# LyteLab_16x16_Base_Rev1.net
KiCad netlist of a schematic drawn in EAGLE
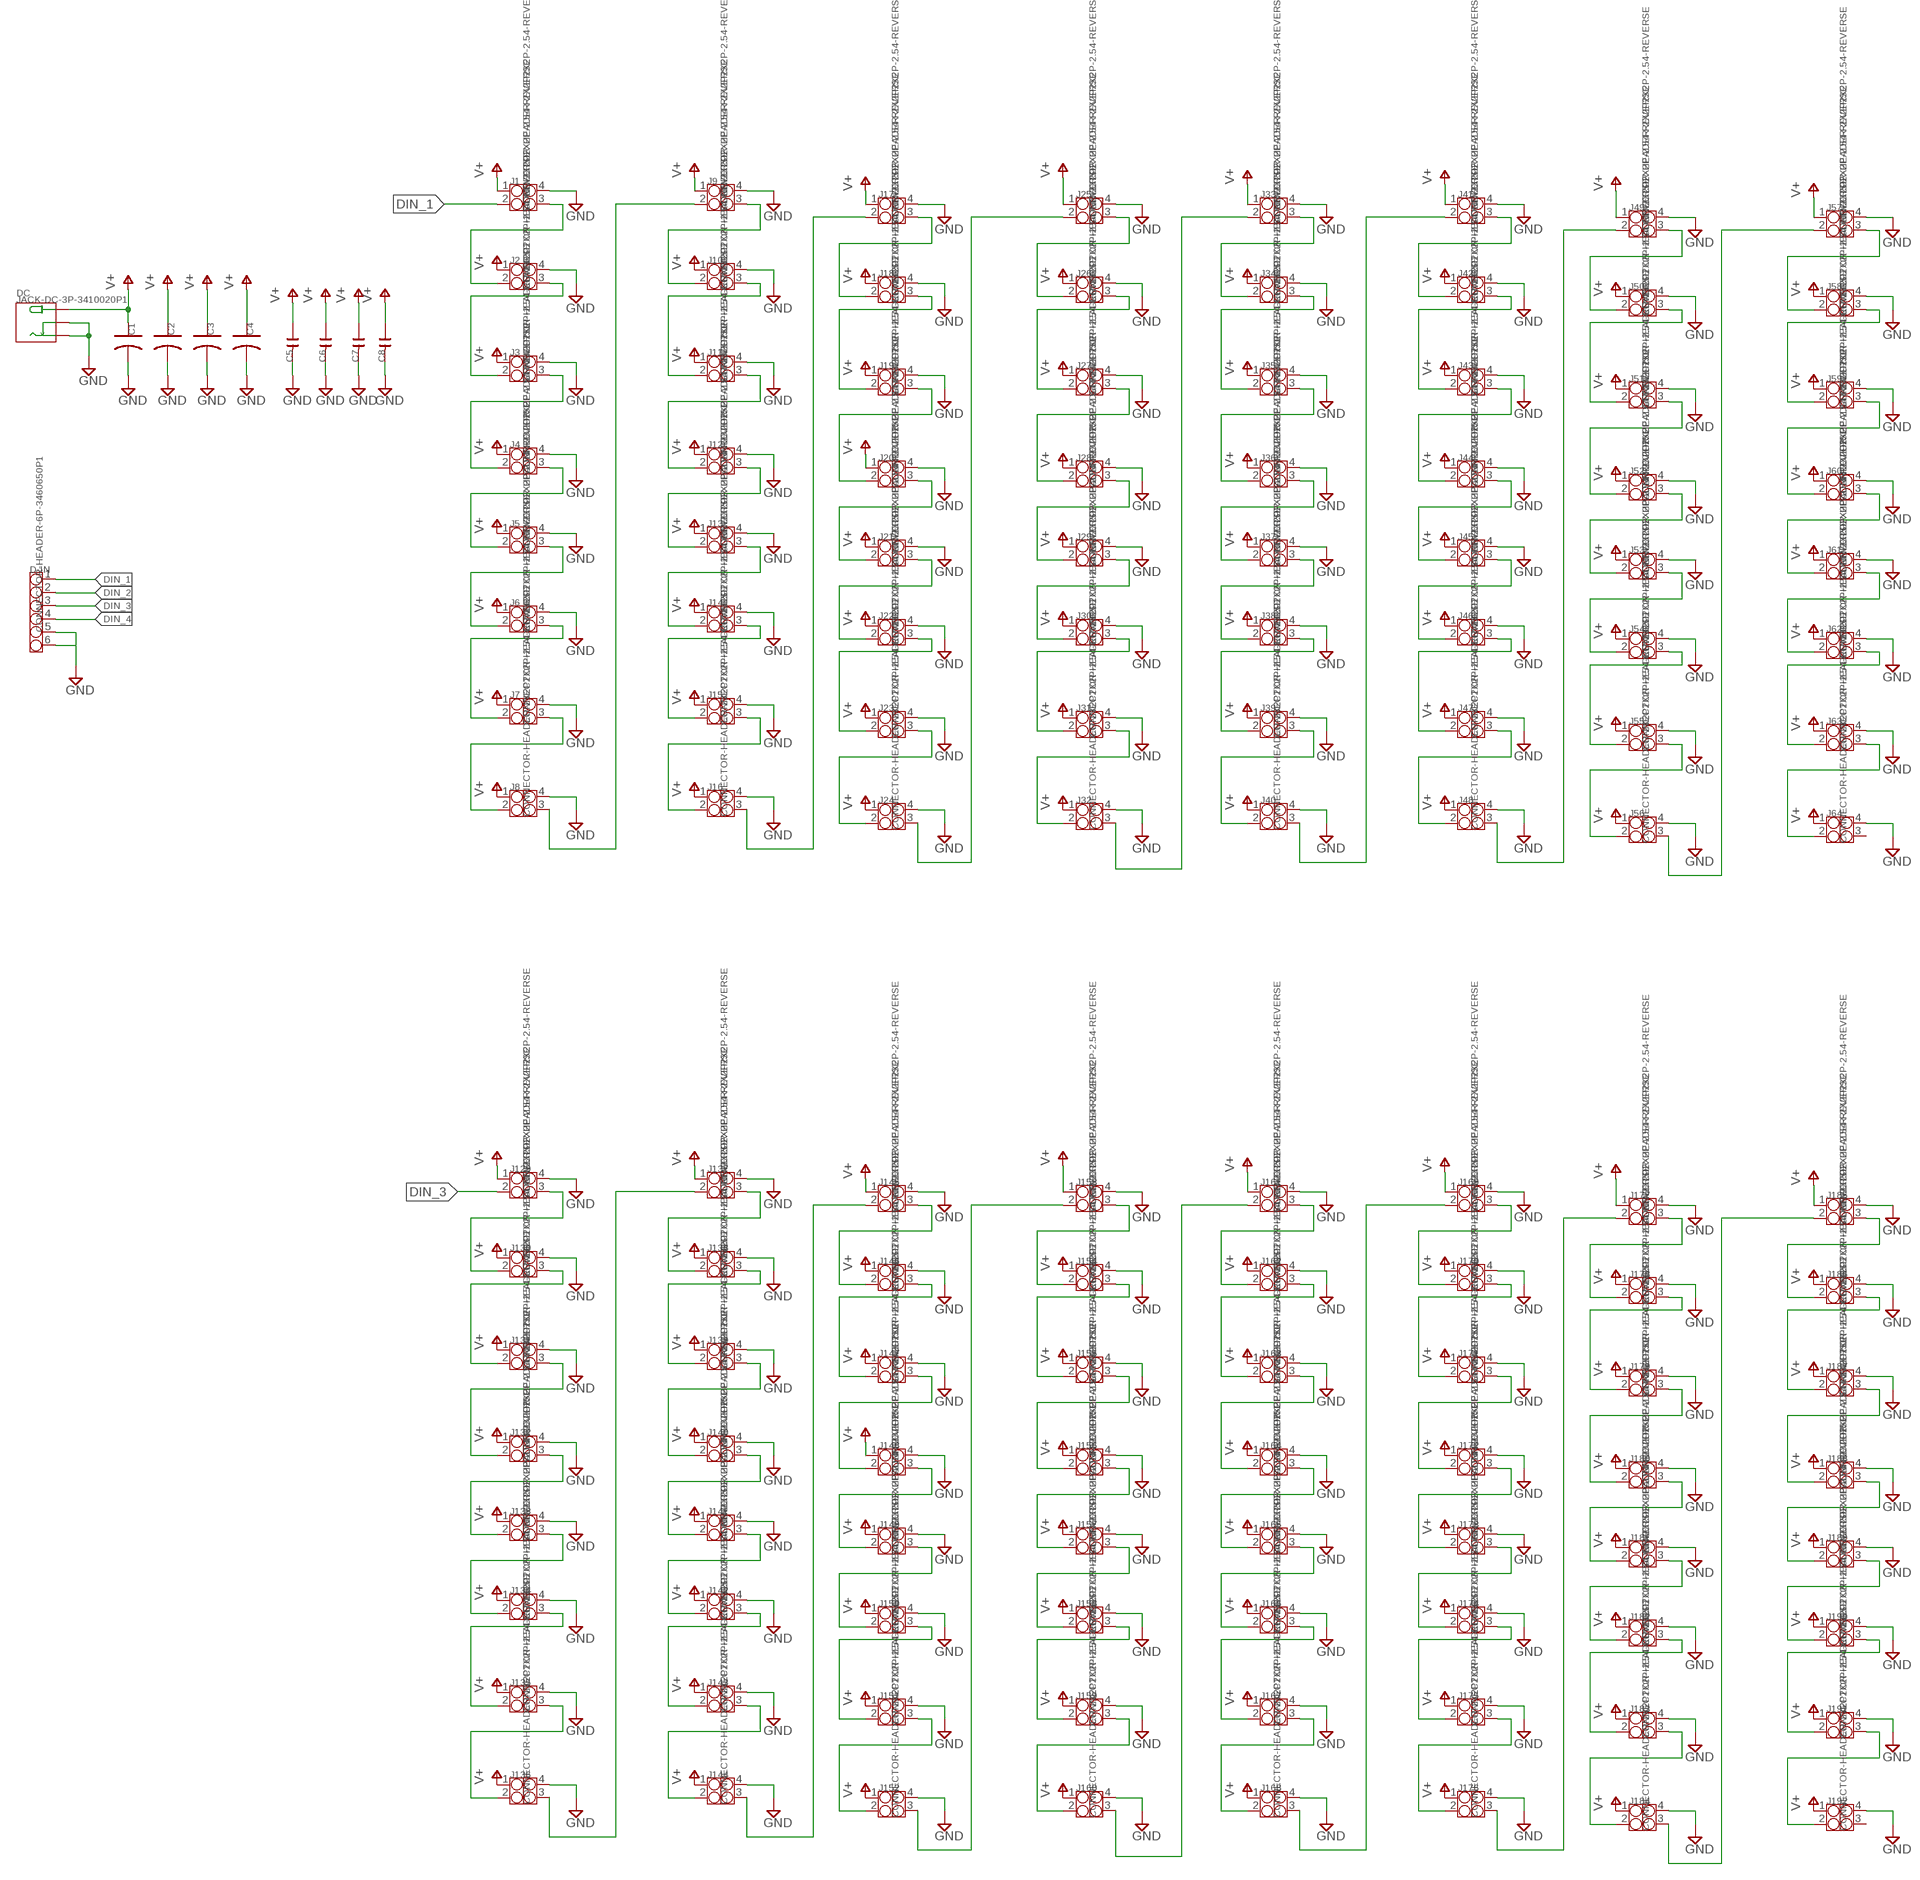
[diagram p0: schematic, sheet 1, part 1 of 2]
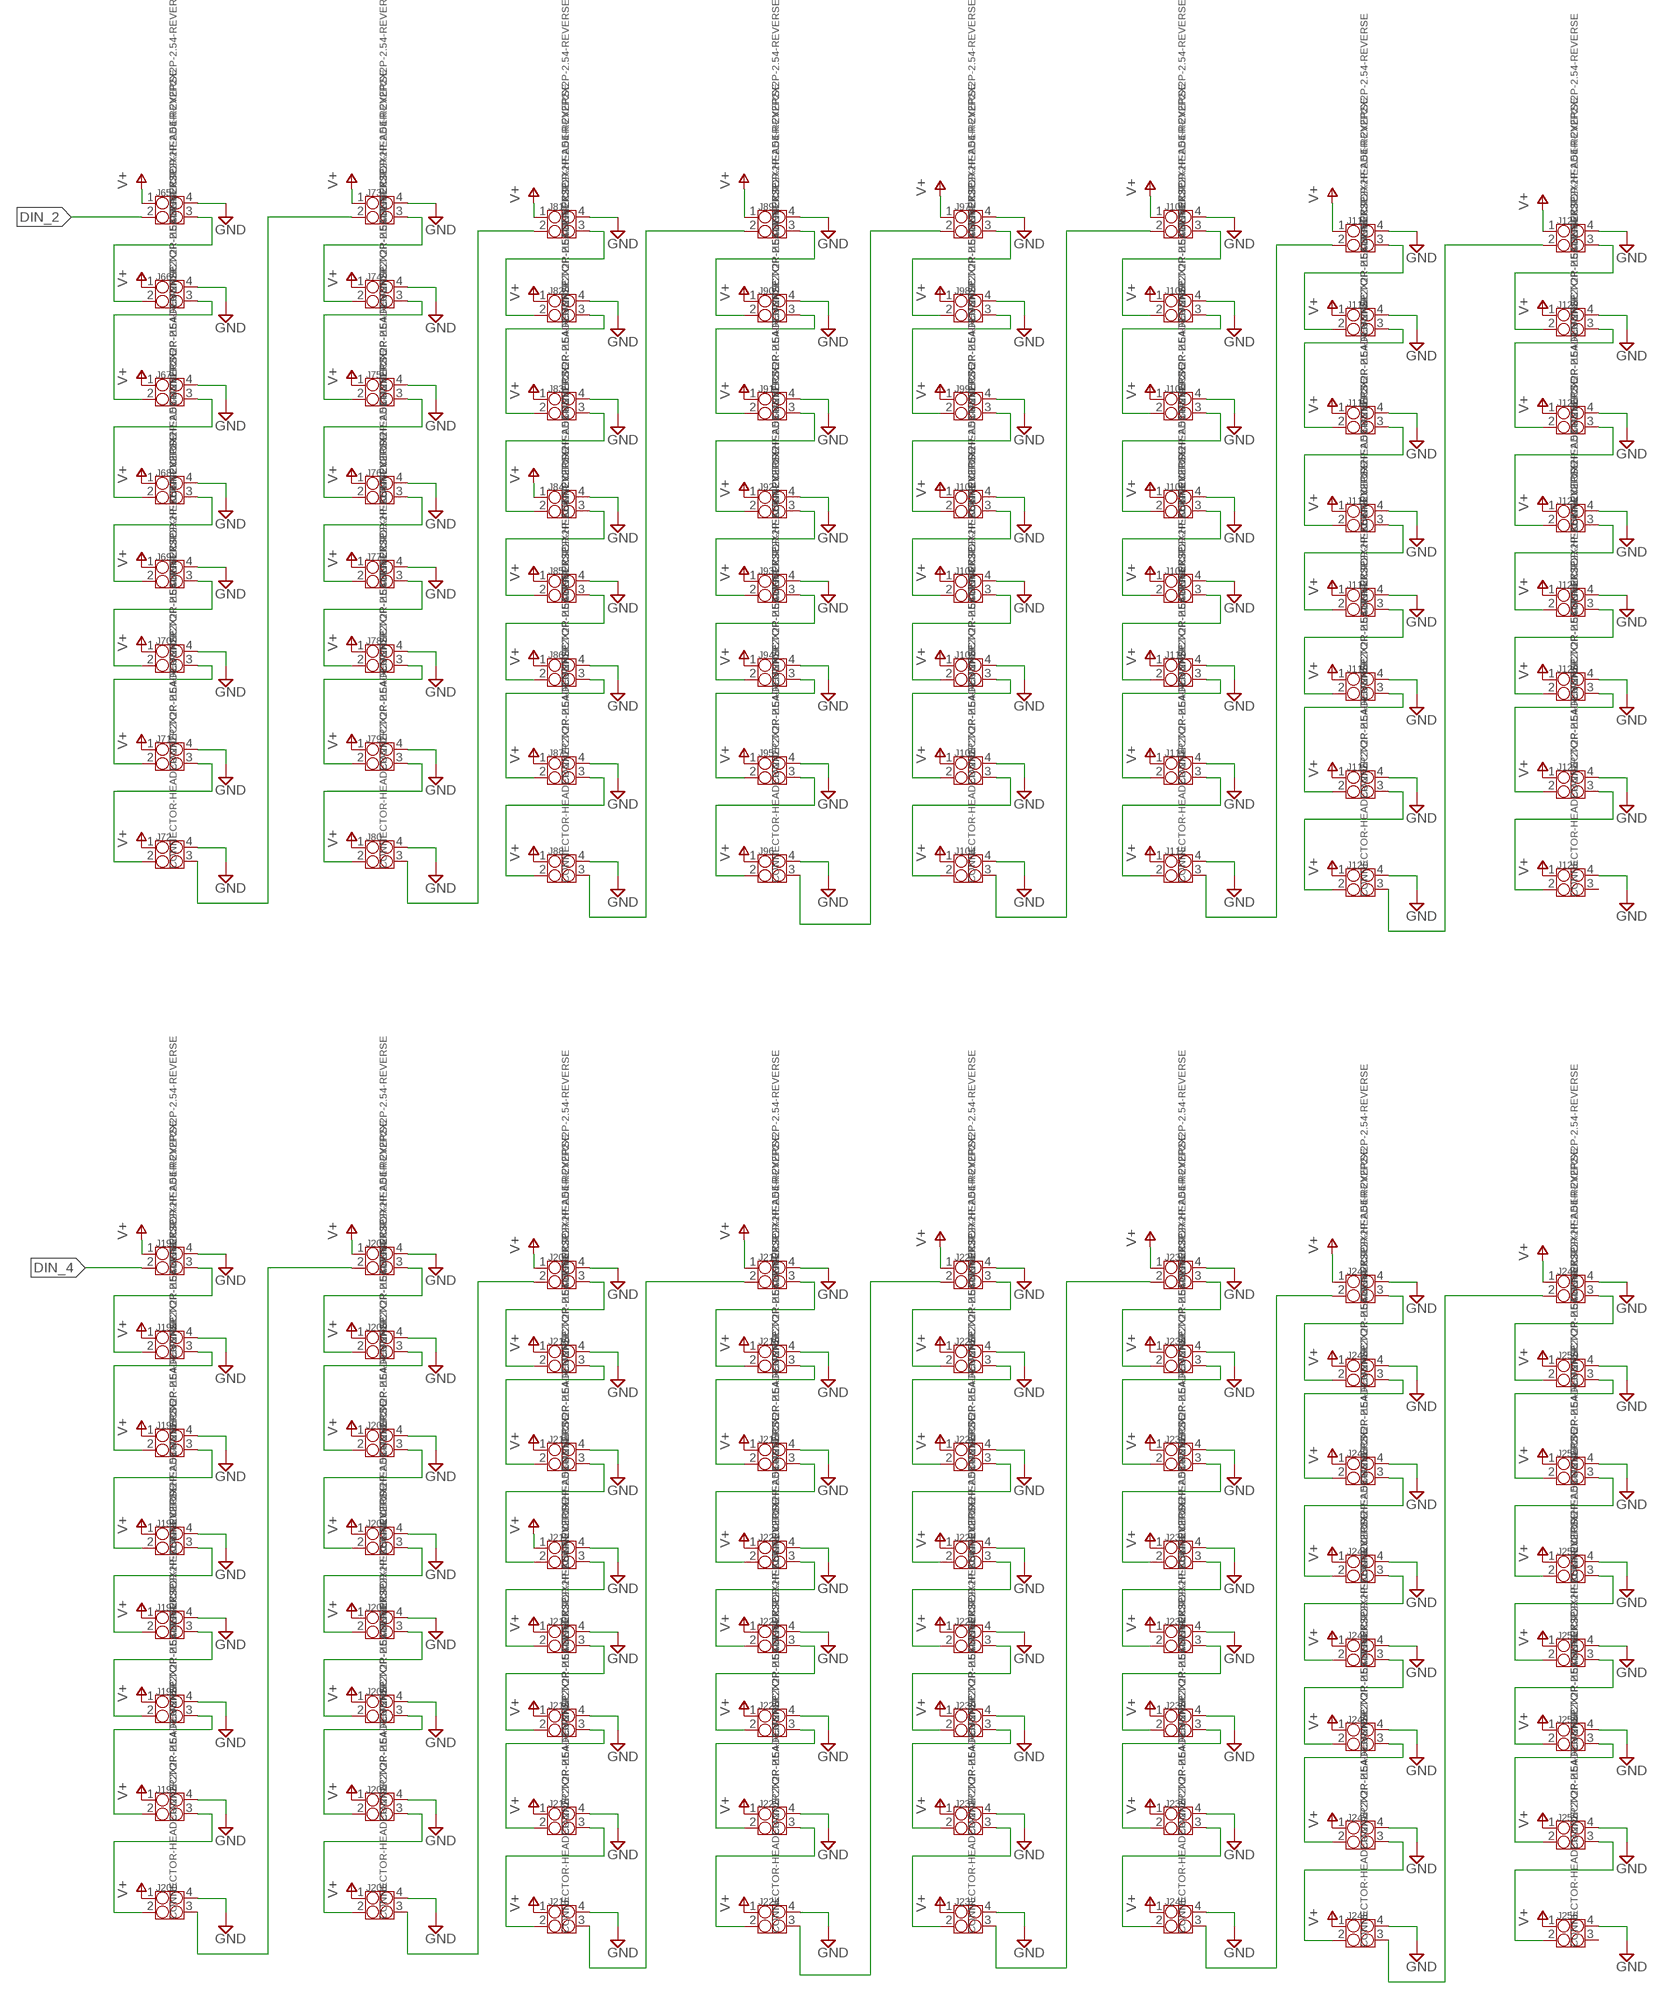
[diagram p1: schematic, sheet 1, part 2 of 2]

(export (version "E")
  (design (tool "Eeschema 10.0.6"))
  (components
    (comp (ref "C1")
      (value "C-POLAR")
      (footprint "eagle-import:CAPACITOR-E3-8")
      (libsource (lib "eagle-import") (part "C-POLAR"))
    )
    (comp (ref "C2")
      (value "C-POLAR")
      (footprint "eagle-import:CAPACITOR-E3-8")
      (libsource (lib "eagle-import") (part "C-POLAR"))
    )
    (comp (ref "C3")
      (value "C-POLAR")
      (footprint "eagle-import:CAPACITOR-E3-8")
      (libsource (lib "eagle-import") (part "C-POLAR"))
    )
    (comp (ref "C4")
      (value "C-POLAR")
      (footprint "eagle-import:CAPACITOR-E3-8")
      (libsource (lib "eagle-import") (part "C-POLAR"))
    )
    (comp (ref "C5")
      (value "C-0603")
      (footprint "eagle-import:C0603")
      (libsource (lib "eagle-import") (part "C-0603"))
    )
    (comp (ref "C6")
      (value "C-0603")
      (footprint "eagle-import:C0603")
      (libsource (lib "eagle-import") (part "C-0603"))
    )
    (comp (ref "C7")
      (value "C-0603")
      (footprint "eagle-import:C0603")
      (libsource (lib "eagle-import") (part "C-0603"))
    )
    (comp (ref "C8")
      (value "C-0603")
      (footprint "eagle-import:C0603")
      (libsource (lib "eagle-import") (part "C-0603"))
    )
    (comp (ref "D-IN")
      (value "CONNECTOR-HEADER-6P-3460650P1")
      (footprint "eagle-import:1X6P-2.54-2.54-11.6-3.0-BLACK-MALE")
      (libsource (lib "eagle-import") (part "CONNECTOR-HEADER-6P-3460650P1"))
    )
    (comp (ref "DC")
      (value "JACK-DC-3P-3410020P1")
      (footprint "eagle-import:PW-3P-2.1")
      (libsource (lib "eagle-import") (part "JACK-DC-3P-3410020P1"))
    )
    (comp (ref "J1")
      (value "CONNECTOR-HEADER-2X2P2X2P-2.54-REVERSE")
      (footprint "eagle-import:2X2P-2.54-REVERSE")
      (libsource (lib "eagle-import") (part "CONNECTOR-HEADER-2X2P2X2P-2.54-REVERSE"))
    )
    (comp (ref "J2")
      (value "CONNECTOR-HEADER-2X2P2X2P-2.54-REVERSE")
      (footprint "eagle-import:2X2P-2.54-REVERSE")
      (libsource (lib "eagle-import") (part "CONNECTOR-HEADER-2X2P2X2P-2.54-REVERSE"))
    )
    (comp (ref "J3")
      (value "CONNECTOR-HEADER-2X2P2X2P-2.54-REVERSE")
      (footprint "eagle-import:2X2P-2.54-REVERSE")
      (libsource (lib "eagle-import") (part "CONNECTOR-HEADER-2X2P2X2P-2.54-REVERSE"))
    )
    (comp (ref "J4")
      (value "CONNECTOR-HEADER-2X2P2X2P-2.54-REVERSE")
      (footprint "eagle-import:2X2P-2.54-REVERSE")
      (libsource (lib "eagle-import") (part "CONNECTOR-HEADER-2X2P2X2P-2.54-REVERSE"))
    )
    (comp (ref "J5")
      (value "CONNECTOR-HEADER-2X2P2X2P-2.54-REVERSE")
      (footprint "eagle-import:2X2P-2.54-REVERSE")
      (libsource (lib "eagle-import") (part "CONNECTOR-HEADER-2X2P2X2P-2.54-REVERSE"))
    )
    (comp (ref "J6")
      (value "CONNECTOR-HEADER-2X2P2X2P-2.54-REVERSE")
      (footprint "eagle-import:2X2P-2.54-REVERSE")
      (libsource (lib "eagle-import") (part "CONNECTOR-HEADER-2X2P2X2P-2.54-REVERSE"))
    )
    (comp (ref "J7")
      (value "CONNECTOR-HEADER-2X2P2X2P-2.54-REVERSE")
      (footprint "eagle-import:2X2P-2.54-REVERSE")
      (libsource (lib "eagle-import") (part "CONNECTOR-HEADER-2X2P2X2P-2.54-REVERSE"))
    )
    (comp (ref "J8")
      (value "CONNECTOR-HEADER-2X2P2X2P-2.54-REVERSE")
      (footprint "eagle-import:2X2P-2.54-REVERSE")
      (libsource (lib "eagle-import") (part "CONNECTOR-HEADER-2X2P2X2P-2.54-REVERSE"))
    )
    (comp (ref "J9")
      (value "CONNECTOR-HEADER-2X2P2X2P-2.54-REVERSE")
      (footprint "eagle-import:2X2P-2.54-REVERSE")
      (libsource (lib "eagle-import") (part "CONNECTOR-HEADER-2X2P2X2P-2.54-REVERSE"))
    )
    (comp (ref "J10")
      (value "CONNECTOR-HEADER-2X2P2X2P-2.54-REVERSE")
      (footprint "eagle-import:2X2P-2.54-REVERSE")
      (libsource (lib "eagle-import") (part "CONNECTOR-HEADER-2X2P2X2P-2.54-REVERSE"))
    )
    (comp (ref "J11")
      (value "CONNECTOR-HEADER-2X2P2X2P-2.54-REVERSE")
      (footprint "eagle-import:2X2P-2.54-REVERSE")
      (libsource (lib "eagle-import") (part "CONNECTOR-HEADER-2X2P2X2P-2.54-REVERSE"))
    )
    (comp (ref "J12")
      (value "CONNECTOR-HEADER-2X2P2X2P-2.54-REVERSE")
      (footprint "eagle-import:2X2P-2.54-REVERSE")
      (libsource (lib "eagle-import") (part "CONNECTOR-HEADER-2X2P2X2P-2.54-REVERSE"))
    )
    (comp (ref "J13")
      (value "CONNECTOR-HEADER-2X2P2X2P-2.54-REVERSE")
      (footprint "eagle-import:2X2P-2.54-REVERSE")
      (libsource (lib "eagle-import") (part "CONNECTOR-HEADER-2X2P2X2P-2.54-REVERSE"))
    )
    (comp (ref "J14")
      (value "CONNECTOR-HEADER-2X2P2X2P-2.54-REVERSE")
      (footprint "eagle-import:2X2P-2.54-REVERSE")
      (libsource (lib "eagle-import") (part "CONNECTOR-HEADER-2X2P2X2P-2.54-REVERSE"))
    )
    (comp (ref "J15")
      (value "CONNECTOR-HEADER-2X2P2X2P-2.54-REVERSE")
      (footprint "eagle-import:2X2P-2.54-REVERSE")
      (libsource (lib "eagle-import") (part "CONNECTOR-HEADER-2X2P2X2P-2.54-REVERSE"))
    )
    (comp (ref "J16")
      (value "CONNECTOR-HEADER-2X2P2X2P-2.54-REVERSE")
      (footprint "eagle-import:2X2P-2.54-REVERSE")
      (libsource (lib "eagle-import") (part "CONNECTOR-HEADER-2X2P2X2P-2.54-REVERSE"))
    )
    (comp (ref "J17")
      (value "CONNECTOR-HEADER-2X2P2X2P-2.54-REVERSE")
      (footprint "eagle-import:2X2P-2.54-REVERSE")
      (libsource (lib "eagle-import") (part "CONNECTOR-HEADER-2X2P2X2P-2.54-REVERSE"))
    )
    (comp (ref "J18")
      (value "CONNECTOR-HEADER-2X2P2X2P-2.54-REVERSE")
      (footprint "eagle-import:2X2P-2.54-REVERSE")
      (libsource (lib "eagle-import") (part "CONNECTOR-HEADER-2X2P2X2P-2.54-REVERSE"))
    )
    (comp (ref "J19")
      (value "CONNECTOR-HEADER-2X2P2X2P-2.54-REVERSE")
      (footprint "eagle-import:2X2P-2.54-REVERSE")
      (libsource (lib "eagle-import") (part "CONNECTOR-HEADER-2X2P2X2P-2.54-REVERSE"))
    )
    (comp (ref "J20")
      (value "CONNECTOR-HEADER-2X2P2X2P-2.54-REVERSE")
      (footprint "eagle-import:2X2P-2.54-REVERSE")
      (libsource (lib "eagle-import") (part "CONNECTOR-HEADER-2X2P2X2P-2.54-REVERSE"))
    )
    (comp (ref "J21")
      (value "CONNECTOR-HEADER-2X2P2X2P-2.54-REVERSE")
      (footprint "eagle-import:2X2P-2.54-REVERSE")
      (libsource (lib "eagle-import") (part "CONNECTOR-HEADER-2X2P2X2P-2.54-REVERSE"))
    )
    (comp (ref "J22")
      (value "CONNECTOR-HEADER-2X2P2X2P-2.54-REVERSE")
      (footprint "eagle-import:2X2P-2.54-REVERSE")
      (libsource (lib "eagle-import") (part "CONNECTOR-HEADER-2X2P2X2P-2.54-REVERSE"))
    )
    (comp (ref "J23")
      (value "CONNECTOR-HEADER-2X2P2X2P-2.54-REVERSE")
      (footprint "eagle-import:2X2P-2.54-REVERSE")
      (libsource (lib "eagle-import") (part "CONNECTOR-HEADER-2X2P2X2P-2.54-REVERSE"))
    )
    (comp (ref "J24")
      (value "CONNECTOR-HEADER-2X2P2X2P-2.54-REVERSE")
      (footprint "eagle-import:2X2P-2.54-REVERSE")
      (libsource (lib "eagle-import") (part "CONNECTOR-HEADER-2X2P2X2P-2.54-REVERSE"))
    )
    (comp (ref "J25")
      (value "CONNECTOR-HEADER-2X2P2X2P-2.54-REVERSE")
      (footprint "eagle-import:2X2P-2.54-REVERSE")
      (libsource (lib "eagle-import") (part "CONNECTOR-HEADER-2X2P2X2P-2.54-REVERSE"))
    )
    (comp (ref "J26")
      (value "CONNECTOR-HEADER-2X2P2X2P-2.54-REVERSE")
      (footprint "eagle-import:2X2P-2.54-REVERSE")
      (libsource (lib "eagle-import") (part "CONNECTOR-HEADER-2X2P2X2P-2.54-REVERSE"))
    )
    (comp (ref "J27")
      (value "CONNECTOR-HEADER-2X2P2X2P-2.54-REVERSE")
      (footprint "eagle-import:2X2P-2.54-REVERSE")
      (libsource (lib "eagle-import") (part "CONNECTOR-HEADER-2X2P2X2P-2.54-REVERSE"))
    )
    (comp (ref "J28")
      (value "CONNECTOR-HEADER-2X2P2X2P-2.54-REVERSE")
      (footprint "eagle-import:2X2P-2.54-REVERSE")
      (libsource (lib "eagle-import") (part "CONNECTOR-HEADER-2X2P2X2P-2.54-REVERSE"))
    )
    (comp (ref "J29")
      (value "CONNECTOR-HEADER-2X2P2X2P-2.54-REVERSE")
      (footprint "eagle-import:2X2P-2.54-REVERSE")
      (libsource (lib "eagle-import") (part "CONNECTOR-HEADER-2X2P2X2P-2.54-REVERSE"))
    )
    (comp (ref "J30")
      (value "CONNECTOR-HEADER-2X2P2X2P-2.54-REVERSE")
      (footprint "eagle-import:2X2P-2.54-REVERSE")
      (libsource (lib "eagle-import") (part "CONNECTOR-HEADER-2X2P2X2P-2.54-REVERSE"))
    )
    (comp (ref "J31")
      (value "CONNECTOR-HEADER-2X2P2X2P-2.54-REVERSE")
      (footprint "eagle-import:2X2P-2.54-REVERSE")
      (libsource (lib "eagle-import") (part "CONNECTOR-HEADER-2X2P2X2P-2.54-REVERSE"))
    )
    (comp (ref "J32")
      (value "CONNECTOR-HEADER-2X2P2X2P-2.54-REVERSE")
      (footprint "eagle-import:2X2P-2.54-REVERSE")
      (libsource (lib "eagle-import") (part "CONNECTOR-HEADER-2X2P2X2P-2.54-REVERSE"))
    )
    (comp (ref "J33")
      (value "CONNECTOR-HEADER-2X2P2X2P-2.54-REVERSE")
      (footprint "eagle-import:2X2P-2.54-REVERSE")
      (libsource (lib "eagle-import") (part "CONNECTOR-HEADER-2X2P2X2P-2.54-REVERSE"))
    )
    (comp (ref "J34")
      (value "CONNECTOR-HEADER-2X2P2X2P-2.54-REVERSE")
      (footprint "eagle-import:2X2P-2.54-REVERSE")
      (libsource (lib "eagle-import") (part "CONNECTOR-HEADER-2X2P2X2P-2.54-REVERSE"))
    )
    (comp (ref "J35")
      (value "CONNECTOR-HEADER-2X2P2X2P-2.54-REVERSE")
      (footprint "eagle-import:2X2P-2.54-REVERSE")
      (libsource (lib "eagle-import") (part "CONNECTOR-HEADER-2X2P2X2P-2.54-REVERSE"))
    )
    (comp (ref "J36")
      (value "CONNECTOR-HEADER-2X2P2X2P-2.54-REVERSE")
      (footprint "eagle-import:2X2P-2.54-REVERSE")
      (libsource (lib "eagle-import") (part "CONNECTOR-HEADER-2X2P2X2P-2.54-REVERSE"))
    )
    (comp (ref "J37")
      (value "CONNECTOR-HEADER-2X2P2X2P-2.54-REVERSE")
      (footprint "eagle-import:2X2P-2.54-REVERSE")
      (libsource (lib "eagle-import") (part "CONNECTOR-HEADER-2X2P2X2P-2.54-REVERSE"))
    )
    (comp (ref "J38")
      (value "CONNECTOR-HEADER-2X2P2X2P-2.54-REVERSE")
      (footprint "eagle-import:2X2P-2.54-REVERSE")
      (libsource (lib "eagle-import") (part "CONNECTOR-HEADER-2X2P2X2P-2.54-REVERSE"))
    )
    (comp (ref "J39")
      (value "CONNECTOR-HEADER-2X2P2X2P-2.54-REVERSE")
      (footprint "eagle-import:2X2P-2.54-REVERSE")
      (libsource (lib "eagle-import") (part "CONNECTOR-HEADER-2X2P2X2P-2.54-REVERSE"))
    )
    (comp (ref "J40")
      (value "CONNECTOR-HEADER-2X2P2X2P-2.54-REVERSE")
      (footprint "eagle-import:2X2P-2.54-REVERSE")
      (libsource (lib "eagle-import") (part "CONNECTOR-HEADER-2X2P2X2P-2.54-REVERSE"))
    )
    (comp (ref "J41")
      (value "CONNECTOR-HEADER-2X2P2X2P-2.54-REVERSE")
      (footprint "eagle-import:2X2P-2.54-REVERSE")
      (libsource (lib "eagle-import") (part "CONNECTOR-HEADER-2X2P2X2P-2.54-REVERSE"))
    )
    (comp (ref "J42")
      (value "CONNECTOR-HEADER-2X2P2X2P-2.54-REVERSE")
      (footprint "eagle-import:2X2P-2.54-REVERSE")
      (libsource (lib "eagle-import") (part "CONNECTOR-HEADER-2X2P2X2P-2.54-REVERSE"))
    )
    (comp (ref "J43")
      (value "CONNECTOR-HEADER-2X2P2X2P-2.54-REVERSE")
      (footprint "eagle-import:2X2P-2.54-REVERSE")
      (libsource (lib "eagle-import") (part "CONNECTOR-HEADER-2X2P2X2P-2.54-REVERSE"))
    )
    (comp (ref "J44")
      (value "CONNECTOR-HEADER-2X2P2X2P-2.54-REVERSE")
      (footprint "eagle-import:2X2P-2.54-REVERSE")
      (libsource (lib "eagle-import") (part "CONNECTOR-HEADER-2X2P2X2P-2.54-REVERSE"))
    )
    (comp (ref "J45")
      (value "CONNECTOR-HEADER-2X2P2X2P-2.54-REVERSE")
      (footprint "eagle-import:2X2P-2.54-REVERSE")
      (libsource (lib "eagle-import") (part "CONNECTOR-HEADER-2X2P2X2P-2.54-REVERSE"))
    )
    (comp (ref "J46")
      (value "CONNECTOR-HEADER-2X2P2X2P-2.54-REVERSE")
      (footprint "eagle-import:2X2P-2.54-REVERSE")
      (libsource (lib "eagle-import") (part "CONNECTOR-HEADER-2X2P2X2P-2.54-REVERSE"))
    )
    (comp (ref "J47")
      (value "CONNECTOR-HEADER-2X2P2X2P-2.54-REVERSE")
      (footprint "eagle-import:2X2P-2.54-REVERSE")
      (libsource (lib "eagle-import") (part "CONNECTOR-HEADER-2X2P2X2P-2.54-REVERSE"))
    )
    (comp (ref "J48")
      (value "CONNECTOR-HEADER-2X2P2X2P-2.54-REVERSE")
      (footprint "eagle-import:2X2P-2.54-REVERSE")
      (libsource (lib "eagle-import") (part "CONNECTOR-HEADER-2X2P2X2P-2.54-REVERSE"))
    )
    (comp (ref "J49")
      (value "CONNECTOR-HEADER-2X2P2X2P-2.54-REVERSE")
      (footprint "eagle-import:2X2P-2.54-REVERSE")
      (libsource (lib "eagle-import") (part "CONNECTOR-HEADER-2X2P2X2P-2.54-REVERSE"))
    )
    (comp (ref "J50")
      (value "CONNECTOR-HEADER-2X2P2X2P-2.54-REVERSE")
      (footprint "eagle-import:2X2P-2.54-REVERSE")
      (libsource (lib "eagle-import") (part "CONNECTOR-HEADER-2X2P2X2P-2.54-REVERSE"))
    )
    (comp (ref "J51")
      (value "CONNECTOR-HEADER-2X2P2X2P-2.54-REVERSE")
      (footprint "eagle-import:2X2P-2.54-REVERSE")
      (libsource (lib "eagle-import") (part "CONNECTOR-HEADER-2X2P2X2P-2.54-REVERSE"))
    )
    (comp (ref "J52")
      (value "CONNECTOR-HEADER-2X2P2X2P-2.54-REVERSE")
      (footprint "eagle-import:2X2P-2.54-REVERSE")
      (libsource (lib "eagle-import") (part "CONNECTOR-HEADER-2X2P2X2P-2.54-REVERSE"))
    )
    (comp (ref "J53")
      (value "CONNECTOR-HEADER-2X2P2X2P-2.54-REVERSE")
      (footprint "eagle-import:2X2P-2.54-REVERSE")
      (libsource (lib "eagle-import") (part "CONNECTOR-HEADER-2X2P2X2P-2.54-REVERSE"))
    )
    (comp (ref "J54")
      (value "CONNECTOR-HEADER-2X2P2X2P-2.54-REVERSE")
      (footprint "eagle-import:2X2P-2.54-REVERSE")
      (libsource (lib "eagle-import") (part "CONNECTOR-HEADER-2X2P2X2P-2.54-REVERSE"))
    )
    (comp (ref "J55")
      (value "CONNECTOR-HEADER-2X2P2X2P-2.54-REVERSE")
      (footprint "eagle-import:2X2P-2.54-REVERSE")
      (libsource (lib "eagle-import") (part "CONNECTOR-HEADER-2X2P2X2P-2.54-REVERSE"))
    )
    (comp (ref "J56")
      (value "CONNECTOR-HEADER-2X2P2X2P-2.54-REVERSE")
      (footprint "eagle-import:2X2P-2.54-REVERSE")
      (libsource (lib "eagle-import") (part "CONNECTOR-HEADER-2X2P2X2P-2.54-REVERSE"))
    )
    (comp (ref "J57")
      (value "CONNECTOR-HEADER-2X2P2X2P-2.54-REVERSE")
      (footprint "eagle-import:2X2P-2.54-REVERSE")
      (libsource (lib "eagle-import") (part "CONNECTOR-HEADER-2X2P2X2P-2.54-REVERSE"))
    )
    (comp (ref "J58")
      (value "CONNECTOR-HEADER-2X2P2X2P-2.54-REVERSE")
      (footprint "eagle-import:2X2P-2.54-REVERSE")
      (libsource (lib "eagle-import") (part "CONNECTOR-HEADER-2X2P2X2P-2.54-REVERSE"))
    )
    (comp (ref "J59")
      (value "CONNECTOR-HEADER-2X2P2X2P-2.54-REVERSE")
      (footprint "eagle-import:2X2P-2.54-REVERSE")
      (libsource (lib "eagle-import") (part "CONNECTOR-HEADER-2X2P2X2P-2.54-REVERSE"))
    )
    (comp (ref "J60")
      (value "CONNECTOR-HEADER-2X2P2X2P-2.54-REVERSE")
      (footprint "eagle-import:2X2P-2.54-REVERSE")
      (libsource (lib "eagle-import") (part "CONNECTOR-HEADER-2X2P2X2P-2.54-REVERSE"))
    )
    (comp (ref "J61")
      (value "CONNECTOR-HEADER-2X2P2X2P-2.54-REVERSE")
      (footprint "eagle-import:2X2P-2.54-REVERSE")
      (libsource (lib "eagle-import") (part "CONNECTOR-HEADER-2X2P2X2P-2.54-REVERSE"))
    )
    (comp (ref "J62")
      (value "CONNECTOR-HEADER-2X2P2X2P-2.54-REVERSE")
      (footprint "eagle-import:2X2P-2.54-REVERSE")
      (libsource (lib "eagle-import") (part "CONNECTOR-HEADER-2X2P2X2P-2.54-REVERSE"))
    )
    (comp (ref "J63")
      (value "CONNECTOR-HEADER-2X2P2X2P-2.54-REVERSE")
      (footprint "eagle-import:2X2P-2.54-REVERSE")
      (libsource (lib "eagle-import") (part "CONNECTOR-HEADER-2X2P2X2P-2.54-REVERSE"))
    )
    (comp (ref "J64")
      (value "CONNECTOR-HEADER-2X2P2X2P-2.54-REVERSE")
      (footprint "eagle-import:2X2P-2.54-REVERSE")
      (libsource (lib "eagle-import") (part "CONNECTOR-HEADER-2X2P2X2P-2.54-REVERSE"))
    )
    (comp (ref "J65")
      (value "CONNECTOR-HEADER-2X2P2X2P-2.54-REVERSE")
      (footprint "eagle-import:2X2P-2.54-REVERSE")
      (libsource (lib "eagle-import") (part "CONNECTOR-HEADER-2X2P2X2P-2.54-REVERSE"))
    )
    (comp (ref "J66")
      (value "CONNECTOR-HEADER-2X2P2X2P-2.54-REVERSE")
      (footprint "eagle-import:2X2P-2.54-REVERSE")
      (libsource (lib "eagle-import") (part "CONNECTOR-HEADER-2X2P2X2P-2.54-REVERSE"))
    )
    (comp (ref "J67")
      (value "CONNECTOR-HEADER-2X2P2X2P-2.54-REVERSE")
      (footprint "eagle-import:2X2P-2.54-REVERSE")
      (libsource (lib "eagle-import") (part "CONNECTOR-HEADER-2X2P2X2P-2.54-REVERSE"))
    )
    (comp (ref "J68")
      (value "CONNECTOR-HEADER-2X2P2X2P-2.54-REVERSE")
      (footprint "eagle-import:2X2P-2.54-REVERSE")
      (libsource (lib "eagle-import") (part "CONNECTOR-HEADER-2X2P2X2P-2.54-REVERSE"))
    )
    (comp (ref "J69")
      (value "CONNECTOR-HEADER-2X2P2X2P-2.54-REVERSE")
      (footprint "eagle-import:2X2P-2.54-REVERSE")
      (libsource (lib "eagle-import") (part "CONNECTOR-HEADER-2X2P2X2P-2.54-REVERSE"))
    )
    (comp (ref "J70")
      (value "CONNECTOR-HEADER-2X2P2X2P-2.54-REVERSE")
      (footprint "eagle-import:2X2P-2.54-REVERSE")
      (libsource (lib "eagle-import") (part "CONNECTOR-HEADER-2X2P2X2P-2.54-REVERSE"))
    )
    (comp (ref "J71")
      (value "CONNECTOR-HEADER-2X2P2X2P-2.54-REVERSE")
      (footprint "eagle-import:2X2P-2.54-REVERSE")
      (libsource (lib "eagle-import") (part "CONNECTOR-HEADER-2X2P2X2P-2.54-REVERSE"))
    )
    (comp (ref "J72")
      (value "CONNECTOR-HEADER-2X2P2X2P-2.54-REVERSE")
      (footprint "eagle-import:2X2P-2.54-REVERSE")
      (libsource (lib "eagle-import") (part "CONNECTOR-HEADER-2X2P2X2P-2.54-REVERSE"))
    )
    (comp (ref "J73")
      (value "CONNECTOR-HEADER-2X2P2X2P-2.54-REVERSE")
      (footprint "eagle-import:2X2P-2.54-REVERSE")
      (libsource (lib "eagle-import") (part "CONNECTOR-HEADER-2X2P2X2P-2.54-REVERSE"))
    )
    (comp (ref "J74")
      (value "CONNECTOR-HEADER-2X2P2X2P-2.54-REVERSE")
      (footprint "eagle-import:2X2P-2.54-REVERSE")
      (libsource (lib "eagle-import") (part "CONNECTOR-HEADER-2X2P2X2P-2.54-REVERSE"))
    )
    (comp (ref "J75")
      (value "CONNECTOR-HEADER-2X2P2X2P-2.54-REVERSE")
      (footprint "eagle-import:2X2P-2.54-REVERSE")
      (libsource (lib "eagle-import") (part "CONNECTOR-HEADER-2X2P2X2P-2.54-REVERSE"))
    )
    (comp (ref "J76")
      (value "CONNECTOR-HEADER-2X2P2X2P-2.54-REVERSE")
      (footprint "eagle-import:2X2P-2.54-REVERSE")
      (libsource (lib "eagle-import") (part "CONNECTOR-HEADER-2X2P2X2P-2.54-REVERSE"))
    )
    (comp (ref "J77")
      (value "CONNECTOR-HEADER-2X2P2X2P-2.54-REVERSE")
      (footprint "eagle-import:2X2P-2.54-REVERSE")
      (libsource (lib "eagle-import") (part "CONNECTOR-HEADER-2X2P2X2P-2.54-REVERSE"))
    )
    (comp (ref "J78")
      (value "CONNECTOR-HEADER-2X2P2X2P-2.54-REVERSE")
      (footprint "eagle-import:2X2P-2.54-REVERSE")
      (libsource (lib "eagle-import") (part "CONNECTOR-HEADER-2X2P2X2P-2.54-REVERSE"))
    )
    (comp (ref "J79")
      (value "CONNECTOR-HEADER-2X2P2X2P-2.54-REVERSE")
      (footprint "eagle-import:2X2P-2.54-REVERSE")
      (libsource (lib "eagle-import") (part "CONNECTOR-HEADER-2X2P2X2P-2.54-REVERSE"))
    )
    (comp (ref "J80")
      (value "CONNECTOR-HEADER-2X2P2X2P-2.54-REVERSE")
      (footprint "eagle-import:2X2P-2.54-REVERSE")
      (libsource (lib "eagle-import") (part "CONNECTOR-HEADER-2X2P2X2P-2.54-REVERSE"))
    )
    (comp (ref "J81")
      (value "CONNECTOR-HEADER-2X2P2X2P-2.54-REVERSE")
      (footprint "eagle-import:2X2P-2.54-REVERSE")
      (libsource (lib "eagle-import") (part "CONNECTOR-HEADER-2X2P2X2P-2.54-REVERSE"))
    )
    (comp (ref "J82")
      (value "CONNECTOR-HEADER-2X2P2X2P-2.54-REVERSE")
      (footprint "eagle-import:2X2P-2.54-REVERSE")
      (libsource (lib "eagle-import") (part "CONNECTOR-HEADER-2X2P2X2P-2.54-REVERSE"))
    )
    (comp (ref "J83")
      (value "CONNECTOR-HEADER-2X2P2X2P-2.54-REVERSE")
      (footprint "eagle-import:2X2P-2.54-REVERSE")
      (libsource (lib "eagle-import") (part "CONNECTOR-HEADER-2X2P2X2P-2.54-REVERSE"))
    )
    (comp (ref "J84")
      (value "CONNECTOR-HEADER-2X2P2X2P-2.54-REVERSE")
      (footprint "eagle-import:2X2P-2.54-REVERSE")
      (libsource (lib "eagle-import") (part "CONNECTOR-HEADER-2X2P2X2P-2.54-REVERSE"))
    )
    (comp (ref "J85")
      (value "CONNECTOR-HEADER-2X2P2X2P-2.54-REVERSE")
      (footprint "eagle-import:2X2P-2.54-REVERSE")
      (libsource (lib "eagle-import") (part "CONNECTOR-HEADER-2X2P2X2P-2.54-REVERSE"))
    )
    (comp (ref "J86")
      (value "CONNECTOR-HEADER-2X2P2X2P-2.54-REVERSE")
      (footprint "eagle-import:2X2P-2.54-REVERSE")
      (libsource (lib "eagle-import") (part "CONNECTOR-HEADER-2X2P2X2P-2.54-REVERSE"))
    )
    (comp (ref "J87")
      (value "CONNECTOR-HEADER-2X2P2X2P-2.54-REVERSE")
      (footprint "eagle-import:2X2P-2.54-REVERSE")
      (libsource (lib "eagle-import") (part "CONNECTOR-HEADER-2X2P2X2P-2.54-REVERSE"))
    )
    (comp (ref "J88")
      (value "CONNECTOR-HEADER-2X2P2X2P-2.54-REVERSE")
      (footprint "eagle-import:2X2P-2.54-REVERSE")
      (libsource (lib "eagle-import") (part "CONNECTOR-HEADER-2X2P2X2P-2.54-REVERSE"))
    )
    (comp (ref "J89")
      (value "CONNECTOR-HEADER-2X2P2X2P-2.54-REVERSE")
      (footprint "eagle-import:2X2P-2.54-REVERSE")
      (libsource (lib "eagle-import") (part "CONNECTOR-HEADER-2X2P2X2P-2.54-REVERSE"))
    )
    (comp (ref "J90")
      (value "CONNECTOR-HEADER-2X2P2X2P-2.54-REVERSE")
      (footprint "eagle-import:2X2P-2.54-REVERSE")
      (libsource (lib "eagle-import") (part "CONNECTOR-HEADER-2X2P2X2P-2.54-REVERSE"))
    )
    (comp (ref "J91")
      (value "CONNECTOR-HEADER-2X2P2X2P-2.54-REVERSE")
      (footprint "eagle-import:2X2P-2.54-REVERSE")
      (libsource (lib "eagle-import") (part "CONNECTOR-HEADER-2X2P2X2P-2.54-REVERSE"))
    )
    (comp (ref "J92")
      (value "CONNECTOR-HEADER-2X2P2X2P-2.54-REVERSE")
      (footprint "eagle-import:2X2P-2.54-REVERSE")
      (libsource (lib "eagle-import") (part "CONNECTOR-HEADER-2X2P2X2P-2.54-REVERSE"))
    )
    (comp (ref "J93")
      (value "CONNECTOR-HEADER-2X2P2X2P-2.54-REVERSE")
      (footprint "eagle-import:2X2P-2.54-REVERSE")
      (libsource (lib "eagle-import") (part "CONNECTOR-HEADER-2X2P2X2P-2.54-REVERSE"))
    )
    (comp (ref "J94")
      (value "CONNECTOR-HEADER-2X2P2X2P-2.54-REVERSE")
      (footprint "eagle-import:2X2P-2.54-REVERSE")
      (libsource (lib "eagle-import") (part "CONNECTOR-HEADER-2X2P2X2P-2.54-REVERSE"))
    )
    (comp (ref "J95")
      (value "CONNECTOR-HEADER-2X2P2X2P-2.54-REVERSE")
      (footprint "eagle-import:2X2P-2.54-REVERSE")
      (libsource (lib "eagle-import") (part "CONNECTOR-HEADER-2X2P2X2P-2.54-REVERSE"))
    )
    (comp (ref "J96")
      (value "CONNECTOR-HEADER-2X2P2X2P-2.54-REVERSE")
      (footprint "eagle-import:2X2P-2.54-REVERSE")
      (libsource (lib "eagle-import") (part "CONNECTOR-HEADER-2X2P2X2P-2.54-REVERSE"))
    )
    (comp (ref "J97")
      (value "CONNECTOR-HEADER-2X2P2X2P-2.54-REVERSE")
      (footprint "eagle-import:2X2P-2.54-REVERSE")
      (libsource (lib "eagle-import") (part "CONNECTOR-HEADER-2X2P2X2P-2.54-REVERSE"))
    )
    (comp (ref "J98")
      (value "CONNECTOR-HEADER-2X2P2X2P-2.54-REVERSE")
      (footprint "eagle-import:2X2P-2.54-REVERSE")
      (libsource (lib "eagle-import") (part "CONNECTOR-HEADER-2X2P2X2P-2.54-REVERSE"))
    )
    (comp (ref "J99")
      (value "CONNECTOR-HEADER-2X2P2X2P-2.54-REVERSE")
      (footprint "eagle-import:2X2P-2.54-REVERSE")
      (libsource (lib "eagle-import") (part "CONNECTOR-HEADER-2X2P2X2P-2.54-REVERSE"))
    )
    (comp (ref "J100")
      (value "CONNECTOR-HEADER-2X2P2X2P-2.54-REVERSE")
      (footprint "eagle-import:2X2P-2.54-REVERSE")
      (libsource (lib "eagle-import") (part "CONNECTOR-HEADER-2X2P2X2P-2.54-REVERSE"))
    )
    (comp (ref "J101")
      (value "CONNECTOR-HEADER-2X2P2X2P-2.54-REVERSE")
      (footprint "eagle-import:2X2P-2.54-REVERSE")
      (libsource (lib "eagle-import") (part "CONNECTOR-HEADER-2X2P2X2P-2.54-REVERSE"))
    )
    (comp (ref "J102")
      (value "CONNECTOR-HEADER-2X2P2X2P-2.54-REVERSE")
      (footprint "eagle-import:2X2P-2.54-REVERSE")
      (libsource (lib "eagle-import") (part "CONNECTOR-HEADER-2X2P2X2P-2.54-REVERSE"))
    )
    (comp (ref "J103")
      (value "CONNECTOR-HEADER-2X2P2X2P-2.54-REVERSE")
      (footprint "eagle-import:2X2P-2.54-REVERSE")
      (libsource (lib "eagle-import") (part "CONNECTOR-HEADER-2X2P2X2P-2.54-REVERSE"))
    )
    (comp (ref "J104")
      (value "CONNECTOR-HEADER-2X2P2X2P-2.54-REVERSE")
      (footprint "eagle-import:2X2P-2.54-REVERSE")
      (libsource (lib "eagle-import") (part "CONNECTOR-HEADER-2X2P2X2P-2.54-REVERSE"))
    )
    (comp (ref "J105")
      (value "CONNECTOR-HEADER-2X2P2X2P-2.54-REVERSE")
      (footprint "eagle-import:2X2P-2.54-REVERSE")
      (libsource (lib "eagle-import") (part "CONNECTOR-HEADER-2X2P2X2P-2.54-REVERSE"))
    )
    (comp (ref "J106")
      (value "CONNECTOR-HEADER-2X2P2X2P-2.54-REVERSE")
      (footprint "eagle-import:2X2P-2.54-REVERSE")
      (libsource (lib "eagle-import") (part "CONNECTOR-HEADER-2X2P2X2P-2.54-REVERSE"))
    )
    (comp (ref "J107")
      (value "CONNECTOR-HEADER-2X2P2X2P-2.54-REVERSE")
      (footprint "eagle-import:2X2P-2.54-REVERSE")
      (libsource (lib "eagle-import") (part "CONNECTOR-HEADER-2X2P2X2P-2.54-REVERSE"))
    )
    (comp (ref "J108")
      (value "CONNECTOR-HEADER-2X2P2X2P-2.54-REVERSE")
      (footprint "eagle-import:2X2P-2.54-REVERSE")
      (libsource (lib "eagle-import") (part "CONNECTOR-HEADER-2X2P2X2P-2.54-REVERSE"))
    )
    (comp (ref "J109")
      (value "CONNECTOR-HEADER-2X2P2X2P-2.54-REVERSE")
      (footprint "eagle-import:2X2P-2.54-REVERSE")
      (libsource (lib "eagle-import") (part "CONNECTOR-HEADER-2X2P2X2P-2.54-REVERSE"))
    )
    (comp (ref "J110")
      (value "CONNECTOR-HEADER-2X2P2X2P-2.54-REVERSE")
      (footprint "eagle-import:2X2P-2.54-REVERSE")
      (libsource (lib "eagle-import") (part "CONNECTOR-HEADER-2X2P2X2P-2.54-REVERSE"))
    )
    (comp (ref "J111")
      (value "CONNECTOR-HEADER-2X2P2X2P-2.54-REVERSE")
      (footprint "eagle-import:2X2P-2.54-REVERSE")
      (libsource (lib "eagle-import") (part "CONNECTOR-HEADER-2X2P2X2P-2.54-REVERSE"))
    )
    (comp (ref "J112")
      (value "CONNECTOR-HEADER-2X2P2X2P-2.54-REVERSE")
      (footprint "eagle-import:2X2P-2.54-REVERSE")
      (libsource (lib "eagle-import") (part "CONNECTOR-HEADER-2X2P2X2P-2.54-REVERSE"))
    )
    (comp (ref "J113")
      (value "CONNECTOR-HEADER-2X2P2X2P-2.54-REVERSE")
      (footprint "eagle-import:2X2P-2.54-REVERSE")
      (libsource (lib "eagle-import") (part "CONNECTOR-HEADER-2X2P2X2P-2.54-REVERSE"))
    )
    (comp (ref "J114")
      (value "CONNECTOR-HEADER-2X2P2X2P-2.54-REVERSE")
      (footprint "eagle-import:2X2P-2.54-REVERSE")
      (libsource (lib "eagle-import") (part "CONNECTOR-HEADER-2X2P2X2P-2.54-REVERSE"))
    )
    (comp (ref "J115")
      (value "CONNECTOR-HEADER-2X2P2X2P-2.54-REVERSE")
      (footprint "eagle-import:2X2P-2.54-REVERSE")
      (libsource (lib "eagle-import") (part "CONNECTOR-HEADER-2X2P2X2P-2.54-REVERSE"))
    )
    (comp (ref "J116")
      (value "CONNECTOR-HEADER-2X2P2X2P-2.54-REVERSE")
      (footprint "eagle-import:2X2P-2.54-REVERSE")
      (libsource (lib "eagle-import") (part "CONNECTOR-HEADER-2X2P2X2P-2.54-REVERSE"))
    )
    (comp (ref "J117")
      (value "CONNECTOR-HEADER-2X2P2X2P-2.54-REVERSE")
      (footprint "eagle-import:2X2P-2.54-REVERSE")
      (libsource (lib "eagle-import") (part "CONNECTOR-HEADER-2X2P2X2P-2.54-REVERSE"))
    )
    (comp (ref "J118")
      (value "CONNECTOR-HEADER-2X2P2X2P-2.54-REVERSE")
      (footprint "eagle-import:2X2P-2.54-REVERSE")
      (libsource (lib "eagle-import") (part "CONNECTOR-HEADER-2X2P2X2P-2.54-REVERSE"))
    )
    (comp (ref "J119")
      (value "CONNECTOR-HEADER-2X2P2X2P-2.54-REVERSE")
      (footprint "eagle-import:2X2P-2.54-REVERSE")
      (libsource (lib "eagle-import") (part "CONNECTOR-HEADER-2X2P2X2P-2.54-REVERSE"))
    )
    (comp (ref "J120")
      (value "CONNECTOR-HEADER-2X2P2X2P-2.54-REVERSE")
      (footprint "eagle-import:2X2P-2.54-REVERSE")
      (libsource (lib "eagle-import") (part "CONNECTOR-HEADER-2X2P2X2P-2.54-REVERSE"))
    )
    (comp (ref "J121")
      (value "CONNECTOR-HEADER-2X2P2X2P-2.54-REVERSE")
      (footprint "eagle-import:2X2P-2.54-REVERSE")
      (libsource (lib "eagle-import") (part "CONNECTOR-HEADER-2X2P2X2P-2.54-REVERSE"))
    )
    (comp (ref "J122")
      (value "CONNECTOR-HEADER-2X2P2X2P-2.54-REVERSE")
      (footprint "eagle-import:2X2P-2.54-REVERSE")
      (libsource (lib "eagle-import") (part "CONNECTOR-HEADER-2X2P2X2P-2.54-REVERSE"))
    )
    (comp (ref "J123")
      (value "CONNECTOR-HEADER-2X2P2X2P-2.54-REVERSE")
      (footprint "eagle-import:2X2P-2.54-REVERSE")
      (libsource (lib "eagle-import") (part "CONNECTOR-HEADER-2X2P2X2P-2.54-REVERSE"))
    )
    (comp (ref "J124")
      (value "CONNECTOR-HEADER-2X2P2X2P-2.54-REVERSE")
      (footprint "eagle-import:2X2P-2.54-REVERSE")
      (libsource (lib "eagle-import") (part "CONNECTOR-HEADER-2X2P2X2P-2.54-REVERSE"))
    )
    (comp (ref "J125")
      (value "CONNECTOR-HEADER-2X2P2X2P-2.54-REVERSE")
      (footprint "eagle-import:2X2P-2.54-REVERSE")
      (libsource (lib "eagle-import") (part "CONNECTOR-HEADER-2X2P2X2P-2.54-REVERSE"))
    )
    (comp (ref "J126")
      (value "CONNECTOR-HEADER-2X2P2X2P-2.54-REVERSE")
      (footprint "eagle-import:2X2P-2.54-REVERSE")
      (libsource (lib "eagle-import") (part "CONNECTOR-HEADER-2X2P2X2P-2.54-REVERSE"))
    )
    (comp (ref "J127")
      (value "CONNECTOR-HEADER-2X2P2X2P-2.54-REVERSE")
      (footprint "eagle-import:2X2P-2.54-REVERSE")
      (libsource (lib "eagle-import") (part "CONNECTOR-HEADER-2X2P2X2P-2.54-REVERSE"))
    )
    (comp (ref "J128")
      (value "CONNECTOR-HEADER-2X2P2X2P-2.54-REVERSE")
      (footprint "eagle-import:2X2P-2.54-REVERSE")
      (libsource (lib "eagle-import") (part "CONNECTOR-HEADER-2X2P2X2P-2.54-REVERSE"))
    )
    (comp (ref "J129")
      (value "CONNECTOR-HEADER-2X2P2X2P-2.54-REVERSE")
      (footprint "eagle-import:2X2P-2.54-REVERSE")
      (libsource (lib "eagle-import") (part "CONNECTOR-HEADER-2X2P2X2P-2.54-REVERSE"))
    )
    (comp (ref "J130")
      (value "CONNECTOR-HEADER-2X2P2X2P-2.54-REVERSE")
      (footprint "eagle-import:2X2P-2.54-REVERSE")
      (libsource (lib "eagle-import") (part "CONNECTOR-HEADER-2X2P2X2P-2.54-REVERSE"))
    )
    (comp (ref "J131")
      (value "CONNECTOR-HEADER-2X2P2X2P-2.54-REVERSE")
      (footprint "eagle-import:2X2P-2.54-REVERSE")
      (libsource (lib "eagle-import") (part "CONNECTOR-HEADER-2X2P2X2P-2.54-REVERSE"))
    )
    (comp (ref "J132")
      (value "CONNECTOR-HEADER-2X2P2X2P-2.54-REVERSE")
      (footprint "eagle-import:2X2P-2.54-REVERSE")
      (libsource (lib "eagle-import") (part "CONNECTOR-HEADER-2X2P2X2P-2.54-REVERSE"))
    )
    (comp (ref "J133")
      (value "CONNECTOR-HEADER-2X2P2X2P-2.54-REVERSE")
      (footprint "eagle-import:2X2P-2.54-REVERSE")
      (libsource (lib "eagle-import") (part "CONNECTOR-HEADER-2X2P2X2P-2.54-REVERSE"))
    )
    (comp (ref "J134")
      (value "CONNECTOR-HEADER-2X2P2X2P-2.54-REVERSE")
      (footprint "eagle-import:2X2P-2.54-REVERSE")
      (libsource (lib "eagle-import") (part "CONNECTOR-HEADER-2X2P2X2P-2.54-REVERSE"))
    )
    (comp (ref "J135")
      (value "CONNECTOR-HEADER-2X2P2X2P-2.54-REVERSE")
      (footprint "eagle-import:2X2P-2.54-REVERSE")
      (libsource (lib "eagle-import") (part "CONNECTOR-HEADER-2X2P2X2P-2.54-REVERSE"))
    )
    (comp (ref "J136")
      (value "CONNECTOR-HEADER-2X2P2X2P-2.54-REVERSE")
      (footprint "eagle-import:2X2P-2.54-REVERSE")
      (libsource (lib "eagle-import") (part "CONNECTOR-HEADER-2X2P2X2P-2.54-REVERSE"))
    )
    (comp (ref "J137")
      (value "CONNECTOR-HEADER-2X2P2X2P-2.54-REVERSE")
      (footprint "eagle-import:2X2P-2.54-REVERSE")
      (libsource (lib "eagle-import") (part "CONNECTOR-HEADER-2X2P2X2P-2.54-REVERSE"))
    )
    (comp (ref "J138")
      (value "CONNECTOR-HEADER-2X2P2X2P-2.54-REVERSE")
      (footprint "eagle-import:2X2P-2.54-REVERSE")
      (libsource (lib "eagle-import") (part "CONNECTOR-HEADER-2X2P2X2P-2.54-REVERSE"))
    )
    (comp (ref "J139")
      (value "CONNECTOR-HEADER-2X2P2X2P-2.54-REVERSE")
      (footprint "eagle-import:2X2P-2.54-REVERSE")
      (libsource (lib "eagle-import") (part "CONNECTOR-HEADER-2X2P2X2P-2.54-REVERSE"))
    )
    (comp (ref "J140")
      (value "CONNECTOR-HEADER-2X2P2X2P-2.54-REVERSE")
      (footprint "eagle-import:2X2P-2.54-REVERSE")
      (libsource (lib "eagle-import") (part "CONNECTOR-HEADER-2X2P2X2P-2.54-REVERSE"))
    )
    (comp (ref "J141")
      (value "CONNECTOR-HEADER-2X2P2X2P-2.54-REVERSE")
      (footprint "eagle-import:2X2P-2.54-REVERSE")
      (libsource (lib "eagle-import") (part "CONNECTOR-HEADER-2X2P2X2P-2.54-REVERSE"))
    )
    (comp (ref "J142")
      (value "CONNECTOR-HEADER-2X2P2X2P-2.54-REVERSE")
      (footprint "eagle-import:2X2P-2.54-REVERSE")
      (libsource (lib "eagle-import") (part "CONNECTOR-HEADER-2X2P2X2P-2.54-REVERSE"))
    )
    (comp (ref "J143")
      (value "CONNECTOR-HEADER-2X2P2X2P-2.54-REVERSE")
      (footprint "eagle-import:2X2P-2.54-REVERSE")
      (libsource (lib "eagle-import") (part "CONNECTOR-HEADER-2X2P2X2P-2.54-REVERSE"))
    )
    (comp (ref "J144")
      (value "CONNECTOR-HEADER-2X2P2X2P-2.54-REVERSE")
      (footprint "eagle-import:2X2P-2.54-REVERSE")
      (libsource (lib "eagle-import") (part "CONNECTOR-HEADER-2X2P2X2P-2.54-REVERSE"))
    )
    (comp (ref "J145")
      (value "CONNECTOR-HEADER-2X2P2X2P-2.54-REVERSE")
      (footprint "eagle-import:2X2P-2.54-REVERSE")
      (libsource (lib "eagle-import") (part "CONNECTOR-HEADER-2X2P2X2P-2.54-REVERSE"))
    )
    (comp (ref "J146")
      (value "CONNECTOR-HEADER-2X2P2X2P-2.54-REVERSE")
      (footprint "eagle-import:2X2P-2.54-REVERSE")
      (libsource (lib "eagle-import") (part "CONNECTOR-HEADER-2X2P2X2P-2.54-REVERSE"))
    )
    (comp (ref "J147")
      (value "CONNECTOR-HEADER-2X2P2X2P-2.54-REVERSE")
      (footprint "eagle-import:2X2P-2.54-REVERSE")
      (libsource (lib "eagle-import") (part "CONNECTOR-HEADER-2X2P2X2P-2.54-REVERSE"))
    )
    (comp (ref "J148")
      (value "CONNECTOR-HEADER-2X2P2X2P-2.54-REVERSE")
      (footprint "eagle-import:2X2P-2.54-REVERSE")
      (libsource (lib "eagle-import") (part "CONNECTOR-HEADER-2X2P2X2P-2.54-REVERSE"))
    )
    (comp (ref "J149")
      (value "CONNECTOR-HEADER-2X2P2X2P-2.54-REVERSE")
      (footprint "eagle-import:2X2P-2.54-REVERSE")
      (libsource (lib "eagle-import") (part "CONNECTOR-HEADER-2X2P2X2P-2.54-REVERSE"))
    )
    (comp (ref "J150")
      (value "CONNECTOR-HEADER-2X2P2X2P-2.54-REVERSE")
      (footprint "eagle-import:2X2P-2.54-REVERSE")
      (libsource (lib "eagle-import") (part "CONNECTOR-HEADER-2X2P2X2P-2.54-REVERSE"))
    )
    (comp (ref "J151")
      (value "CONNECTOR-HEADER-2X2P2X2P-2.54-REVERSE")
      (footprint "eagle-import:2X2P-2.54-REVERSE")
      (libsource (lib "eagle-import") (part "CONNECTOR-HEADER-2X2P2X2P-2.54-REVERSE"))
    )
    (comp (ref "J152")
      (value "CONNECTOR-HEADER-2X2P2X2P-2.54-REVERSE")
      (footprint "eagle-import:2X2P-2.54-REVERSE")
      (libsource (lib "eagle-import") (part "CONNECTOR-HEADER-2X2P2X2P-2.54-REVERSE"))
    )
    (comp (ref "J153")
      (value "CONNECTOR-HEADER-2X2P2X2P-2.54-REVERSE")
      (footprint "eagle-import:2X2P-2.54-REVERSE")
      (libsource (lib "eagle-import") (part "CONNECTOR-HEADER-2X2P2X2P-2.54-REVERSE"))
    )
    (comp (ref "J154")
      (value "CONNECTOR-HEADER-2X2P2X2P-2.54-REVERSE")
      (footprint "eagle-import:2X2P-2.54-REVERSE")
      (libsource (lib "eagle-import") (part "CONNECTOR-HEADER-2X2P2X2P-2.54-REVERSE"))
    )
    (comp (ref "J155")
      (value "CONNECTOR-HEADER-2X2P2X2P-2.54-REVERSE")
      (footprint "eagle-import:2X2P-2.54-REVERSE")
      (libsource (lib "eagle-import") (part "CONNECTOR-HEADER-2X2P2X2P-2.54-REVERSE"))
    )
    (comp (ref "J156")
      (value "CONNECTOR-HEADER-2X2P2X2P-2.54-REVERSE")
      (footprint "eagle-import:2X2P-2.54-REVERSE")
      (libsource (lib "eagle-import") (part "CONNECTOR-HEADER-2X2P2X2P-2.54-REVERSE"))
    )
    (comp (ref "J157")
      (value "CONNECTOR-HEADER-2X2P2X2P-2.54-REVERSE")
      (footprint "eagle-import:2X2P-2.54-REVERSE")
      (libsource (lib "eagle-import") (part "CONNECTOR-HEADER-2X2P2X2P-2.54-REVERSE"))
    )
    (comp (ref "J158")
      (value "CONNECTOR-HEADER-2X2P2X2P-2.54-REVERSE")
      (footprint "eagle-import:2X2P-2.54-REVERSE")
      (libsource (lib "eagle-import") (part "CONNECTOR-HEADER-2X2P2X2P-2.54-REVERSE"))
    )
    (comp (ref "J159")
      (value "CONNECTOR-HEADER-2X2P2X2P-2.54-REVERSE")
      (footprint "eagle-import:2X2P-2.54-REVERSE")
      (libsource (lib "eagle-import") (part "CONNECTOR-HEADER-2X2P2X2P-2.54-REVERSE"))
    )
    (comp (ref "J160")
      (value "CONNECTOR-HEADER-2X2P2X2P-2.54-REVERSE")
      (footprint "eagle-import:2X2P-2.54-REVERSE")
      (libsource (lib "eagle-import") (part "CONNECTOR-HEADER-2X2P2X2P-2.54-REVERSE"))
    )
    (comp (ref "J161")
      (value "CONNECTOR-HEADER-2X2P2X2P-2.54-REVERSE")
      (footprint "eagle-import:2X2P-2.54-REVERSE")
      (libsource (lib "eagle-import") (part "CONNECTOR-HEADER-2X2P2X2P-2.54-REVERSE"))
    )
    (comp (ref "J162")
      (value "CONNECTOR-HEADER-2X2P2X2P-2.54-REVERSE")
      (footprint "eagle-import:2X2P-2.54-REVERSE")
      (libsource (lib "eagle-import") (part "CONNECTOR-HEADER-2X2P2X2P-2.54-REVERSE"))
    )
    (comp (ref "J163")
      (value "CONNECTOR-HEADER-2X2P2X2P-2.54-REVERSE")
      (footprint "eagle-import:2X2P-2.54-REVERSE")
      (libsource (lib "eagle-import") (part "CONNECTOR-HEADER-2X2P2X2P-2.54-REVERSE"))
    )
    (comp (ref "J164")
      (value "CONNECTOR-HEADER-2X2P2X2P-2.54-REVERSE")
      (footprint "eagle-import:2X2P-2.54-REVERSE")
      (libsource (lib "eagle-import") (part "CONNECTOR-HEADER-2X2P2X2P-2.54-REVERSE"))
    )
    (comp (ref "J165")
      (value "CONNECTOR-HEADER-2X2P2X2P-2.54-REVERSE")
      (footprint "eagle-import:2X2P-2.54-REVERSE")
      (libsource (lib "eagle-import") (part "CONNECTOR-HEADER-2X2P2X2P-2.54-REVERSE"))
    )
    (comp (ref "J166")
      (value "CONNECTOR-HEADER-2X2P2X2P-2.54-REVERSE")
      (footprint "eagle-import:2X2P-2.54-REVERSE")
      (libsource (lib "eagle-import") (part "CONNECTOR-HEADER-2X2P2X2P-2.54-REVERSE"))
    )
    (comp (ref "J167")
      (value "CONNECTOR-HEADER-2X2P2X2P-2.54-REVERSE")
      (footprint "eagle-import:2X2P-2.54-REVERSE")
      (libsource (lib "eagle-import") (part "CONNECTOR-HEADER-2X2P2X2P-2.54-REVERSE"))
    )
    (comp (ref "J168")
      (value "CONNECTOR-HEADER-2X2P2X2P-2.54-REVERSE")
      (footprint "eagle-import:2X2P-2.54-REVERSE")
      (libsource (lib "eagle-import") (part "CONNECTOR-HEADER-2X2P2X2P-2.54-REVERSE"))
    )
    (comp (ref "J169")
      (value "CONNECTOR-HEADER-2X2P2X2P-2.54-REVERSE")
      (footprint "eagle-import:2X2P-2.54-REVERSE")
      (libsource (lib "eagle-import") (part "CONNECTOR-HEADER-2X2P2X2P-2.54-REVERSE"))
    )
    (comp (ref "J170")
      (value "CONNECTOR-HEADER-2X2P2X2P-2.54-REVERSE")
      (footprint "eagle-import:2X2P-2.54-REVERSE")
      (libsource (lib "eagle-import") (part "CONNECTOR-HEADER-2X2P2X2P-2.54-REVERSE"))
    )
    (comp (ref "J171")
      (value "CONNECTOR-HEADER-2X2P2X2P-2.54-REVERSE")
      (footprint "eagle-import:2X2P-2.54-REVERSE")
      (libsource (lib "eagle-import") (part "CONNECTOR-HEADER-2X2P2X2P-2.54-REVERSE"))
    )
    (comp (ref "J172")
      (value "CONNECTOR-HEADER-2X2P2X2P-2.54-REVERSE")
      (footprint "eagle-import:2X2P-2.54-REVERSE")
      (libsource (lib "eagle-import") (part "CONNECTOR-HEADER-2X2P2X2P-2.54-REVERSE"))
    )
    (comp (ref "J173")
      (value "CONNECTOR-HEADER-2X2P2X2P-2.54-REVERSE")
      (footprint "eagle-import:2X2P-2.54-REVERSE")
      (libsource (lib "eagle-import") (part "CONNECTOR-HEADER-2X2P2X2P-2.54-REVERSE"))
    )
    (comp (ref "J174")
      (value "CONNECTOR-HEADER-2X2P2X2P-2.54-REVERSE")
      (footprint "eagle-import:2X2P-2.54-REVERSE")
      (libsource (lib "eagle-import") (part "CONNECTOR-HEADER-2X2P2X2P-2.54-REVERSE"))
    )
    (comp (ref "J175")
      (value "CONNECTOR-HEADER-2X2P2X2P-2.54-REVERSE")
      (footprint "eagle-import:2X2P-2.54-REVERSE")
      (libsource (lib "eagle-import") (part "CONNECTOR-HEADER-2X2P2X2P-2.54-REVERSE"))
    )
    (comp (ref "J176")
      (value "CONNECTOR-HEADER-2X2P2X2P-2.54-REVERSE")
      (footprint "eagle-import:2X2P-2.54-REVERSE")
      (libsource (lib "eagle-import") (part "CONNECTOR-HEADER-2X2P2X2P-2.54-REVERSE"))
    )
    (comp (ref "J177")
      (value "CONNECTOR-HEADER-2X2P2X2P-2.54-REVERSE")
      (footprint "eagle-import:2X2P-2.54-REVERSE")
      (libsource (lib "eagle-import") (part "CONNECTOR-HEADER-2X2P2X2P-2.54-REVERSE"))
    )
    (comp (ref "J178")
      (value "CONNECTOR-HEADER-2X2P2X2P-2.54-REVERSE")
      (footprint "eagle-import:2X2P-2.54-REVERSE")
      (libsource (lib "eagle-import") (part "CONNECTOR-HEADER-2X2P2X2P-2.54-REVERSE"))
    )
    (comp (ref "J179")
      (value "CONNECTOR-HEADER-2X2P2X2P-2.54-REVERSE")
      (footprint "eagle-import:2X2P-2.54-REVERSE")
      (libsource (lib "eagle-import") (part "CONNECTOR-HEADER-2X2P2X2P-2.54-REVERSE"))
    )
    (comp (ref "J180")
      (value "CONNECTOR-HEADER-2X2P2X2P-2.54-REVERSE")
      (footprint "eagle-import:2X2P-2.54-REVERSE")
      (libsource (lib "eagle-import") (part "CONNECTOR-HEADER-2X2P2X2P-2.54-REVERSE"))
    )
    (comp (ref "J181")
      (value "CONNECTOR-HEADER-2X2P2X2P-2.54-REVERSE")
      (footprint "eagle-import:2X2P-2.54-REVERSE")
      (libsource (lib "eagle-import") (part "CONNECTOR-HEADER-2X2P2X2P-2.54-REVERSE"))
    )
    (comp (ref "J182")
      (value "CONNECTOR-HEADER-2X2P2X2P-2.54-REVERSE")
      (footprint "eagle-import:2X2P-2.54-REVERSE")
      (libsource (lib "eagle-import") (part "CONNECTOR-HEADER-2X2P2X2P-2.54-REVERSE"))
    )
    (comp (ref "J183")
      (value "CONNECTOR-HEADER-2X2P2X2P-2.54-REVERSE")
      (footprint "eagle-import:2X2P-2.54-REVERSE")
      (libsource (lib "eagle-import") (part "CONNECTOR-HEADER-2X2P2X2P-2.54-REVERSE"))
    )
    (comp (ref "J184")
      (value "CONNECTOR-HEADER-2X2P2X2P-2.54-REVERSE")
      (footprint "eagle-import:2X2P-2.54-REVERSE")
      (libsource (lib "eagle-import") (part "CONNECTOR-HEADER-2X2P2X2P-2.54-REVERSE"))
    )
    (comp (ref "J185")
      (value "CONNECTOR-HEADER-2X2P2X2P-2.54-REVERSE")
      (footprint "eagle-import:2X2P-2.54-REVERSE")
      (libsource (lib "eagle-import") (part "CONNECTOR-HEADER-2X2P2X2P-2.54-REVERSE"))
    )
    (comp (ref "J186")
      (value "CONNECTOR-HEADER-2X2P2X2P-2.54-REVERSE")
      (footprint "eagle-import:2X2P-2.54-REVERSE")
      (libsource (lib "eagle-import") (part "CONNECTOR-HEADER-2X2P2X2P-2.54-REVERSE"))
    )
    (comp (ref "J187")
      (value "CONNECTOR-HEADER-2X2P2X2P-2.54-REVERSE")
      (footprint "eagle-import:2X2P-2.54-REVERSE")
      (libsource (lib "eagle-import") (part "CONNECTOR-HEADER-2X2P2X2P-2.54-REVERSE"))
    )
    (comp (ref "J188")
      (value "CONNECTOR-HEADER-2X2P2X2P-2.54-REVERSE")
      (footprint "eagle-import:2X2P-2.54-REVERSE")
      (libsource (lib "eagle-import") (part "CONNECTOR-HEADER-2X2P2X2P-2.54-REVERSE"))
    )
    (comp (ref "J189")
      (value "CONNECTOR-HEADER-2X2P2X2P-2.54-REVERSE")
      (footprint "eagle-import:2X2P-2.54-REVERSE")
      (libsource (lib "eagle-import") (part "CONNECTOR-HEADER-2X2P2X2P-2.54-REVERSE"))
    )
    (comp (ref "J190")
      (value "CONNECTOR-HEADER-2X2P2X2P-2.54-REVERSE")
      (footprint "eagle-import:2X2P-2.54-REVERSE")
      (libsource (lib "eagle-import") (part "CONNECTOR-HEADER-2X2P2X2P-2.54-REVERSE"))
    )
    (comp (ref "J191")
      (value "CONNECTOR-HEADER-2X2P2X2P-2.54-REVERSE")
      (footprint "eagle-import:2X2P-2.54-REVERSE")
      (libsource (lib "eagle-import") (part "CONNECTOR-HEADER-2X2P2X2P-2.54-REVERSE"))
    )
    (comp (ref "J192")
      (value "CONNECTOR-HEADER-2X2P2X2P-2.54-REVERSE")
      (footprint "eagle-import:2X2P-2.54-REVERSE")
      (libsource (lib "eagle-import") (part "CONNECTOR-HEADER-2X2P2X2P-2.54-REVERSE"))
    )
    (comp (ref "J193")
      (value "CONNECTOR-HEADER-2X2P2X2P-2.54-REVERSE")
      (footprint "eagle-import:2X2P-2.54-REVERSE")
      (libsource (lib "eagle-import") (part "CONNECTOR-HEADER-2X2P2X2P-2.54-REVERSE"))
    )
    (comp (ref "J194")
      (value "CONNECTOR-HEADER-2X2P2X2P-2.54-REVERSE")
      (footprint "eagle-import:2X2P-2.54-REVERSE")
      (libsource (lib "eagle-import") (part "CONNECTOR-HEADER-2X2P2X2P-2.54-REVERSE"))
    )
    (comp (ref "J195")
      (value "CONNECTOR-HEADER-2X2P2X2P-2.54-REVERSE")
      (footprint "eagle-import:2X2P-2.54-REVERSE")
      (libsource (lib "eagle-import") (part "CONNECTOR-HEADER-2X2P2X2P-2.54-REVERSE"))
    )
    (comp (ref "J196")
      (value "CONNECTOR-HEADER-2X2P2X2P-2.54-REVERSE")
      (footprint "eagle-import:2X2P-2.54-REVERSE")
      (libsource (lib "eagle-import") (part "CONNECTOR-HEADER-2X2P2X2P-2.54-REVERSE"))
    )
    (comp (ref "J197")
      (value "CONNECTOR-HEADER-2X2P2X2P-2.54-REVERSE")
      (footprint "eagle-import:2X2P-2.54-REVERSE")
      (libsource (lib "eagle-import") (part "CONNECTOR-HEADER-2X2P2X2P-2.54-REVERSE"))
    )
    (comp (ref "J198")
      (value "CONNECTOR-HEADER-2X2P2X2P-2.54-REVERSE")
      (footprint "eagle-import:2X2P-2.54-REVERSE")
      (libsource (lib "eagle-import") (part "CONNECTOR-HEADER-2X2P2X2P-2.54-REVERSE"))
    )
    (comp (ref "J199")
      (value "CONNECTOR-HEADER-2X2P2X2P-2.54-REVERSE")
      (footprint "eagle-import:2X2P-2.54-REVERSE")
      (libsource (lib "eagle-import") (part "CONNECTOR-HEADER-2X2P2X2P-2.54-REVERSE"))
    )
    (comp (ref "J200")
      (value "CONNECTOR-HEADER-2X2P2X2P-2.54-REVERSE")
      (footprint "eagle-import:2X2P-2.54-REVERSE")
      (libsource (lib "eagle-import") (part "CONNECTOR-HEADER-2X2P2X2P-2.54-REVERSE"))
    )
    (comp (ref "J201")
      (value "CONNECTOR-HEADER-2X2P2X2P-2.54-REVERSE")
      (footprint "eagle-import:2X2P-2.54-REVERSE")
      (libsource (lib "eagle-import") (part "CONNECTOR-HEADER-2X2P2X2P-2.54-REVERSE"))
    )
    (comp (ref "J202")
      (value "CONNECTOR-HEADER-2X2P2X2P-2.54-REVERSE")
      (footprint "eagle-import:2X2P-2.54-REVERSE")
      (libsource (lib "eagle-import") (part "CONNECTOR-HEADER-2X2P2X2P-2.54-REVERSE"))
    )
    (comp (ref "J203")
      (value "CONNECTOR-HEADER-2X2P2X2P-2.54-REVERSE")
      (footprint "eagle-import:2X2P-2.54-REVERSE")
      (libsource (lib "eagle-import") (part "CONNECTOR-HEADER-2X2P2X2P-2.54-REVERSE"))
    )
    (comp (ref "J204")
      (value "CONNECTOR-HEADER-2X2P2X2P-2.54-REVERSE")
      (footprint "eagle-import:2X2P-2.54-REVERSE")
      (libsource (lib "eagle-import") (part "CONNECTOR-HEADER-2X2P2X2P-2.54-REVERSE"))
    )
    (comp (ref "J205")
      (value "CONNECTOR-HEADER-2X2P2X2P-2.54-REVERSE")
      (footprint "eagle-import:2X2P-2.54-REVERSE")
      (libsource (lib "eagle-import") (part "CONNECTOR-HEADER-2X2P2X2P-2.54-REVERSE"))
    )
    (comp (ref "J206")
      (value "CONNECTOR-HEADER-2X2P2X2P-2.54-REVERSE")
      (footprint "eagle-import:2X2P-2.54-REVERSE")
      (libsource (lib "eagle-import") (part "CONNECTOR-HEADER-2X2P2X2P-2.54-REVERSE"))
    )
    (comp (ref "J207")
      (value "CONNECTOR-HEADER-2X2P2X2P-2.54-REVERSE")
      (footprint "eagle-import:2X2P-2.54-REVERSE")
      (libsource (lib "eagle-import") (part "CONNECTOR-HEADER-2X2P2X2P-2.54-REVERSE"))
    )
    (comp (ref "J208")
      (value "CONNECTOR-HEADER-2X2P2X2P-2.54-REVERSE")
      (footprint "eagle-import:2X2P-2.54-REVERSE")
      (libsource (lib "eagle-import") (part "CONNECTOR-HEADER-2X2P2X2P-2.54-REVERSE"))
    )
    (comp (ref "J209")
      (value "CONNECTOR-HEADER-2X2P2X2P-2.54-REVERSE")
      (footprint "eagle-import:2X2P-2.54-REVERSE")
      (libsource (lib "eagle-import") (part "CONNECTOR-HEADER-2X2P2X2P-2.54-REVERSE"))
    )
    (comp (ref "J210")
      (value "CONNECTOR-HEADER-2X2P2X2P-2.54-REVERSE")
      (footprint "eagle-import:2X2P-2.54-REVERSE")
      (libsource (lib "eagle-import") (part "CONNECTOR-HEADER-2X2P2X2P-2.54-REVERSE"))
    )
    (comp (ref "J211")
      (value "CONNECTOR-HEADER-2X2P2X2P-2.54-REVERSE")
      (footprint "eagle-import:2X2P-2.54-REVERSE")
      (libsource (lib "eagle-import") (part "CONNECTOR-HEADER-2X2P2X2P-2.54-REVERSE"))
    )
    (comp (ref "J212")
      (value "CONNECTOR-HEADER-2X2P2X2P-2.54-REVERSE")
      (footprint "eagle-import:2X2P-2.54-REVERSE")
      (libsource (lib "eagle-import") (part "CONNECTOR-HEADER-2X2P2X2P-2.54-REVERSE"))
    )
    (comp (ref "J213")
      (value "CONNECTOR-HEADER-2X2P2X2P-2.54-REVERSE")
      (footprint "eagle-import:2X2P-2.54-REVERSE")
      (libsource (lib "eagle-import") (part "CONNECTOR-HEADER-2X2P2X2P-2.54-REVERSE"))
    )
    (comp (ref "J214")
      (value "CONNECTOR-HEADER-2X2P2X2P-2.54-REVERSE")
      (footprint "eagle-import:2X2P-2.54-REVERSE")
      (libsource (lib "eagle-import") (part "CONNECTOR-HEADER-2X2P2X2P-2.54-REVERSE"))
    )
    (comp (ref "J215")
      (value "CONNECTOR-HEADER-2X2P2X2P-2.54-REVERSE")
      (footprint "eagle-import:2X2P-2.54-REVERSE")
      (libsource (lib "eagle-import") (part "CONNECTOR-HEADER-2X2P2X2P-2.54-REVERSE"))
    )
    (comp (ref "J216")
      (value "CONNECTOR-HEADER-2X2P2X2P-2.54-REVERSE")
      (footprint "eagle-import:2X2P-2.54-REVERSE")
      (libsource (lib "eagle-import") (part "CONNECTOR-HEADER-2X2P2X2P-2.54-REVERSE"))
    )
    (comp (ref "J217")
      (value "CONNECTOR-HEADER-2X2P2X2P-2.54-REVERSE")
      (footprint "eagle-import:2X2P-2.54-REVERSE")
      (libsource (lib "eagle-import") (part "CONNECTOR-HEADER-2X2P2X2P-2.54-REVERSE"))
    )
    (comp (ref "J218")
      (value "CONNECTOR-HEADER-2X2P2X2P-2.54-REVERSE")
      (footprint "eagle-import:2X2P-2.54-REVERSE")
      (libsource (lib "eagle-import") (part "CONNECTOR-HEADER-2X2P2X2P-2.54-REVERSE"))
    )
    (comp (ref "J219")
      (value "CONNECTOR-HEADER-2X2P2X2P-2.54-REVERSE")
      (footprint "eagle-import:2X2P-2.54-REVERSE")
      (libsource (lib "eagle-import") (part "CONNECTOR-HEADER-2X2P2X2P-2.54-REVERSE"))
    )
    (comp (ref "J220")
      (value "CONNECTOR-HEADER-2X2P2X2P-2.54-REVERSE")
      (footprint "eagle-import:2X2P-2.54-REVERSE")
      (libsource (lib "eagle-import") (part "CONNECTOR-HEADER-2X2P2X2P-2.54-REVERSE"))
    )
    (comp (ref "J221")
      (value "CONNECTOR-HEADER-2X2P2X2P-2.54-REVERSE")
      (footprint "eagle-import:2X2P-2.54-REVERSE")
      (libsource (lib "eagle-import") (part "CONNECTOR-HEADER-2X2P2X2P-2.54-REVERSE"))
    )
    (comp (ref "J222")
      (value "CONNECTOR-HEADER-2X2P2X2P-2.54-REVERSE")
      (footprint "eagle-import:2X2P-2.54-REVERSE")
      (libsource (lib "eagle-import") (part "CONNECTOR-HEADER-2X2P2X2P-2.54-REVERSE"))
    )
    (comp (ref "J223")
      (value "CONNECTOR-HEADER-2X2P2X2P-2.54-REVERSE")
      (footprint "eagle-import:2X2P-2.54-REVERSE")
      (libsource (lib "eagle-import") (part "CONNECTOR-HEADER-2X2P2X2P-2.54-REVERSE"))
    )
    (comp (ref "J224")
      (value "CONNECTOR-HEADER-2X2P2X2P-2.54-REVERSE")
      (footprint "eagle-import:2X2P-2.54-REVERSE")
      (libsource (lib "eagle-import") (part "CONNECTOR-HEADER-2X2P2X2P-2.54-REVERSE"))
    )
    (comp (ref "J225")
      (value "CONNECTOR-HEADER-2X2P2X2P-2.54-REVERSE")
      (footprint "eagle-import:2X2P-2.54-REVERSE")
      (libsource (lib "eagle-import") (part "CONNECTOR-HEADER-2X2P2X2P-2.54-REVERSE"))
    )
    (comp (ref "J226")
      (value "CONNECTOR-HEADER-2X2P2X2P-2.54-REVERSE")
      (footprint "eagle-import:2X2P-2.54-REVERSE")
      (libsource (lib "eagle-import") (part "CONNECTOR-HEADER-2X2P2X2P-2.54-REVERSE"))
    )
    (comp (ref "J227")
      (value "CONNECTOR-HEADER-2X2P2X2P-2.54-REVERSE")
      (footprint "eagle-import:2X2P-2.54-REVERSE")
      (libsource (lib "eagle-import") (part "CONNECTOR-HEADER-2X2P2X2P-2.54-REVERSE"))
    )
    (comp (ref "J228")
      (value "CONNECTOR-HEADER-2X2P2X2P-2.54-REVERSE")
      (footprint "eagle-import:2X2P-2.54-REVERSE")
      (libsource (lib "eagle-import") (part "CONNECTOR-HEADER-2X2P2X2P-2.54-REVERSE"))
    )
    (comp (ref "J229")
      (value "CONNECTOR-HEADER-2X2P2X2P-2.54-REVERSE")
      (footprint "eagle-import:2X2P-2.54-REVERSE")
      (libsource (lib "eagle-import") (part "CONNECTOR-HEADER-2X2P2X2P-2.54-REVERSE"))
    )
    (comp (ref "J230")
      (value "CONNECTOR-HEADER-2X2P2X2P-2.54-REVERSE")
      (footprint "eagle-import:2X2P-2.54-REVERSE")
      (libsource (lib "eagle-import") (part "CONNECTOR-HEADER-2X2P2X2P-2.54-REVERSE"))
    )
    (comp (ref "J231")
      (value "CONNECTOR-HEADER-2X2P2X2P-2.54-REVERSE")
      (footprint "eagle-import:2X2P-2.54-REVERSE")
      (libsource (lib "eagle-import") (part "CONNECTOR-HEADER-2X2P2X2P-2.54-REVERSE"))
    )
    (comp (ref "J232")
      (value "CONNECTOR-HEADER-2X2P2X2P-2.54-REVERSE")
      (footprint "eagle-import:2X2P-2.54-REVERSE")
      (libsource (lib "eagle-import") (part "CONNECTOR-HEADER-2X2P2X2P-2.54-REVERSE"))
    )
    (comp (ref "J233")
      (value "CONNECTOR-HEADER-2X2P2X2P-2.54-REVERSE")
      (footprint "eagle-import:2X2P-2.54-REVERSE")
      (libsource (lib "eagle-import") (part "CONNECTOR-HEADER-2X2P2X2P-2.54-REVERSE"))
    )
    (comp (ref "J234")
      (value "CONNECTOR-HEADER-2X2P2X2P-2.54-REVERSE")
      (footprint "eagle-import:2X2P-2.54-REVERSE")
      (libsource (lib "eagle-import") (part "CONNECTOR-HEADER-2X2P2X2P-2.54-REVERSE"))
    )
    (comp (ref "J235")
      (value "CONNECTOR-HEADER-2X2P2X2P-2.54-REVERSE")
      (footprint "eagle-import:2X2P-2.54-REVERSE")
      (libsource (lib "eagle-import") (part "CONNECTOR-HEADER-2X2P2X2P-2.54-REVERSE"))
    )
    (comp (ref "J236")
      (value "CONNECTOR-HEADER-2X2P2X2P-2.54-REVERSE")
      (footprint "eagle-import:2X2P-2.54-REVERSE")
      (libsource (lib "eagle-import") (part "CONNECTOR-HEADER-2X2P2X2P-2.54-REVERSE"))
    )
    (comp (ref "J237")
      (value "CONNECTOR-HEADER-2X2P2X2P-2.54-REVERSE")
      (footprint "eagle-import:2X2P-2.54-REVERSE")
      (libsource (lib "eagle-import") (part "CONNECTOR-HEADER-2X2P2X2P-2.54-REVERSE"))
    )
    (comp (ref "J238")
      (value "CONNECTOR-HEADER-2X2P2X2P-2.54-REVERSE")
      (footprint "eagle-import:2X2P-2.54-REVERSE")
      (libsource (lib "eagle-import") (part "CONNECTOR-HEADER-2X2P2X2P-2.54-REVERSE"))
    )
    (comp (ref "J239")
      (value "CONNECTOR-HEADER-2X2P2X2P-2.54-REVERSE")
      (footprint "eagle-import:2X2P-2.54-REVERSE")
      (libsource (lib "eagle-import") (part "CONNECTOR-HEADER-2X2P2X2P-2.54-REVERSE"))
    )
    (comp (ref "J240")
      (value "CONNECTOR-HEADER-2X2P2X2P-2.54-REVERSE")
      (footprint "eagle-import:2X2P-2.54-REVERSE")
      (libsource (lib "eagle-import") (part "CONNECTOR-HEADER-2X2P2X2P-2.54-REVERSE"))
    )
    (comp (ref "J241")
      (value "CONNECTOR-HEADER-2X2P2X2P-2.54-REVERSE")
      (footprint "eagle-import:2X2P-2.54-REVERSE")
      (libsource (lib "eagle-import") (part "CONNECTOR-HEADER-2X2P2X2P-2.54-REVERSE"))
    )
    (comp (ref "J242")
      (value "CONNECTOR-HEADER-2X2P2X2P-2.54-REVERSE")
      (footprint "eagle-import:2X2P-2.54-REVERSE")
      (libsource (lib "eagle-import") (part "CONNECTOR-HEADER-2X2P2X2P-2.54-REVERSE"))
    )
    (comp (ref "J243")
      (value "CONNECTOR-HEADER-2X2P2X2P-2.54-REVERSE")
      (footprint "eagle-import:2X2P-2.54-REVERSE")
      (libsource (lib "eagle-import") (part "CONNECTOR-HEADER-2X2P2X2P-2.54-REVERSE"))
    )
    (comp (ref "J244")
      (value "CONNECTOR-HEADER-2X2P2X2P-2.54-REVERSE")
      (footprint "eagle-import:2X2P-2.54-REVERSE")
      (libsource (lib "eagle-import") (part "CONNECTOR-HEADER-2X2P2X2P-2.54-REVERSE"))
    )
    (comp (ref "J245")
      (value "CONNECTOR-HEADER-2X2P2X2P-2.54-REVERSE")
      (footprint "eagle-import:2X2P-2.54-REVERSE")
      (libsource (lib "eagle-import") (part "CONNECTOR-HEADER-2X2P2X2P-2.54-REVERSE"))
    )
    (comp (ref "J246")
      (value "CONNECTOR-HEADER-2X2P2X2P-2.54-REVERSE")
      (footprint "eagle-import:2X2P-2.54-REVERSE")
      (libsource (lib "eagle-import") (part "CONNECTOR-HEADER-2X2P2X2P-2.54-REVERSE"))
    )
    (comp (ref "J247")
      (value "CONNECTOR-HEADER-2X2P2X2P-2.54-REVERSE")
      (footprint "eagle-import:2X2P-2.54-REVERSE")
      (libsource (lib "eagle-import") (part "CONNECTOR-HEADER-2X2P2X2P-2.54-REVERSE"))
    )
    (comp (ref "J248")
      (value "CONNECTOR-HEADER-2X2P2X2P-2.54-REVERSE")
      (footprint "eagle-import:2X2P-2.54-REVERSE")
      (libsource (lib "eagle-import") (part "CONNECTOR-HEADER-2X2P2X2P-2.54-REVERSE"))
    )
    (comp (ref "J249")
      (value "CONNECTOR-HEADER-2X2P2X2P-2.54-REVERSE")
      (footprint "eagle-import:2X2P-2.54-REVERSE")
      (libsource (lib "eagle-import") (part "CONNECTOR-HEADER-2X2P2X2P-2.54-REVERSE"))
    )
    (comp (ref "J250")
      (value "CONNECTOR-HEADER-2X2P2X2P-2.54-REVERSE")
      (footprint "eagle-import:2X2P-2.54-REVERSE")
      (libsource (lib "eagle-import") (part "CONNECTOR-HEADER-2X2P2X2P-2.54-REVERSE"))
    )
    (comp (ref "J251")
      (value "CONNECTOR-HEADER-2X2P2X2P-2.54-REVERSE")
      (footprint "eagle-import:2X2P-2.54-REVERSE")
      (libsource (lib "eagle-import") (part "CONNECTOR-HEADER-2X2P2X2P-2.54-REVERSE"))
    )
    (comp (ref "J252")
      (value "CONNECTOR-HEADER-2X2P2X2P-2.54-REVERSE")
      (footprint "eagle-import:2X2P-2.54-REVERSE")
      (libsource (lib "eagle-import") (part "CONNECTOR-HEADER-2X2P2X2P-2.54-REVERSE"))
    )
    (comp (ref "J253")
      (value "CONNECTOR-HEADER-2X2P2X2P-2.54-REVERSE")
      (footprint "eagle-import:2X2P-2.54-REVERSE")
      (libsource (lib "eagle-import") (part "CONNECTOR-HEADER-2X2P2X2P-2.54-REVERSE"))
    )
    (comp (ref "J254")
      (value "CONNECTOR-HEADER-2X2P2X2P-2.54-REVERSE")
      (footprint "eagle-import:2X2P-2.54-REVERSE")
      (libsource (lib "eagle-import") (part "CONNECTOR-HEADER-2X2P2X2P-2.54-REVERSE"))
    )
    (comp (ref "J255")
      (value "CONNECTOR-HEADER-2X2P2X2P-2.54-REVERSE")
      (footprint "eagle-import:2X2P-2.54-REVERSE")
      (libsource (lib "eagle-import") (part "CONNECTOR-HEADER-2X2P2X2P-2.54-REVERSE"))
    )
    (comp (ref "J256")
      (value "CONNECTOR-HEADER-2X2P2X2P-2.54-REVERSE")
      (footprint "eagle-import:2X2P-2.54-REVERSE")
      (libsource (lib "eagle-import") (part "CONNECTOR-HEADER-2X2P2X2P-2.54-REVERSE"))
    )
  )
  (nets
    (net (code "1") (name "DIN_1") (class "Default")
      (node (ref "D-IN") (pin "1") (pinfunction "1_1") (pintype "bidirectional"))
      (node (ref "J1") (pin "2") (pinfunction "2_2") (pintype "bidirectional"))
    )
    (net (code "2") (name "DIN_2") (class "Default")
      (node (ref "D-IN") (pin "2") (pinfunction "2_2") (pintype "bidirectional"))
      (node (ref "J65") (pin "2") (pinfunction "2_2") (pintype "bidirectional"))
    )
    (net (code "3") (name "DIN_3") (class "Default")
      (node (ref "D-IN") (pin "3") (pinfunction "3_3") (pintype "bidirectional"))
      (node (ref "J129") (pin "2") (pinfunction "2_2") (pintype "bidirectional"))
    )
    (net (code "4") (name "DIN_4") (class "Default")
      (node (ref "D-IN") (pin "4") (pinfunction "4_4") (pintype "bidirectional"))
      (node (ref "J193") (pin "2") (pinfunction "2_2") (pintype "bidirectional"))
    )
    (net (code "5") (name "GND") (class "Default")
      (node (ref "C1") (pin "-") (pinfunction "2_-") (pintype "bidirectional"))
      (node (ref "C2") (pin "-") (pinfunction "2_-") (pintype "bidirectional"))
      (node (ref "C3") (pin "-") (pinfunction "2_-") (pintype "bidirectional"))
      (node (ref "C4") (pin "-") (pinfunction "2_-") (pintype "bidirectional"))
      (node (ref "C5") (pin "1") (pinfunction "1_1") (pintype "bidirectional"))
      (node (ref "C6") (pin "1") (pinfunction "1_1") (pintype "bidirectional"))
      (node (ref "C7") (pin "1") (pinfunction "1_1") (pintype "bidirectional"))
      (node (ref "C8") (pin "1") (pinfunction "1_1") (pintype "bidirectional"))
      (node (ref "D-IN") (pin "5") (pinfunction "5_5") (pintype "bidirectional"))
      (node (ref "D-IN") (pin "6") (pinfunction "6_6") (pintype "bidirectional"))
      (node (ref "DC") (pin "-1") (pinfunction "-_-1") (pintype "bidirectional"))
      (node (ref "DC") (pin "-2") (pinfunction "CDN_-2") (pintype "bidirectional"))
      (node (ref "DC") (pin "P$1") (pinfunction "-_P$1") (pintype "bidirectional"))
      (node (ref "DC") (pin "P$10") (pinfunction "-_P$10") (pintype "bidirectional"))
      (node (ref "DC") (pin "P$11") (pinfunction "-_P$11") (pintype "bidirectional"))
      (node (ref "DC") (pin "P$12") (pinfunction "-_P$12") (pintype "bidirectional"))
      (node (ref "DC") (pin "P$13") (pinfunction "-_P$13") (pintype "bidirectional"))
      (node (ref "DC") (pin "P$14") (pinfunction "-_P$14") (pintype "bidirectional"))
      (node (ref "DC") (pin "P$15") (pinfunction "-_P$15") (pintype "bidirectional"))
      (node (ref "DC") (pin "P$16") (pinfunction "-_P$16") (pintype "bidirectional"))
      (node (ref "DC") (pin "P$17") (pinfunction "-_P$17") (pintype "bidirectional"))
      (node (ref "DC") (pin "P$18") (pinfunction "-_P$18") (pintype "bidirectional"))
      (node (ref "DC") (pin "P$2") (pinfunction "-_P$2") (pintype "bidirectional"))
      (node (ref "DC") (pin "P$3") (pinfunction "-_P$3") (pintype "bidirectional"))
      (node (ref "DC") (pin "P$4") (pinfunction "-_P$4") (pintype "bidirectional"))
      (node (ref "DC") (pin "P$40") (pinfunction "CDN_P$40") (pintype "bidirectional"))
      (node (ref "DC") (pin "P$41") (pinfunction "CDN_P$41") (pintype "bidirectional"))
      (node (ref "DC") (pin "P$42") (pinfunction "CDN_P$42") (pintype "bidirectional"))
      (node (ref "DC") (pin "P$43") (pinfunction "CDN_P$43") (pintype "bidirectional"))
      (node (ref "DC") (pin "P$44") (pinfunction "CDN_P$44") (pintype "bidirectional"))
      (node (ref "DC") (pin "P$45") (pinfunction "CDN_P$45") (pintype "bidirectional"))
      (node (ref "DC") (pin "P$46") (pinfunction "CDN_P$46") (pintype "bidirectional"))
      (node (ref "DC") (pin "P$47") (pinfunction "CDN_P$47") (pintype "bidirectional"))
      (node (ref "DC") (pin "P$48") (pinfunction "CDN_P$48") (pintype "bidirectional"))
      (node (ref "DC") (pin "P$49") (pinfunction "CDN_P$49") (pintype "bidirectional"))
      (node (ref "DC") (pin "P$5") (pinfunction "-_P$5") (pintype "bidirectional"))
      (node (ref "DC") (pin "P$50") (pinfunction "CDN_P$50") (pintype "bidirectional"))
      (node (ref "DC") (pin "P$51") (pinfunction "CDN_P$51") (pintype "bidirectional"))
      (node (ref "DC") (pin "P$52") (pinfunction "CDN_P$52") (pintype "bidirectional"))
      (node (ref "DC") (pin "P$53") (pinfunction "CDN_P$53") (pintype "bidirectional"))
      (node (ref "DC") (pin "P$54") (pinfunction "CDN_P$54") (pintype "bidirectional"))
      (node (ref "DC") (pin "P$55") (pinfunction "CDN_P$55") (pintype "bidirectional"))
      (node (ref "DC") (pin "P$56") (pinfunction "CDN_P$56") (pintype "bidirectional"))
      (node (ref "DC") (pin "P$57") (pinfunction "CDN_P$57") (pintype "bidirectional"))
      (node (ref "DC") (pin "P$58") (pinfunction "CDN_P$58") (pintype "bidirectional"))
      (node (ref "DC") (pin "P$59") (pinfunction "CDN_P$59") (pintype "bidirectional"))
      (node (ref "DC") (pin "P$6") (pinfunction "-_P$6") (pintype "bidirectional"))
      (node (ref "DC") (pin "P$60") (pinfunction "-_P$60") (pintype "bidirectional"))
      (node (ref "DC") (pin "P$61") (pinfunction "-_P$61") (pintype "bidirectional"))
      (node (ref "DC") (pin "P$7") (pinfunction "-_P$7") (pintype "bidirectional"))
      (node (ref "DC") (pin "P$8") (pinfunction "-_P$8") (pintype "bidirectional"))
      (node (ref "DC") (pin "P$9") (pinfunction "-_P$9") (pintype "bidirectional"))
      (node (ref "J1") (pin "4") (pinfunction "4_4") (pintype "bidirectional"))
      (node (ref "J10") (pin "4") (pinfunction "4_4") (pintype "bidirectional"))
      (node (ref "J100") (pin "4") (pinfunction "4_4") (pintype "bidirectional"))
      (node (ref "J101") (pin "4") (pinfunction "4_4") (pintype "bidirectional"))
      (node (ref "J102") (pin "4") (pinfunction "4_4") (pintype "bidirectional"))
      (node (ref "J103") (pin "4") (pinfunction "4_4") (pintype "bidirectional"))
      (node (ref "J104") (pin "4") (pinfunction "4_4") (pintype "bidirectional"))
      (node (ref "J105") (pin "4") (pinfunction "4_4") (pintype "bidirectional"))
      (node (ref "J106") (pin "4") (pinfunction "4_4") (pintype "bidirectional"))
      (node (ref "J107") (pin "4") (pinfunction "4_4") (pintype "bidirectional"))
      (node (ref "J108") (pin "4") (pinfunction "4_4") (pintype "bidirectional"))
      (node (ref "J109") (pin "4") (pinfunction "4_4") (pintype "bidirectional"))
      (node (ref "J11") (pin "4") (pinfunction "4_4") (pintype "bidirectional"))
      (node (ref "J110") (pin "4") (pinfunction "4_4") (pintype "bidirectional"))
      (node (ref "J111") (pin "4") (pinfunction "4_4") (pintype "bidirectional"))
      (node (ref "J112") (pin "4") (pinfunction "4_4") (pintype "bidirectional"))
      (node (ref "J113") (pin "4") (pinfunction "4_4") (pintype "bidirectional"))
      (node (ref "J114") (pin "4") (pinfunction "4_4") (pintype "bidirectional"))
      (node (ref "J115") (pin "4") (pinfunction "4_4") (pintype "bidirectional"))
      (node (ref "J116") (pin "4") (pinfunction "4_4") (pintype "bidirectional"))
      (node (ref "J117") (pin "4") (pinfunction "4_4") (pintype "bidirectional"))
      (node (ref "J118") (pin "4") (pinfunction "4_4") (pintype "bidirectional"))
      (node (ref "J119") (pin "4") (pinfunction "4_4") (pintype "bidirectional"))
      (node (ref "J12") (pin "4") (pinfunction "4_4") (pintype "bidirectional"))
      (node (ref "J120") (pin "4") (pinfunction "4_4") (pintype "bidirectional"))
      (node (ref "J121") (pin "4") (pinfunction "4_4") (pintype "bidirectional"))
      (node (ref "J122") (pin "4") (pinfunction "4_4") (pintype "bidirectional"))
      (node (ref "J123") (pin "4") (pinfunction "4_4") (pintype "bidirectional"))
      (node (ref "J124") (pin "4") (pinfunction "4_4") (pintype "bidirectional"))
      (node (ref "J125") (pin "4") (pinfunction "4_4") (pintype "bidirectional"))
      (node (ref "J126") (pin "4") (pinfunction "4_4") (pintype "bidirectional"))
      (node (ref "J127") (pin "4") (pinfunction "4_4") (pintype "bidirectional"))
      (node (ref "J128") (pin "4") (pinfunction "4_4") (pintype "bidirectional"))
      (node (ref "J129") (pin "4") (pinfunction "4_4") (pintype "bidirectional"))
      (node (ref "J13") (pin "4") (pinfunction "4_4") (pintype "bidirectional"))
      (node (ref "J130") (pin "4") (pinfunction "4_4") (pintype "bidirectional"))
      (node (ref "J131") (pin "4") (pinfunction "4_4") (pintype "bidirectional"))
      (node (ref "J132") (pin "4") (pinfunction "4_4") (pintype "bidirectional"))
      (node (ref "J133") (pin "4") (pinfunction "4_4") (pintype "bidirectional"))
      (node (ref "J134") (pin "4") (pinfunction "4_4") (pintype "bidirectional"))
      (node (ref "J135") (pin "4") (pinfunction "4_4") (pintype "bidirectional"))
      (node (ref "J136") (pin "4") (pinfunction "4_4") (pintype "bidirectional"))
      (node (ref "J137") (pin "4") (pinfunction "4_4") (pintype "bidirectional"))
      (node (ref "J138") (pin "4") (pinfunction "4_4") (pintype "bidirectional"))
      (node (ref "J139") (pin "4") (pinfunction "4_4") (pintype "bidirectional"))
      (node (ref "J14") (pin "4") (pinfunction "4_4") (pintype "bidirectional"))
      (node (ref "J140") (pin "4") (pinfunction "4_4") (pintype "bidirectional"))
      (node (ref "J141") (pin "4") (pinfunction "4_4") (pintype "bidirectional"))
      (node (ref "J142") (pin "4") (pinfunction "4_4") (pintype "bidirectional"))
      (node (ref "J143") (pin "4") (pinfunction "4_4") (pintype "bidirectional"))
      (node (ref "J144") (pin "4") (pinfunction "4_4") (pintype "bidirectional"))
      (node (ref "J145") (pin "4") (pinfunction "4_4") (pintype "bidirectional"))
      (node (ref "J146") (pin "4") (pinfunction "4_4") (pintype "bidirectional"))
      (node (ref "J147") (pin "4") (pinfunction "4_4") (pintype "bidirectional"))
      (node (ref "J148") (pin "4") (pinfunction "4_4") (pintype "bidirectional"))
      (node (ref "J149") (pin "4") (pinfunction "4_4") (pintype "bidirectional"))
      (node (ref "J15") (pin "4") (pinfunction "4_4") (pintype "bidirectional"))
      (node (ref "J150") (pin "4") (pinfunction "4_4") (pintype "bidirectional"))
      (node (ref "J151") (pin "4") (pinfunction "4_4") (pintype "bidirectional"))
      (node (ref "J152") (pin "4") (pinfunction "4_4") (pintype "bidirectional"))
      (node (ref "J153") (pin "4") (pinfunction "4_4") (pintype "bidirectional"))
      (node (ref "J154") (pin "4") (pinfunction "4_4") (pintype "bidirectional"))
      (node (ref "J155") (pin "4") (pinfunction "4_4") (pintype "bidirectional"))
      (node (ref "J156") (pin "4") (pinfunction "4_4") (pintype "bidirectional"))
      (node (ref "J157") (pin "4") (pinfunction "4_4") (pintype "bidirectional"))
      (node (ref "J158") (pin "4") (pinfunction "4_4") (pintype "bidirectional"))
      (node (ref "J159") (pin "4") (pinfunction "4_4") (pintype "bidirectional"))
      (node (ref "J16") (pin "4") (pinfunction "4_4") (pintype "bidirectional"))
      (node (ref "J160") (pin "4") (pinfunction "4_4") (pintype "bidirectional"))
      (node (ref "J161") (pin "4") (pinfunction "4_4") (pintype "bidirectional"))
      (node (ref "J162") (pin "4") (pinfunction "4_4") (pintype "bidirectional"))
      (node (ref "J163") (pin "4") (pinfunction "4_4") (pintype "bidirectional"))
      (node (ref "J164") (pin "4") (pinfunction "4_4") (pintype "bidirectional"))
      (node (ref "J165") (pin "4") (pinfunction "4_4") (pintype "bidirectional"))
      (node (ref "J166") (pin "4") (pinfunction "4_4") (pintype "bidirectional"))
      (node (ref "J167") (pin "4") (pinfunction "4_4") (pintype "bidirectional"))
      (node (ref "J168") (pin "4") (pinfunction "4_4") (pintype "bidirectional"))
      (node (ref "J169") (pin "4") (pinfunction "4_4") (pintype "bidirectional"))
      (node (ref "J17") (pin "4") (pinfunction "4_4") (pintype "bidirectional"))
      (node (ref "J170") (pin "4") (pinfunction "4_4") (pintype "bidirectional"))
      (node (ref "J171") (pin "4") (pinfunction "4_4") (pintype "bidirectional"))
      (node (ref "J172") (pin "4") (pinfunction "4_4") (pintype "bidirectional"))
      (node (ref "J173") (pin "4") (pinfunction "4_4") (pintype "bidirectional"))
      (node (ref "J174") (pin "4") (pinfunction "4_4") (pintype "bidirectional"))
      (node (ref "J175") (pin "4") (pinfunction "4_4") (pintype "bidirectional"))
      (node (ref "J176") (pin "4") (pinfunction "4_4") (pintype "bidirectional"))
      (node (ref "J177") (pin "4") (pinfunction "4_4") (pintype "bidirectional"))
      (node (ref "J178") (pin "4") (pinfunction "4_4") (pintype "bidirectional"))
      (node (ref "J179") (pin "4") (pinfunction "4_4") (pintype "bidirectional"))
      (node (ref "J18") (pin "4") (pinfunction "4_4") (pintype "bidirectional"))
      (node (ref "J180") (pin "4") (pinfunction "4_4") (pintype "bidirectional"))
      (node (ref "J181") (pin "4") (pinfunction "4_4") (pintype "bidirectional"))
      (node (ref "J182") (pin "4") (pinfunction "4_4") (pintype "bidirectional"))
      (node (ref "J183") (pin "4") (pinfunction "4_4") (pintype "bidirectional"))
      (node (ref "J184") (pin "4") (pinfunction "4_4") (pintype "bidirectional"))
      (node (ref "J185") (pin "4") (pinfunction "4_4") (pintype "bidirectional"))
      (node (ref "J186") (pin "4") (pinfunction "4_4") (pintype "bidirectional"))
      (node (ref "J187") (pin "4") (pinfunction "4_4") (pintype "bidirectional"))
      (node (ref "J188") (pin "4") (pinfunction "4_4") (pintype "bidirectional"))
      (node (ref "J189") (pin "4") (pinfunction "4_4") (pintype "bidirectional"))
      (node (ref "J19") (pin "4") (pinfunction "4_4") (pintype "bidirectional"))
      (node (ref "J190") (pin "4") (pinfunction "4_4") (pintype "bidirectional"))
      (node (ref "J191") (pin "4") (pinfunction "4_4") (pintype "bidirectional"))
      (node (ref "J192") (pin "4") (pinfunction "4_4") (pintype "bidirectional"))
      (node (ref "J193") (pin "4") (pinfunction "4_4") (pintype "bidirectional"))
      (node (ref "J194") (pin "4") (pinfunction "4_4") (pintype "bidirectional"))
      (node (ref "J195") (pin "4") (pinfunction "4_4") (pintype "bidirectional"))
      (node (ref "J196") (pin "4") (pinfunction "4_4") (pintype "bidirectional"))
      (node (ref "J197") (pin "4") (pinfunction "4_4") (pintype "bidirectional"))
      (node (ref "J198") (pin "4") (pinfunction "4_4") (pintype "bidirectional"))
      (node (ref "J199") (pin "4") (pinfunction "4_4") (pintype "bidirectional"))
      (node (ref "J2") (pin "4") (pinfunction "4_4") (pintype "bidirectional"))
      (node (ref "J20") (pin "4") (pinfunction "4_4") (pintype "bidirectional"))
      (node (ref "J200") (pin "4") (pinfunction "4_4") (pintype "bidirectional"))
      (node (ref "J201") (pin "4") (pinfunction "4_4") (pintype "bidirectional"))
      (node (ref "J202") (pin "4") (pinfunction "4_4") (pintype "bidirectional"))
      (node (ref "J203") (pin "4") (pinfunction "4_4") (pintype "bidirectional"))
      (node (ref "J204") (pin "4") (pinfunction "4_4") (pintype "bidirectional"))
      (node (ref "J205") (pin "4") (pinfunction "4_4") (pintype "bidirectional"))
      (node (ref "J206") (pin "4") (pinfunction "4_4") (pintype "bidirectional"))
      (node (ref "J207") (pin "4") (pinfunction "4_4") (pintype "bidirectional"))
      (node (ref "J208") (pin "4") (pinfunction "4_4") (pintype "bidirectional"))
      (node (ref "J209") (pin "4") (pinfunction "4_4") (pintype "bidirectional"))
      (node (ref "J21") (pin "4") (pinfunction "4_4") (pintype "bidirectional"))
      (node (ref "J210") (pin "4") (pinfunction "4_4") (pintype "bidirectional"))
      (node (ref "J211") (pin "4") (pinfunction "4_4") (pintype "bidirectional"))
      (node (ref "J212") (pin "4") (pinfunction "4_4") (pintype "bidirectional"))
      (node (ref "J213") (pin "4") (pinfunction "4_4") (pintype "bidirectional"))
      (node (ref "J214") (pin "4") (pinfunction "4_4") (pintype "bidirectional"))
      (node (ref "J215") (pin "4") (pinfunction "4_4") (pintype "bidirectional"))
      (node (ref "J216") (pin "4") (pinfunction "4_4") (pintype "bidirectional"))
      (node (ref "J217") (pin "4") (pinfunction "4_4") (pintype "bidirectional"))
      (node (ref "J218") (pin "4") (pinfunction "4_4") (pintype "bidirectional"))
      (node (ref "J219") (pin "4") (pinfunction "4_4") (pintype "bidirectional"))
      (node (ref "J22") (pin "4") (pinfunction "4_4") (pintype "bidirectional"))
      (node (ref "J220") (pin "4") (pinfunction "4_4") (pintype "bidirectional"))
      (node (ref "J221") (pin "4") (pinfunction "4_4") (pintype "bidirectional"))
      (node (ref "J222") (pin "4") (pinfunction "4_4") (pintype "bidirectional"))
      (node (ref "J223") (pin "4") (pinfunction "4_4") (pintype "bidirectional"))
      (node (ref "J224") (pin "4") (pinfunction "4_4") (pintype "bidirectional"))
      (node (ref "J225") (pin "4") (pinfunction "4_4") (pintype "bidirectional"))
      (node (ref "J226") (pin "4") (pinfunction "4_4") (pintype "bidirectional"))
      (node (ref "J227") (pin "4") (pinfunction "4_4") (pintype "bidirectional"))
      (node (ref "J228") (pin "4") (pinfunction "4_4") (pintype "bidirectional"))
      (node (ref "J229") (pin "4") (pinfunction "4_4") (pintype "bidirectional"))
      (node (ref "J23") (pin "4") (pinfunction "4_4") (pintype "bidirectional"))
      (node (ref "J230") (pin "4") (pinfunction "4_4") (pintype "bidirectional"))
      (node (ref "J231") (pin "4") (pinfunction "4_4") (pintype "bidirectional"))
      (node (ref "J232") (pin "4") (pinfunction "4_4") (pintype "bidirectional"))
      (node (ref "J233") (pin "4") (pinfunction "4_4") (pintype "bidirectional"))
      (node (ref "J234") (pin "4") (pinfunction "4_4") (pintype "bidirectional"))
      (node (ref "J235") (pin "4") (pinfunction "4_4") (pintype "bidirectional"))
      (node (ref "J236") (pin "4") (pinfunction "4_4") (pintype "bidirectional"))
      (node (ref "J237") (pin "4") (pinfunction "4_4") (pintype "bidirectional"))
      (node (ref "J238") (pin "4") (pinfunction "4_4") (pintype "bidirectional"))
      (node (ref "J239") (pin "4") (pinfunction "4_4") (pintype "bidirectional"))
      (node (ref "J24") (pin "4") (pinfunction "4_4") (pintype "bidirectional"))
      (node (ref "J240") (pin "4") (pinfunction "4_4") (pintype "bidirectional"))
      (node (ref "J241") (pin "4") (pinfunction "4_4") (pintype "bidirectional"))
      (node (ref "J242") (pin "4") (pinfunction "4_4") (pintype "bidirectional"))
      (node (ref "J243") (pin "4") (pinfunction "4_4") (pintype "bidirectional"))
      (node (ref "J244") (pin "4") (pinfunction "4_4") (pintype "bidirectional"))
      (node (ref "J245") (pin "4") (pinfunction "4_4") (pintype "bidirectional"))
      (node (ref "J246") (pin "4") (pinfunction "4_4") (pintype "bidirectional"))
      (node (ref "J247") (pin "4") (pinfunction "4_4") (pintype "bidirectional"))
      (node (ref "J248") (pin "4") (pinfunction "4_4") (pintype "bidirectional"))
      (node (ref "J249") (pin "4") (pinfunction "4_4") (pintype "bidirectional"))
      (node (ref "J25") (pin "4") (pinfunction "4_4") (pintype "bidirectional"))
      (node (ref "J250") (pin "4") (pinfunction "4_4") (pintype "bidirectional"))
      (node (ref "J251") (pin "4") (pinfunction "4_4") (pintype "bidirectional"))
      (node (ref "J252") (pin "4") (pinfunction "4_4") (pintype "bidirectional"))
      (node (ref "J253") (pin "4") (pinfunction "4_4") (pintype "bidirectional"))
      (node (ref "J254") (pin "4") (pinfunction "4_4") (pintype "bidirectional"))
      (node (ref "J255") (pin "4") (pinfunction "4_4") (pintype "bidirectional"))
      (node (ref "J256") (pin "4") (pinfunction "4_4") (pintype "bidirectional"))
      (node (ref "J26") (pin "4") (pinfunction "4_4") (pintype "bidirectional"))
      (node (ref "J27") (pin "4") (pinfunction "4_4") (pintype "bidirectional"))
      (node (ref "J28") (pin "4") (pinfunction "4_4") (pintype "bidirectional"))
      (node (ref "J29") (pin "4") (pinfunction "4_4") (pintype "bidirectional"))
      (node (ref "J3") (pin "4") (pinfunction "4_4") (pintype "bidirectional"))
      (node (ref "J30") (pin "4") (pinfunction "4_4") (pintype "bidirectional"))
      (node (ref "J31") (pin "4") (pinfunction "4_4") (pintype "bidirectional"))
      (node (ref "J32") (pin "4") (pinfunction "4_4") (pintype "bidirectional"))
      (node (ref "J33") (pin "4") (pinfunction "4_4") (pintype "bidirectional"))
      (node (ref "J34") (pin "4") (pinfunction "4_4") (pintype "bidirectional"))
      (node (ref "J35") (pin "4") (pinfunction "4_4") (pintype "bidirectional"))
      (node (ref "J36") (pin "4") (pinfunction "4_4") (pintype "bidirectional"))
      (node (ref "J37") (pin "4") (pinfunction "4_4") (pintype "bidirectional"))
      (node (ref "J38") (pin "4") (pinfunction "4_4") (pintype "bidirectional"))
      (node (ref "J39") (pin "4") (pinfunction "4_4") (pintype "bidirectional"))
      (node (ref "J4") (pin "4") (pinfunction "4_4") (pintype "bidirectional"))
      (node (ref "J40") (pin "4") (pinfunction "4_4") (pintype "bidirectional"))
      (node (ref "J41") (pin "4") (pinfunction "4_4") (pintype "bidirectional"))
      (node (ref "J42") (pin "4") (pinfunction "4_4") (pintype "bidirectional"))
      (node (ref "J43") (pin "4") (pinfunction "4_4") (pintype "bidirectional"))
      (node (ref "J44") (pin "4") (pinfunction "4_4") (pintype "bidirectional"))
      (node (ref "J45") (pin "4") (pinfunction "4_4") (pintype "bidirectional"))
      (node (ref "J46") (pin "4") (pinfunction "4_4") (pintype "bidirectional"))
      (node (ref "J47") (pin "4") (pinfunction "4_4") (pintype "bidirectional"))
      (node (ref "J48") (pin "4") (pinfunction "4_4") (pintype "bidirectional"))
      (node (ref "J49") (pin "4") (pinfunction "4_4") (pintype "bidirectional"))
      (node (ref "J5") (pin "4") (pinfunction "4_4") (pintype "bidirectional"))
      (node (ref "J50") (pin "4") (pinfunction "4_4") (pintype "bidirectional"))
      (node (ref "J51") (pin "4") (pinfunction "4_4") (pintype "bidirectional"))
      (node (ref "J52") (pin "4") (pinfunction "4_4") (pintype "bidirectional"))
      (node (ref "J53") (pin "4") (pinfunction "4_4") (pintype "bidirectional"))
      (node (ref "J54") (pin "4") (pinfunction "4_4") (pintype "bidirectional"))
      (node (ref "J55") (pin "4") (pinfunction "4_4") (pintype "bidirectional"))
      (node (ref "J56") (pin "4") (pinfunction "4_4") (pintype "bidirectional"))
      (node (ref "J57") (pin "4") (pinfunction "4_4") (pintype "bidirectional"))
      (node (ref "J58") (pin "4") (pinfunction "4_4") (pintype "bidirectional"))
      (node (ref "J59") (pin "4") (pinfunction "4_4") (pintype "bidirectional"))
      (node (ref "J6") (pin "4") (pinfunction "4_4") (pintype "bidirectional"))
      (node (ref "J60") (pin "4") (pinfunction "4_4") (pintype "bidirectional"))
      (node (ref "J61") (pin "4") (pinfunction "4_4") (pintype "bidirectional"))
      (node (ref "J62") (pin "4") (pinfunction "4_4") (pintype "bidirectional"))
      (node (ref "J63") (pin "4") (pinfunction "4_4") (pintype "bidirectional"))
      (node (ref "J64") (pin "4") (pinfunction "4_4") (pintype "bidirectional"))
      (node (ref "J65") (pin "4") (pinfunction "4_4") (pintype "bidirectional"))
      (node (ref "J66") (pin "4") (pinfunction "4_4") (pintype "bidirectional"))
      (node (ref "J67") (pin "4") (pinfunction "4_4") (pintype "bidirectional"))
      (node (ref "J68") (pin "4") (pinfunction "4_4") (pintype "bidirectional"))
      (node (ref "J69") (pin "4") (pinfunction "4_4") (pintype "bidirectional"))
      (node (ref "J7") (pin "4") (pinfunction "4_4") (pintype "bidirectional"))
      (node (ref "J70") (pin "4") (pinfunction "4_4") (pintype "bidirectional"))
      (node (ref "J71") (pin "4") (pinfunction "4_4") (pintype "bidirectional"))
      (node (ref "J72") (pin "4") (pinfunction "4_4") (pintype "bidirectional"))
      (node (ref "J73") (pin "4") (pinfunction "4_4") (pintype "bidirectional"))
      (node (ref "J74") (pin "4") (pinfunction "4_4") (pintype "bidirectional"))
      (node (ref "J75") (pin "4") (pinfunction "4_4") (pintype "bidirectional"))
      (node (ref "J76") (pin "4") (pinfunction "4_4") (pintype "bidirectional"))
      (node (ref "J77") (pin "4") (pinfunction "4_4") (pintype "bidirectional"))
      (node (ref "J78") (pin "4") (pinfunction "4_4") (pintype "bidirectional"))
      (node (ref "J79") (pin "4") (pinfunction "4_4") (pintype "bidirectional"))
      (node (ref "J8") (pin "4") (pinfunction "4_4") (pintype "bidirectional"))
      (node (ref "J80") (pin "4") (pinfunction "4_4") (pintype "bidirectional"))
      (node (ref "J81") (pin "4") (pinfunction "4_4") (pintype "bidirectional"))
      (node (ref "J82") (pin "4") (pinfunction "4_4") (pintype "bidirectional"))
      (node (ref "J83") (pin "4") (pinfunction "4_4") (pintype "bidirectional"))
      (node (ref "J84") (pin "4") (pinfunction "4_4") (pintype "bidirectional"))
      (node (ref "J85") (pin "4") (pinfunction "4_4") (pintype "bidirectional"))
      (node (ref "J86") (pin "4") (pinfunction "4_4") (pintype "bidirectional"))
      (node (ref "J87") (pin "4") (pinfunction "4_4") (pintype "bidirectional"))
      (node (ref "J88") (pin "4") (pinfunction "4_4") (pintype "bidirectional"))
      (node (ref "J89") (pin "4") (pinfunction "4_4") (pintype "bidirectional"))
      (node (ref "J9") (pin "4") (pinfunction "4_4") (pintype "bidirectional"))
      (node (ref "J90") (pin "4") (pinfunction "4_4") (pintype "bidirectional"))
      (node (ref "J91") (pin "4") (pinfunction "4_4") (pintype "bidirectional"))
      (node (ref "J92") (pin "4") (pinfunction "4_4") (pintype "bidirectional"))
      (node (ref "J93") (pin "4") (pinfunction "4_4") (pintype "bidirectional"))
      (node (ref "J94") (pin "4") (pinfunction "4_4") (pintype "bidirectional"))
      (node (ref "J95") (pin "4") (pinfunction "4_4") (pintype "bidirectional"))
      (node (ref "J96") (pin "4") (pinfunction "4_4") (pintype "bidirectional"))
      (node (ref "J97") (pin "4") (pinfunction "4_4") (pintype "bidirectional"))
      (node (ref "J98") (pin "4") (pinfunction "4_4") (pintype "bidirectional"))
      (node (ref "J99") (pin "4") (pinfunction "4_4") (pintype "bidirectional"))
    )
    (net (code "6") (name "Net-(J1-Pad3)") (class "Default")
      (node (ref "J1") (pin "3") (pinfunction "3_3") (pintype "bidirectional"))
      (node (ref "J2") (pin "2") (pinfunction "2_2") (pintype "bidirectional"))
    )
    (net (code "7") (name "Net-(J2-Pad3)") (class "Default")
      (node (ref "J2") (pin "3") (pinfunction "3_3") (pintype "bidirectional"))
      (node (ref "J3") (pin "2") (pinfunction "2_2") (pintype "bidirectional"))
    )
    (net (code "8") (name "Net-(J3-Pad3)") (class "Default")
      (node (ref "J3") (pin "3") (pinfunction "3_3") (pintype "bidirectional"))
      (node (ref "J4") (pin "2") (pinfunction "2_2") (pintype "bidirectional"))
    )
    (net (code "9") (name "Net-(J4-Pad3)") (class "Default")
      (node (ref "J4") (pin "3") (pinfunction "3_3") (pintype "bidirectional"))
      (node (ref "J5") (pin "2") (pinfunction "2_2") (pintype "bidirectional"))
    )
    (net (code "10") (name "Net-(J5-Pad3)") (class "Default")
      (node (ref "J5") (pin "3") (pinfunction "3_3") (pintype "bidirectional"))
      (node (ref "J6") (pin "2") (pinfunction "2_2") (pintype "bidirectional"))
    )
    (net (code "11") (name "Net-(J6-Pad3)") (class "Default")
      (node (ref "J6") (pin "3") (pinfunction "3_3") (pintype "bidirectional"))
      (node (ref "J7") (pin "2") (pinfunction "2_2") (pintype "bidirectional"))
    )
    (net (code "12") (name "Net-(J7-Pad3)") (class "Default")
      (node (ref "J7") (pin "3") (pinfunction "3_3") (pintype "bidirectional"))
      (node (ref "J8") (pin "2") (pinfunction "2_2") (pintype "bidirectional"))
    )
    (net (code "13") (name "Net-(J8-Pad3)") (class "Default")
      (node (ref "J8") (pin "3") (pinfunction "3_3") (pintype "bidirectional"))
      (node (ref "J9") (pin "2") (pinfunction "2_2") (pintype "bidirectional"))
    )
    (net (code "14") (name "Net-(J10-Pad2)") (class "Default")
      (node (ref "J10") (pin "2") (pinfunction "2_2") (pintype "bidirectional"))
      (node (ref "J9") (pin "3") (pinfunction "3_3") (pintype "bidirectional"))
    )
    (net (code "15") (name "Net-(J10-Pad3)") (class "Default")
      (node (ref "J10") (pin "3") (pinfunction "3_3") (pintype "bidirectional"))
      (node (ref "J11") (pin "2") (pinfunction "2_2") (pintype "bidirectional"))
    )
    (net (code "16") (name "Net-(J11-Pad3)") (class "Default")
      (node (ref "J11") (pin "3") (pinfunction "3_3") (pintype "bidirectional"))
      (node (ref "J12") (pin "2") (pinfunction "2_2") (pintype "bidirectional"))
    )
    (net (code "17") (name "Net-(J12-Pad3)") (class "Default")
      (node (ref "J12") (pin "3") (pinfunction "3_3") (pintype "bidirectional"))
      (node (ref "J13") (pin "2") (pinfunction "2_2") (pintype "bidirectional"))
    )
    (net (code "18") (name "Net-(J13-Pad3)") (class "Default")
      (node (ref "J13") (pin "3") (pinfunction "3_3") (pintype "bidirectional"))
      (node (ref "J14") (pin "2") (pinfunction "2_2") (pintype "bidirectional"))
    )
    (net (code "19") (name "Net-(J14-Pad3)") (class "Default")
      (node (ref "J14") (pin "3") (pinfunction "3_3") (pintype "bidirectional"))
      (node (ref "J15") (pin "2") (pinfunction "2_2") (pintype "bidirectional"))
    )
    (net (code "20") (name "Net-(J15-Pad3)") (class "Default")
      (node (ref "J15") (pin "3") (pinfunction "3_3") (pintype "bidirectional"))
      (node (ref "J16") (pin "2") (pinfunction "2_2") (pintype "bidirectional"))
    )
    (net (code "21") (name "Net-(J16-Pad3)") (class "Default")
      (node (ref "J16") (pin "3") (pinfunction "3_3") (pintype "bidirectional"))
      (node (ref "J17") (pin "2") (pinfunction "2_2") (pintype "bidirectional"))
    )
    (net (code "22") (name "Net-(J17-Pad3)") (class "Default")
      (node (ref "J17") (pin "3") (pinfunction "3_3") (pintype "bidirectional"))
      (node (ref "J18") (pin "2") (pinfunction "2_2") (pintype "bidirectional"))
    )
    (net (code "23") (name "Net-(J18-Pad3)") (class "Default")
      (node (ref "J18") (pin "3") (pinfunction "3_3") (pintype "bidirectional"))
      (node (ref "J19") (pin "2") (pinfunction "2_2") (pintype "bidirectional"))
    )
    (net (code "24") (name "Net-(J19-Pad3)") (class "Default")
      (node (ref "J19") (pin "3") (pinfunction "3_3") (pintype "bidirectional"))
      (node (ref "J20") (pin "2") (pinfunction "2_2") (pintype "bidirectional"))
    )
    (net (code "25") (name "Net-(J20-Pad3)") (class "Default")
      (node (ref "J20") (pin "3") (pinfunction "3_3") (pintype "bidirectional"))
      (node (ref "J21") (pin "2") (pinfunction "2_2") (pintype "bidirectional"))
    )
    (net (code "26") (name "Net-(J21-Pad3)") (class "Default")
      (node (ref "J21") (pin "3") (pinfunction "3_3") (pintype "bidirectional"))
      (node (ref "J22") (pin "2") (pinfunction "2_2") (pintype "bidirectional"))
    )
    (net (code "27") (name "Net-(J22-Pad3)") (class "Default")
      (node (ref "J22") (pin "3") (pinfunction "3_3") (pintype "bidirectional"))
      (node (ref "J23") (pin "2") (pinfunction "2_2") (pintype "bidirectional"))
    )
    (net (code "28") (name "Net-(J23-Pad3)") (class "Default")
      (node (ref "J23") (pin "3") (pinfunction "3_3") (pintype "bidirectional"))
      (node (ref "J24") (pin "2") (pinfunction "2_2") (pintype "bidirectional"))
    )
    (net (code "29") (name "Net-(J24-Pad3)") (class "Default")
      (node (ref "J24") (pin "3") (pinfunction "3_3") (pintype "bidirectional"))
      (node (ref "J25") (pin "2") (pinfunction "2_2") (pintype "bidirectional"))
    )
    (net (code "30") (name "Net-(J25-Pad3)") (class "Default")
      (node (ref "J25") (pin "3") (pinfunction "3_3") (pintype "bidirectional"))
      (node (ref "J26") (pin "2") (pinfunction "2_2") (pintype "bidirectional"))
    )
    (net (code "31") (name "Net-(J26-Pad3)") (class "Default")
      (node (ref "J26") (pin "3") (pinfunction "3_3") (pintype "bidirectional"))
      (node (ref "J27") (pin "2") (pinfunction "2_2") (pintype "bidirectional"))
    )
    (net (code "32") (name "Net-(J27-Pad3)") (class "Default")
      (node (ref "J27") (pin "3") (pinfunction "3_3") (pintype "bidirectional"))
      (node (ref "J28") (pin "2") (pinfunction "2_2") (pintype "bidirectional"))
    )
    (net (code "33") (name "Net-(J28-Pad3)") (class "Default")
      (node (ref "J28") (pin "3") (pinfunction "3_3") (pintype "bidirectional"))
      (node (ref "J29") (pin "2") (pinfunction "2_2") (pintype "bidirectional"))
    )
    (net (code "34") (name "Net-(J29-Pad3)") (class "Default")
      (node (ref "J29") (pin "3") (pinfunction "3_3") (pintype "bidirectional"))
      (node (ref "J30") (pin "2") (pinfunction "2_2") (pintype "bidirectional"))
    )
    (net (code "35") (name "Net-(J30-Pad3)") (class "Default")
      (node (ref "J30") (pin "3") (pinfunction "3_3") (pintype "bidirectional"))
      (node (ref "J31") (pin "2") (pinfunction "2_2") (pintype "bidirectional"))
    )
    (net (code "36") (name "Net-(J31-Pad3)") (class "Default")
      (node (ref "J31") (pin "3") (pinfunction "3_3") (pintype "bidirectional"))
      (node (ref "J32") (pin "2") (pinfunction "2_2") (pintype "bidirectional"))
    )
    (net (code "37") (name "Net-(J32-Pad3)") (class "Default")
      (node (ref "J32") (pin "3") (pinfunction "3_3") (pintype "bidirectional"))
      (node (ref "J33") (pin "2") (pinfunction "2_2") (pintype "bidirectional"))
    )
    (net (code "38") (name "Net-(J33-Pad3)") (class "Default")
      (node (ref "J33") (pin "3") (pinfunction "3_3") (pintype "bidirectional"))
      (node (ref "J34") (pin "2") (pinfunction "2_2") (pintype "bidirectional"))
    )
    (net (code "39") (name "Net-(J34-Pad3)") (class "Default")
      (node (ref "J34") (pin "3") (pinfunction "3_3") (pintype "bidirectional"))
      (node (ref "J35") (pin "2") (pinfunction "2_2") (pintype "bidirectional"))
    )
    (net (code "40") (name "Net-(J35-Pad3)") (class "Default")
      (node (ref "J35") (pin "3") (pinfunction "3_3") (pintype "bidirectional"))
      (node (ref "J36") (pin "2") (pinfunction "2_2") (pintype "bidirectional"))
    )
    (net (code "41") (name "Net-(J36-Pad3)") (class "Default")
      (node (ref "J36") (pin "3") (pinfunction "3_3") (pintype "bidirectional"))
      (node (ref "J37") (pin "2") (pinfunction "2_2") (pintype "bidirectional"))
    )
    (net (code "42") (name "Net-(J37-Pad3)") (class "Default")
      (node (ref "J37") (pin "3") (pinfunction "3_3") (pintype "bidirectional"))
      (node (ref "J38") (pin "2") (pinfunction "2_2") (pintype "bidirectional"))
    )
    (net (code "43") (name "Net-(J38-Pad3)") (class "Default")
      (node (ref "J38") (pin "3") (pinfunction "3_3") (pintype "bidirectional"))
      (node (ref "J39") (pin "2") (pinfunction "2_2") (pintype "bidirectional"))
    )
    (net (code "44") (name "Net-(J39-Pad3)") (class "Default")
      (node (ref "J39") (pin "3") (pinfunction "3_3") (pintype "bidirectional"))
      (node (ref "J40") (pin "2") (pinfunction "2_2") (pintype "bidirectional"))
    )
    (net (code "45") (name "Net-(J40-Pad3)") (class "Default")
      (node (ref "J40") (pin "3") (pinfunction "3_3") (pintype "bidirectional"))
      (node (ref "J41") (pin "2") (pinfunction "2_2") (pintype "bidirectional"))
    )
    (net (code "46") (name "Net-(J41-Pad3)") (class "Default")
      (node (ref "J41") (pin "3") (pinfunction "3_3") (pintype "bidirectional"))
      (node (ref "J42") (pin "2") (pinfunction "2_2") (pintype "bidirectional"))
    )
    (net (code "47") (name "Net-(J42-Pad3)") (class "Default")
      (node (ref "J42") (pin "3") (pinfunction "3_3") (pintype "bidirectional"))
      (node (ref "J43") (pin "2") (pinfunction "2_2") (pintype "bidirectional"))
    )
    (net (code "48") (name "Net-(J43-Pad3)") (class "Default")
      (node (ref "J43") (pin "3") (pinfunction "3_3") (pintype "bidirectional"))
      (node (ref "J44") (pin "2") (pinfunction "2_2") (pintype "bidirectional"))
    )
    (net (code "49") (name "Net-(J44-Pad3)") (class "Default")
      (node (ref "J44") (pin "3") (pinfunction "3_3") (pintype "bidirectional"))
      (node (ref "J45") (pin "2") (pinfunction "2_2") (pintype "bidirectional"))
    )
    (net (code "50") (name "Net-(J45-Pad3)") (class "Default")
      (node (ref "J45") (pin "3") (pinfunction "3_3") (pintype "bidirectional"))
      (node (ref "J46") (pin "2") (pinfunction "2_2") (pintype "bidirectional"))
    )
    (net (code "51") (name "Net-(J46-Pad3)") (class "Default")
      (node (ref "J46") (pin "3") (pinfunction "3_3") (pintype "bidirectional"))
      (node (ref "J47") (pin "2") (pinfunction "2_2") (pintype "bidirectional"))
    )
    (net (code "52") (name "Net-(J47-Pad3)") (class "Default")
      (node (ref "J47") (pin "3") (pinfunction "3_3") (pintype "bidirectional"))
      (node (ref "J48") (pin "2") (pinfunction "2_2") (pintype "bidirectional"))
    )
    (net (code "53") (name "Net-(J48-Pad3)") (class "Default")
      (node (ref "J48") (pin "3") (pinfunction "3_3") (pintype "bidirectional"))
      (node (ref "J49") (pin "2") (pinfunction "2_2") (pintype "bidirectional"))
    )
    (net (code "54") (name "Net-(J49-Pad3)") (class "Default")
      (node (ref "J49") (pin "3") (pinfunction "3_3") (pintype "bidirectional"))
      (node (ref "J50") (pin "2") (pinfunction "2_2") (pintype "bidirectional"))
    )
    (net (code "55") (name "Net-(J50-Pad3)") (class "Default")
      (node (ref "J50") (pin "3") (pinfunction "3_3") (pintype "bidirectional"))
      (node (ref "J51") (pin "2") (pinfunction "2_2") (pintype "bidirectional"))
    )
    (net (code "56") (name "Net-(J51-Pad3)") (class "Default")
      (node (ref "J51") (pin "3") (pinfunction "3_3") (pintype "bidirectional"))
      (node (ref "J52") (pin "2") (pinfunction "2_2") (pintype "bidirectional"))
    )
    (net (code "57") (name "Net-(J52-Pad3)") (class "Default")
      (node (ref "J52") (pin "3") (pinfunction "3_3") (pintype "bidirectional"))
      (node (ref "J53") (pin "2") (pinfunction "2_2") (pintype "bidirectional"))
    )
    (net (code "58") (name "Net-(J53-Pad3)") (class "Default")
      (node (ref "J53") (pin "3") (pinfunction "3_3") (pintype "bidirectional"))
      (node (ref "J54") (pin "2") (pinfunction "2_2") (pintype "bidirectional"))
    )
    (net (code "59") (name "Net-(J54-Pad3)") (class "Default")
      (node (ref "J54") (pin "3") (pinfunction "3_3") (pintype "bidirectional"))
      (node (ref "J55") (pin "2") (pinfunction "2_2") (pintype "bidirectional"))
    )
    (net (code "60") (name "Net-(J55-Pad3)") (class "Default")
      (node (ref "J55") (pin "3") (pinfunction "3_3") (pintype "bidirectional"))
      (node (ref "J56") (pin "2") (pinfunction "2_2") (pintype "bidirectional"))
    )
    (net (code "61") (name "Net-(J56-Pad3)") (class "Default")
      (node (ref "J56") (pin "3") (pinfunction "3_3") (pintype "bidirectional"))
      (node (ref "J57") (pin "2") (pinfunction "2_2") (pintype "bidirectional"))
    )
    (net (code "62") (name "Net-(J57-Pad3)") (class "Default")
      (node (ref "J57") (pin "3") (pinfunction "3_3") (pintype "bidirectional"))
      (node (ref "J58") (pin "2") (pinfunction "2_2") (pintype "bidirectional"))
    )
    (net (code "63") (name "Net-(J58-Pad3)") (class "Default")
      (node (ref "J58") (pin "3") (pinfunction "3_3") (pintype "bidirectional"))
      (node (ref "J59") (pin "2") (pinfunction "2_2") (pintype "bidirectional"))
    )
    (net (code "64") (name "Net-(J59-Pad3)") (class "Default")
      (node (ref "J59") (pin "3") (pinfunction "3_3") (pintype "bidirectional"))
      (node (ref "J60") (pin "2") (pinfunction "2_2") (pintype "bidirectional"))
    )
    (net (code "65") (name "Net-(J60-Pad3)") (class "Default")
      (node (ref "J60") (pin "3") (pinfunction "3_3") (pintype "bidirectional"))
      (node (ref "J61") (pin "2") (pinfunction "2_2") (pintype "bidirectional"))
    )
    (net (code "66") (name "Net-(J61-Pad3)") (class "Default")
      (node (ref "J61") (pin "3") (pinfunction "3_3") (pintype "bidirectional"))
      (node (ref "J62") (pin "2") (pinfunction "2_2") (pintype "bidirectional"))
    )
    (net (code "67") (name "Net-(J62-Pad3)") (class "Default")
      (node (ref "J62") (pin "3") (pinfunction "3_3") (pintype "bidirectional"))
      (node (ref "J63") (pin "2") (pinfunction "2_2") (pintype "bidirectional"))
    )
    (net (code "68") (name "Net-(J63-Pad3)") (class "Default")
      (node (ref "J63") (pin "3") (pinfunction "3_3") (pintype "bidirectional"))
      (node (ref "J64") (pin "2") (pinfunction "2_2") (pintype "bidirectional"))
    )
    (net (code "69") (name "Net-(J65-Pad3)") (class "Default")
      (node (ref "J65") (pin "3") (pinfunction "3_3") (pintype "bidirectional"))
      (node (ref "J66") (pin "2") (pinfunction "2_2") (pintype "bidirectional"))
    )
    (net (code "70") (name "Net-(J66-Pad3)") (class "Default")
      (node (ref "J66") (pin "3") (pinfunction "3_3") (pintype "bidirectional"))
      (node (ref "J67") (pin "2") (pinfunction "2_2") (pintype "bidirectional"))
    )
    (net (code "71") (name "Net-(J67-Pad3)") (class "Default")
      (node (ref "J67") (pin "3") (pinfunction "3_3") (pintype "bidirectional"))
      (node (ref "J68") (pin "2") (pinfunction "2_2") (pintype "bidirectional"))
    )
    (net (code "72") (name "Net-(J68-Pad3)") (class "Default")
      (node (ref "J68") (pin "3") (pinfunction "3_3") (pintype "bidirectional"))
      (node (ref "J69") (pin "2") (pinfunction "2_2") (pintype "bidirectional"))
    )
    (net (code "73") (name "Net-(J69-Pad3)") (class "Default")
      (node (ref "J69") (pin "3") (pinfunction "3_3") (pintype "bidirectional"))
      (node (ref "J70") (pin "2") (pinfunction "2_2") (pintype "bidirectional"))
    )
    (net (code "74") (name "Net-(J70-Pad3)") (class "Default")
      (node (ref "J70") (pin "3") (pinfunction "3_3") (pintype "bidirectional"))
      (node (ref "J71") (pin "2") (pinfunction "2_2") (pintype "bidirectional"))
    )
    (net (code "75") (name "Net-(J71-Pad3)") (class "Default")
      (node (ref "J71") (pin "3") (pinfunction "3_3") (pintype "bidirectional"))
      (node (ref "J72") (pin "2") (pinfunction "2_2") (pintype "bidirectional"))
    )
    (net (code "76") (name "Net-(J72-Pad3)") (class "Default")
      (node (ref "J72") (pin "3") (pinfunction "3_3") (pintype "bidirectional"))
      (node (ref "J73") (pin "2") (pinfunction "2_2") (pintype "bidirectional"))
    )
    (net (code "77") (name "Net-(J73-Pad3)") (class "Default")
      (node (ref "J73") (pin "3") (pinfunction "3_3") (pintype "bidirectional"))
      (node (ref "J74") (pin "2") (pinfunction "2_2") (pintype "bidirectional"))
    )
    (net (code "78") (name "Net-(J74-Pad3)") (class "Default")
      (node (ref "J74") (pin "3") (pinfunction "3_3") (pintype "bidirectional"))
      (node (ref "J75") (pin "2") (pinfunction "2_2") (pintype "bidirectional"))
    )
    (net (code "79") (name "Net-(J75-Pad3)") (class "Default")
      (node (ref "J75") (pin "3") (pinfunction "3_3") (pintype "bidirectional"))
      (node (ref "J76") (pin "2") (pinfunction "2_2") (pintype "bidirectional"))
    )
    (net (code "80") (name "Net-(J76-Pad3)") (class "Default")
      (node (ref "J76") (pin "3") (pinfunction "3_3") (pintype "bidirectional"))
      (node (ref "J77") (pin "2") (pinfunction "2_2") (pintype "bidirectional"))
    )
    (net (code "81") (name "Net-(J77-Pad3)") (class "Default")
      (node (ref "J77") (pin "3") (pinfunction "3_3") (pintype "bidirectional"))
      (node (ref "J78") (pin "2") (pinfunction "2_2") (pintype "bidirectional"))
    )
    (net (code "82") (name "Net-(J78-Pad3)") (class "Default")
      (node (ref "J78") (pin "3") (pinfunction "3_3") (pintype "bidirectional"))
      (node (ref "J79") (pin "2") (pinfunction "2_2") (pintype "bidirectional"))
    )
    (net (code "83") (name "Net-(J79-Pad3)") (class "Default")
      (node (ref "J79") (pin "3") (pinfunction "3_3") (pintype "bidirectional"))
      (node (ref "J80") (pin "2") (pinfunction "2_2") (pintype "bidirectional"))
    )
    (net (code "84") (name "Net-(J80-Pad3)") (class "Default")
      (node (ref "J80") (pin "3") (pinfunction "3_3") (pintype "bidirectional"))
      (node (ref "J81") (pin "2") (pinfunction "2_2") (pintype "bidirectional"))
    )
    (net (code "85") (name "Net-(J81-Pad3)") (class "Default")
      (node (ref "J81") (pin "3") (pinfunction "3_3") (pintype "bidirectional"))
      (node (ref "J82") (pin "2") (pinfunction "2_2") (pintype "bidirectional"))
    )
    (net (code "86") (name "Net-(J82-Pad3)") (class "Default")
      (node (ref "J82") (pin "3") (pinfunction "3_3") (pintype "bidirectional"))
      (node (ref "J83") (pin "2") (pinfunction "2_2") (pintype "bidirectional"))
    )
    (net (code "87") (name "Net-(J83-Pad3)") (class "Default")
      (node (ref "J83") (pin "3") (pinfunction "3_3") (pintype "bidirectional"))
      (node (ref "J84") (pin "2") (pinfunction "2_2") (pintype "bidirectional"))
    )
    (net (code "88") (name "Net-(J84-Pad3)") (class "Default")
      (node (ref "J84") (pin "3") (pinfunction "3_3") (pintype "bidirectional"))
      (node (ref "J85") (pin "2") (pinfunction "2_2") (pintype "bidirectional"))
    )
    (net (code "89") (name "Net-(J85-Pad3)") (class "Default")
      (node (ref "J85") (pin "3") (pinfunction "3_3") (pintype "bidirectional"))
      (node (ref "J86") (pin "2") (pinfunction "2_2") (pintype "bidirectional"))
    )
    (net (code "90") (name "Net-(J86-Pad3)") (class "Default")
      (node (ref "J86") (pin "3") (pinfunction "3_3") (pintype "bidirectional"))
      (node (ref "J87") (pin "2") (pinfunction "2_2") (pintype "bidirectional"))
    )
    (net (code "91") (name "Net-(J87-Pad3)") (class "Default")
      (node (ref "J87") (pin "3") (pinfunction "3_3") (pintype "bidirectional"))
      (node (ref "J88") (pin "2") (pinfunction "2_2") (pintype "bidirectional"))
    )
    (net (code "92") (name "Net-(J88-Pad3)") (class "Default")
      (node (ref "J88") (pin "3") (pinfunction "3_3") (pintype "bidirectional"))
      (node (ref "J89") (pin "2") (pinfunction "2_2") (pintype "bidirectional"))
    )
    (net (code "93") (name "Net-(J89-Pad3)") (class "Default")
      (node (ref "J89") (pin "3") (pinfunction "3_3") (pintype "bidirectional"))
      (node (ref "J90") (pin "2") (pinfunction "2_2") (pintype "bidirectional"))
    )
    (net (code "94") (name "Net-(J90-Pad3)") (class "Default")
      (node (ref "J90") (pin "3") (pinfunction "3_3") (pintype "bidirectional"))
      (node (ref "J91") (pin "2") (pinfunction "2_2") (pintype "bidirectional"))
    )
    (net (code "95") (name "Net-(J91-Pad3)") (class "Default")
      (node (ref "J91") (pin "3") (pinfunction "3_3") (pintype "bidirectional"))
      (node (ref "J92") (pin "2") (pinfunction "2_2") (pintype "bidirectional"))
    )
    (net (code "96") (name "Net-(J92-Pad3)") (class "Default")
      (node (ref "J92") (pin "3") (pinfunction "3_3") (pintype "bidirectional"))
      (node (ref "J93") (pin "2") (pinfunction "2_2") (pintype "bidirectional"))
    )
    (net (code "97") (name "Net-(J93-Pad3)") (class "Default")
      (node (ref "J93") (pin "3") (pinfunction "3_3") (pintype "bidirectional"))
      (node (ref "J94") (pin "2") (pinfunction "2_2") (pintype "bidirectional"))
    )
    (net (code "98") (name "Net-(J94-Pad3)") (class "Default")
      (node (ref "J94") (pin "3") (pinfunction "3_3") (pintype "bidirectional"))
      (node (ref "J95") (pin "2") (pinfunction "2_2") (pintype "bidirectional"))
    )
    (net (code "99") (name "Net-(J95-Pad3)") (class "Default")
      (node (ref "J95") (pin "3") (pinfunction "3_3") (pintype "bidirectional"))
      (node (ref "J96") (pin "2") (pinfunction "2_2") (pintype "bidirectional"))
    )
    (net (code "100") (name "Net-(J96-Pad3)") (class "Default")
      (node (ref "J96") (pin "3") (pinfunction "3_3") (pintype "bidirectional"))
      (node (ref "J97") (pin "2") (pinfunction "2_2") (pintype "bidirectional"))
    )
    (net (code "101") (name "Net-(J97-Pad3)") (class "Default")
      (node (ref "J97") (pin "3") (pinfunction "3_3") (pintype "bidirectional"))
      (node (ref "J98") (pin "2") (pinfunction "2_2") (pintype "bidirectional"))
    )
    (net (code "102") (name "Net-(J98-Pad3)") (class "Default")
      (node (ref "J98") (pin "3") (pinfunction "3_3") (pintype "bidirectional"))
      (node (ref "J99") (pin "2") (pinfunction "2_2") (pintype "bidirectional"))
    )
    (net (code "103") (name "Net-(J100-Pad2)") (class "Default")
      (node (ref "J100") (pin "2") (pinfunction "2_2") (pintype "bidirectional"))
      (node (ref "J99") (pin "3") (pinfunction "3_3") (pintype "bidirectional"))
    )
    (net (code "104") (name "Net-(J100-Pad3)") (class "Default")
      (node (ref "J100") (pin "3") (pinfunction "3_3") (pintype "bidirectional"))
      (node (ref "J101") (pin "2") (pinfunction "2_2") (pintype "bidirectional"))
    )
    (net (code "105") (name "Net-(J101-Pad3)") (class "Default")
      (node (ref "J101") (pin "3") (pinfunction "3_3") (pintype "bidirectional"))
      (node (ref "J102") (pin "2") (pinfunction "2_2") (pintype "bidirectional"))
    )
    (net (code "106") (name "Net-(J102-Pad3)") (class "Default")
      (node (ref "J102") (pin "3") (pinfunction "3_3") (pintype "bidirectional"))
      (node (ref "J103") (pin "2") (pinfunction "2_2") (pintype "bidirectional"))
    )
    (net (code "107") (name "Net-(J103-Pad3)") (class "Default")
      (node (ref "J103") (pin "3") (pinfunction "3_3") (pintype "bidirectional"))
      (node (ref "J104") (pin "2") (pinfunction "2_2") (pintype "bidirectional"))
    )
    (net (code "108") (name "Net-(J104-Pad3)") (class "Default")
      (node (ref "J104") (pin "3") (pinfunction "3_3") (pintype "bidirectional"))
      (node (ref "J105") (pin "2") (pinfunction "2_2") (pintype "bidirectional"))
    )
    (net (code "109") (name "Net-(J105-Pad3)") (class "Default")
      (node (ref "J105") (pin "3") (pinfunction "3_3") (pintype "bidirectional"))
      (node (ref "J106") (pin "2") (pinfunction "2_2") (pintype "bidirectional"))
    )
    (net (code "110") (name "Net-(J106-Pad3)") (class "Default")
      (node (ref "J106") (pin "3") (pinfunction "3_3") (pintype "bidirectional"))
      (node (ref "J107") (pin "2") (pinfunction "2_2") (pintype "bidirectional"))
    )
    (net (code "111") (name "Net-(J107-Pad3)") (class "Default")
      (node (ref "J107") (pin "3") (pinfunction "3_3") (pintype "bidirectional"))
      (node (ref "J108") (pin "2") (pinfunction "2_2") (pintype "bidirectional"))
    )
    (net (code "112") (name "Net-(J108-Pad3)") (class "Default")
      (node (ref "J108") (pin "3") (pinfunction "3_3") (pintype "bidirectional"))
      (node (ref "J109") (pin "2") (pinfunction "2_2") (pintype "bidirectional"))
    )
    (net (code "113") (name "Net-(J109-Pad3)") (class "Default")
      (node (ref "J109") (pin "3") (pinfunction "3_3") (pintype "bidirectional"))
      (node (ref "J110") (pin "2") (pinfunction "2_2") (pintype "bidirectional"))
    )
    (net (code "114") (name "Net-(J110-Pad3)") (class "Default")
      (node (ref "J110") (pin "3") (pinfunction "3_3") (pintype "bidirectional"))
      (node (ref "J111") (pin "2") (pinfunction "2_2") (pintype "bidirectional"))
    )
    (net (code "115") (name "Net-(J111-Pad3)") (class "Default")
      (node (ref "J111") (pin "3") (pinfunction "3_3") (pintype "bidirectional"))
      (node (ref "J112") (pin "2") (pinfunction "2_2") (pintype "bidirectional"))
    )
    (net (code "116") (name "Net-(J112-Pad3)") (class "Default")
      (node (ref "J112") (pin "3") (pinfunction "3_3") (pintype "bidirectional"))
      (node (ref "J113") (pin "2") (pinfunction "2_2") (pintype "bidirectional"))
    )
    (net (code "117") (name "Net-(J113-Pad3)") (class "Default")
      (node (ref "J113") (pin "3") (pinfunction "3_3") (pintype "bidirectional"))
      (node (ref "J114") (pin "2") (pinfunction "2_2") (pintype "bidirectional"))
    )
    (net (code "118") (name "Net-(J114-Pad3)") (class "Default")
      (node (ref "J114") (pin "3") (pinfunction "3_3") (pintype "bidirectional"))
      (node (ref "J115") (pin "2") (pinfunction "2_2") (pintype "bidirectional"))
    )
    (net (code "119") (name "Net-(J115-Pad3)") (class "Default")
      (node (ref "J115") (pin "3") (pinfunction "3_3") (pintype "bidirectional"))
      (node (ref "J116") (pin "2") (pinfunction "2_2") (pintype "bidirectional"))
    )
    (net (code "120") (name "Net-(J116-Pad3)") (class "Default")
      (node (ref "J116") (pin "3") (pinfunction "3_3") (pintype "bidirectional"))
      (node (ref "J117") (pin "2") (pinfunction "2_2") (pintype "bidirectional"))
    )
    (net (code "121") (name "Net-(J117-Pad3)") (class "Default")
      (node (ref "J117") (pin "3") (pinfunction "3_3") (pintype "bidirectional"))
      (node (ref "J118") (pin "2") (pinfunction "2_2") (pintype "bidirectional"))
    )
    (net (code "122") (name "Net-(J118-Pad3)") (class "Default")
      (node (ref "J118") (pin "3") (pinfunction "3_3") (pintype "bidirectional"))
      (node (ref "J119") (pin "2") (pinfunction "2_2") (pintype "bidirectional"))
    )
    (net (code "123") (name "Net-(J119-Pad3)") (class "Default")
      (node (ref "J119") (pin "3") (pinfunction "3_3") (pintype "bidirectional"))
      (node (ref "J120") (pin "2") (pinfunction "2_2") (pintype "bidirectional"))
    )
    (net (code "124") (name "Net-(J120-Pad3)") (class "Default")
      (node (ref "J120") (pin "3") (pinfunction "3_3") (pintype "bidirectional"))
      (node (ref "J121") (pin "2") (pinfunction "2_2") (pintype "bidirectional"))
    )
    (net (code "125") (name "Net-(J121-Pad3)") (class "Default")
      (node (ref "J121") (pin "3") (pinfunction "3_3") (pintype "bidirectional"))
      (node (ref "J122") (pin "2") (pinfunction "2_2") (pintype "bidirectional"))
    )
    (net (code "126") (name "Net-(J122-Pad3)") (class "Default")
      (node (ref "J122") (pin "3") (pinfunction "3_3") (pintype "bidirectional"))
      (node (ref "J123") (pin "2") (pinfunction "2_2") (pintype "bidirectional"))
    )
    (net (code "127") (name "Net-(J123-Pad3)") (class "Default")
      (node (ref "J123") (pin "3") (pinfunction "3_3") (pintype "bidirectional"))
      (node (ref "J124") (pin "2") (pinfunction "2_2") (pintype "bidirectional"))
    )
    (net (code "128") (name "Net-(J124-Pad3)") (class "Default")
      (node (ref "J124") (pin "3") (pinfunction "3_3") (pintype "bidirectional"))
      (node (ref "J125") (pin "2") (pinfunction "2_2") (pintype "bidirectional"))
    )
    (net (code "129") (name "Net-(J125-Pad3)") (class "Default")
      (node (ref "J125") (pin "3") (pinfunction "3_3") (pintype "bidirectional"))
      (node (ref "J126") (pin "2") (pinfunction "2_2") (pintype "bidirectional"))
    )
    (net (code "130") (name "Net-(J126-Pad3)") (class "Default")
      (node (ref "J126") (pin "3") (pinfunction "3_3") (pintype "bidirectional"))
      (node (ref "J127") (pin "2") (pinfunction "2_2") (pintype "bidirectional"))
    )
    (net (code "131") (name "Net-(J127-Pad3)") (class "Default")
      (node (ref "J127") (pin "3") (pinfunction "3_3") (pintype "bidirectional"))
      (node (ref "J128") (pin "2") (pinfunction "2_2") (pintype "bidirectional"))
    )
    (net (code "132") (name "Net-(J129-Pad3)") (class "Default")
      (node (ref "J129") (pin "3") (pinfunction "3_3") (pintype "bidirectional"))
      (node (ref "J130") (pin "2") (pinfunction "2_2") (pintype "bidirectional"))
    )
    (net (code "133") (name "Net-(J130-Pad3)") (class "Default")
      (node (ref "J130") (pin "3") (pinfunction "3_3") (pintype "bidirectional"))
      (node (ref "J131") (pin "2") (pinfunction "2_2") (pintype "bidirectional"))
    )
    (net (code "134") (name "Net-(J131-Pad3)") (class "Default")
      (node (ref "J131") (pin "3") (pinfunction "3_3") (pintype "bidirectional"))
      (node (ref "J132") (pin "2") (pinfunction "2_2") (pintype "bidirectional"))
    )
    (net (code "135") (name "Net-(J132-Pad3)") (class "Default")
      (node (ref "J132") (pin "3") (pinfunction "3_3") (pintype "bidirectional"))
      (node (ref "J133") (pin "2") (pinfunction "2_2") (pintype "bidirectional"))
    )
    (net (code "136") (name "Net-(J133-Pad3)") (class "Default")
      (node (ref "J133") (pin "3") (pinfunction "3_3") (pintype "bidirectional"))
      (node (ref "J134") (pin "2") (pinfunction "2_2") (pintype "bidirectional"))
    )
    (net (code "137") (name "Net-(J134-Pad3)") (class "Default")
      (node (ref "J134") (pin "3") (pinfunction "3_3") (pintype "bidirectional"))
      (node (ref "J135") (pin "2") (pinfunction "2_2") (pintype "bidirectional"))
    )
    (net (code "138") (name "Net-(J135-Pad3)") (class "Default")
      (node (ref "J135") (pin "3") (pinfunction "3_3") (pintype "bidirectional"))
      (node (ref "J136") (pin "2") (pinfunction "2_2") (pintype "bidirectional"))
    )
    (net (code "139") (name "Net-(J136-Pad3)") (class "Default")
      (node (ref "J136") (pin "3") (pinfunction "3_3") (pintype "bidirectional"))
      (node (ref "J137") (pin "2") (pinfunction "2_2") (pintype "bidirectional"))
    )
    (net (code "140") (name "Net-(J137-Pad3)") (class "Default")
      (node (ref "J137") (pin "3") (pinfunction "3_3") (pintype "bidirectional"))
      (node (ref "J138") (pin "2") (pinfunction "2_2") (pintype "bidirectional"))
    )
    (net (code "141") (name "Net-(J138-Pad3)") (class "Default")
      (node (ref "J138") (pin "3") (pinfunction "3_3") (pintype "bidirectional"))
      (node (ref "J139") (pin "2") (pinfunction "2_2") (pintype "bidirectional"))
    )
    (net (code "142") (name "Net-(J139-Pad3)") (class "Default")
      (node (ref "J139") (pin "3") (pinfunction "3_3") (pintype "bidirectional"))
      (node (ref "J140") (pin "2") (pinfunction "2_2") (pintype "bidirectional"))
    )
    (net (code "143") (name "Net-(J140-Pad3)") (class "Default")
      (node (ref "J140") (pin "3") (pinfunction "3_3") (pintype "bidirectional"))
      (node (ref "J141") (pin "2") (pinfunction "2_2") (pintype "bidirectional"))
    )
    (net (code "144") (name "Net-(J141-Pad3)") (class "Default")
      (node (ref "J141") (pin "3") (pinfunction "3_3") (pintype "bidirectional"))
      (node (ref "J142") (pin "2") (pinfunction "2_2") (pintype "bidirectional"))
    )
    (net (code "145") (name "Net-(J142-Pad3)") (class "Default")
      (node (ref "J142") (pin "3") (pinfunction "3_3") (pintype "bidirectional"))
      (node (ref "J143") (pin "2") (pinfunction "2_2") (pintype "bidirectional"))
    )
    (net (code "146") (name "Net-(J143-Pad3)") (class "Default")
      (node (ref "J143") (pin "3") (pinfunction "3_3") (pintype "bidirectional"))
      (node (ref "J144") (pin "2") (pinfunction "2_2") (pintype "bidirectional"))
    )
    (net (code "147") (name "Net-(J144-Pad3)") (class "Default")
      (node (ref "J144") (pin "3") (pinfunction "3_3") (pintype "bidirectional"))
      (node (ref "J145") (pin "2") (pinfunction "2_2") (pintype "bidirectional"))
    )
    (net (code "148") (name "Net-(J145-Pad3)") (class "Default")
      (node (ref "J145") (pin "3") (pinfunction "3_3") (pintype "bidirectional"))
      (node (ref "J146") (pin "2") (pinfunction "2_2") (pintype "bidirectional"))
    )
    (net (code "149") (name "Net-(J146-Pad3)") (class "Default")
      (node (ref "J146") (pin "3") (pinfunction "3_3") (pintype "bidirectional"))
      (node (ref "J147") (pin "2") (pinfunction "2_2") (pintype "bidirectional"))
    )
    (net (code "150") (name "Net-(J147-Pad3)") (class "Default")
      (node (ref "J147") (pin "3") (pinfunction "3_3") (pintype "bidirectional"))
      (node (ref "J148") (pin "2") (pinfunction "2_2") (pintype "bidirectional"))
    )
    (net (code "151") (name "Net-(J148-Pad3)") (class "Default")
      (node (ref "J148") (pin "3") (pinfunction "3_3") (pintype "bidirectional"))
      (node (ref "J149") (pin "2") (pinfunction "2_2") (pintype "bidirectional"))
    )
    (net (code "152") (name "Net-(J149-Pad3)") (class "Default")
      (node (ref "J149") (pin "3") (pinfunction "3_3") (pintype "bidirectional"))
      (node (ref "J150") (pin "2") (pinfunction "2_2") (pintype "bidirectional"))
    )
    (net (code "153") (name "Net-(J150-Pad3)") (class "Default")
      (node (ref "J150") (pin "3") (pinfunction "3_3") (pintype "bidirectional"))
      (node (ref "J151") (pin "2") (pinfunction "2_2") (pintype "bidirectional"))
    )
    (net (code "154") (name "Net-(J151-Pad3)") (class "Default")
      (node (ref "J151") (pin "3") (pinfunction "3_3") (pintype "bidirectional"))
      (node (ref "J152") (pin "2") (pinfunction "2_2") (pintype "bidirectional"))
    )
    (net (code "155") (name "Net-(J152-Pad3)") (class "Default")
      (node (ref "J152") (pin "3") (pinfunction "3_3") (pintype "bidirectional"))
      (node (ref "J153") (pin "2") (pinfunction "2_2") (pintype "bidirectional"))
    )
    (net (code "156") (name "Net-(J153-Pad3)") (class "Default")
      (node (ref "J153") (pin "3") (pinfunction "3_3") (pintype "bidirectional"))
      (node (ref "J154") (pin "2") (pinfunction "2_2") (pintype "bidirectional"))
    )
    (net (code "157") (name "Net-(J154-Pad3)") (class "Default")
      (node (ref "J154") (pin "3") (pinfunction "3_3") (pintype "bidirectional"))
      (node (ref "J155") (pin "2") (pinfunction "2_2") (pintype "bidirectional"))
    )
    (net (code "158") (name "Net-(J155-Pad3)") (class "Default")
      (node (ref "J155") (pin "3") (pinfunction "3_3") (pintype "bidirectional"))
      (node (ref "J156") (pin "2") (pinfunction "2_2") (pintype "bidirectional"))
    )
    (net (code "159") (name "Net-(J156-Pad3)") (class "Default")
      (node (ref "J156") (pin "3") (pinfunction "3_3") (pintype "bidirectional"))
      (node (ref "J157") (pin "2") (pinfunction "2_2") (pintype "bidirectional"))
    )
    (net (code "160") (name "Net-(J157-Pad3)") (class "Default")
      (node (ref "J157") (pin "3") (pinfunction "3_3") (pintype "bidirectional"))
      (node (ref "J158") (pin "2") (pinfunction "2_2") (pintype "bidirectional"))
    )
    (net (code "161") (name "Net-(J158-Pad3)") (class "Default")
      (node (ref "J158") (pin "3") (pinfunction "3_3") (pintype "bidirectional"))
      (node (ref "J159") (pin "2") (pinfunction "2_2") (pintype "bidirectional"))
    )
    (net (code "162") (name "Net-(J159-Pad3)") (class "Default")
      (node (ref "J159") (pin "3") (pinfunction "3_3") (pintype "bidirectional"))
      (node (ref "J160") (pin "2") (pinfunction "2_2") (pintype "bidirectional"))
    )
    (net (code "163") (name "Net-(J160-Pad3)") (class "Default")
      (node (ref "J160") (pin "3") (pinfunction "3_3") (pintype "bidirectional"))
      (node (ref "J161") (pin "2") (pinfunction "2_2") (pintype "bidirectional"))
    )
    (net (code "164") (name "Net-(J161-Pad3)") (class "Default")
      (node (ref "J161") (pin "3") (pinfunction "3_3") (pintype "bidirectional"))
      (node (ref "J162") (pin "2") (pinfunction "2_2") (pintype "bidirectional"))
    )
    (net (code "165") (name "Net-(J162-Pad3)") (class "Default")
      (node (ref "J162") (pin "3") (pinfunction "3_3") (pintype "bidirectional"))
      (node (ref "J163") (pin "2") (pinfunction "2_2") (pintype "bidirectional"))
    )
    (net (code "166") (name "Net-(J163-Pad3)") (class "Default")
      (node (ref "J163") (pin "3") (pinfunction "3_3") (pintype "bidirectional"))
      (node (ref "J164") (pin "2") (pinfunction "2_2") (pintype "bidirectional"))
    )
    (net (code "167") (name "Net-(J164-Pad3)") (class "Default")
      (node (ref "J164") (pin "3") (pinfunction "3_3") (pintype "bidirectional"))
      (node (ref "J165") (pin "2") (pinfunction "2_2") (pintype "bidirectional"))
    )
    (net (code "168") (name "Net-(J165-Pad3)") (class "Default")
      (node (ref "J165") (pin "3") (pinfunction "3_3") (pintype "bidirectional"))
      (node (ref "J166") (pin "2") (pinfunction "2_2") (pintype "bidirectional"))
    )
    (net (code "169") (name "Net-(J166-Pad3)") (class "Default")
      (node (ref "J166") (pin "3") (pinfunction "3_3") (pintype "bidirectional"))
      (node (ref "J167") (pin "2") (pinfunction "2_2") (pintype "bidirectional"))
    )
    (net (code "170") (name "Net-(J167-Pad3)") (class "Default")
      (node (ref "J167") (pin "3") (pinfunction "3_3") (pintype "bidirectional"))
      (node (ref "J168") (pin "2") (pinfunction "2_2") (pintype "bidirectional"))
    )
    (net (code "171") (name "Net-(J168-Pad3)") (class "Default")
      (node (ref "J168") (pin "3") (pinfunction "3_3") (pintype "bidirectional"))
      (node (ref "J169") (pin "2") (pinfunction "2_2") (pintype "bidirectional"))
    )
    (net (code "172") (name "Net-(J169-Pad3)") (class "Default")
      (node (ref "J169") (pin "3") (pinfunction "3_3") (pintype "bidirectional"))
      (node (ref "J170") (pin "2") (pinfunction "2_2") (pintype "bidirectional"))
    )
    (net (code "173") (name "Net-(J170-Pad3)") (class "Default")
      (node (ref "J170") (pin "3") (pinfunction "3_3") (pintype "bidirectional"))
      (node (ref "J171") (pin "2") (pinfunction "2_2") (pintype "bidirectional"))
    )
    (net (code "174") (name "Net-(J171-Pad3)") (class "Default")
      (node (ref "J171") (pin "3") (pinfunction "3_3") (pintype "bidirectional"))
      (node (ref "J172") (pin "2") (pinfunction "2_2") (pintype "bidirectional"))
    )
    (net (code "175") (name "Net-(J172-Pad3)") (class "Default")
      (node (ref "J172") (pin "3") (pinfunction "3_3") (pintype "bidirectional"))
      (node (ref "J173") (pin "2") (pinfunction "2_2") (pintype "bidirectional"))
    )
    (net (code "176") (name "Net-(J173-Pad3)") (class "Default")
      (node (ref "J173") (pin "3") (pinfunction "3_3") (pintype "bidirectional"))
      (node (ref "J174") (pin "2") (pinfunction "2_2") (pintype "bidirectional"))
    )
    (net (code "177") (name "Net-(J174-Pad3)") (class "Default")
      (node (ref "J174") (pin "3") (pinfunction "3_3") (pintype "bidirectional"))
      (node (ref "J175") (pin "2") (pinfunction "2_2") (pintype "bidirectional"))
    )
    (net (code "178") (name "Net-(J175-Pad3)") (class "Default")
      (node (ref "J175") (pin "3") (pinfunction "3_3") (pintype "bidirectional"))
      (node (ref "J176") (pin "2") (pinfunction "2_2") (pintype "bidirectional"))
    )
    (net (code "179") (name "Net-(J176-Pad3)") (class "Default")
      (node (ref "J176") (pin "3") (pinfunction "3_3") (pintype "bidirectional"))
      (node (ref "J177") (pin "2") (pinfunction "2_2") (pintype "bidirectional"))
    )
    (net (code "180") (name "Net-(J177-Pad3)") (class "Default")
      (node (ref "J177") (pin "3") (pinfunction "3_3") (pintype "bidirectional"))
      (node (ref "J178") (pin "2") (pinfunction "2_2") (pintype "bidirectional"))
    )
    (net (code "181") (name "Net-(J178-Pad3)") (class "Default")
      (node (ref "J178") (pin "3") (pinfunction "3_3") (pintype "bidirectional"))
      (node (ref "J179") (pin "2") (pinfunction "2_2") (pintype "bidirectional"))
    )
    (net (code "182") (name "Net-(J179-Pad3)") (class "Default")
      (node (ref "J179") (pin "3") (pinfunction "3_3") (pintype "bidirectional"))
      (node (ref "J180") (pin "2") (pinfunction "2_2") (pintype "bidirectional"))
    )
    (net (code "183") (name "Net-(J180-Pad3)") (class "Default")
      (node (ref "J180") (pin "3") (pinfunction "3_3") (pintype "bidirectional"))
      (node (ref "J181") (pin "2") (pinfunction "2_2") (pintype "bidirectional"))
    )
    (net (code "184") (name "Net-(J181-Pad3)") (class "Default")
      (node (ref "J181") (pin "3") (pinfunction "3_3") (pintype "bidirectional"))
      (node (ref "J182") (pin "2") (pinfunction "2_2") (pintype "bidirectional"))
    )
    (net (code "185") (name "Net-(J182-Pad3)") (class "Default")
      (node (ref "J182") (pin "3") (pinfunction "3_3") (pintype "bidirectional"))
      (node (ref "J183") (pin "2") (pinfunction "2_2") (pintype "bidirectional"))
    )
    (net (code "186") (name "Net-(J183-Pad3)") (class "Default")
      (node (ref "J183") (pin "3") (pinfunction "3_3") (pintype "bidirectional"))
      (node (ref "J184") (pin "2") (pinfunction "2_2") (pintype "bidirectional"))
    )
    (net (code "187") (name "Net-(J184-Pad3)") (class "Default")
      (node (ref "J184") (pin "3") (pinfunction "3_3") (pintype "bidirectional"))
      (node (ref "J185") (pin "2") (pinfunction "2_2") (pintype "bidirectional"))
    )
    (net (code "188") (name "Net-(J185-Pad3)") (class "Default")
      (node (ref "J185") (pin "3") (pinfunction "3_3") (pintype "bidirectional"))
      (node (ref "J186") (pin "2") (pinfunction "2_2") (pintype "bidirectional"))
    )
    (net (code "189") (name "Net-(J186-Pad3)") (class "Default")
      (node (ref "J186") (pin "3") (pinfunction "3_3") (pintype "bidirectional"))
      (node (ref "J187") (pin "2") (pinfunction "2_2") (pintype "bidirectional"))
    )
    (net (code "190") (name "Net-(J187-Pad3)") (class "Default")
      (node (ref "J187") (pin "3") (pinfunction "3_3") (pintype "bidirectional"))
      (node (ref "J188") (pin "2") (pinfunction "2_2") (pintype "bidirectional"))
    )
    (net (code "191") (name "Net-(J188-Pad3)") (class "Default")
      (node (ref "J188") (pin "3") (pinfunction "3_3") (pintype "bidirectional"))
      (node (ref "J189") (pin "2") (pinfunction "2_2") (pintype "bidirectional"))
    )
    (net (code "192") (name "Net-(J189-Pad3)") (class "Default")
      (node (ref "J189") (pin "3") (pinfunction "3_3") (pintype "bidirectional"))
      (node (ref "J190") (pin "2") (pinfunction "2_2") (pintype "bidirectional"))
    )
    (net (code "193") (name "Net-(J190-Pad3)") (class "Default")
      (node (ref "J190") (pin "3") (pinfunction "3_3") (pintype "bidirectional"))
      (node (ref "J191") (pin "2") (pinfunction "2_2") (pintype "bidirectional"))
    )
    (net (code "194") (name "Net-(J191-Pad3)") (class "Default")
      (node (ref "J191") (pin "3") (pinfunction "3_3") (pintype "bidirectional"))
      (node (ref "J192") (pin "2") (pinfunction "2_2") (pintype "bidirectional"))
    )
    (net (code "195") (name "Net-(J193-Pad3)") (class "Default")
      (node (ref "J193") (pin "3") (pinfunction "3_3") (pintype "bidirectional"))
      (node (ref "J194") (pin "2") (pinfunction "2_2") (pintype "bidirectional"))
    )
    (net (code "196") (name "Net-(J194-Pad3)") (class "Default")
      (node (ref "J194") (pin "3") (pinfunction "3_3") (pintype "bidirectional"))
      (node (ref "J195") (pin "2") (pinfunction "2_2") (pintype "bidirectional"))
    )
    (net (code "197") (name "Net-(J195-Pad3)") (class "Default")
      (node (ref "J195") (pin "3") (pinfunction "3_3") (pintype "bidirectional"))
      (node (ref "J196") (pin "2") (pinfunction "2_2") (pintype "bidirectional"))
    )
    (net (code "198") (name "Net-(J196-Pad3)") (class "Default")
      (node (ref "J196") (pin "3") (pinfunction "3_3") (pintype "bidirectional"))
      (node (ref "J197") (pin "2") (pinfunction "2_2") (pintype "bidirectional"))
    )
    (net (code "199") (name "Net-(J197-Pad3)") (class "Default")
      (node (ref "J197") (pin "3") (pinfunction "3_3") (pintype "bidirectional"))
      (node (ref "J198") (pin "2") (pinfunction "2_2") (pintype "bidirectional"))
    )
    (net (code "200") (name "Net-(J198-Pad3)") (class "Default")
      (node (ref "J198") (pin "3") (pinfunction "3_3") (pintype "bidirectional"))
      (node (ref "J199") (pin "2") (pinfunction "2_2") (pintype "bidirectional"))
    )
    (net (code "201") (name "Net-(J199-Pad3)") (class "Default")
      (node (ref "J199") (pin "3") (pinfunction "3_3") (pintype "bidirectional"))
      (node (ref "J200") (pin "2") (pinfunction "2_2") (pintype "bidirectional"))
    )
    (net (code "202") (name "Net-(J200-Pad3)") (class "Default")
      (node (ref "J200") (pin "3") (pinfunction "3_3") (pintype "bidirectional"))
      (node (ref "J201") (pin "2") (pinfunction "2_2") (pintype "bidirectional"))
    )
    (net (code "203") (name "Net-(J201-Pad3)") (class "Default")
      (node (ref "J201") (pin "3") (pinfunction "3_3") (pintype "bidirectional"))
      (node (ref "J202") (pin "2") (pinfunction "2_2") (pintype "bidirectional"))
    )
    (net (code "204") (name "Net-(J202-Pad3)") (class "Default")
      (node (ref "J202") (pin "3") (pinfunction "3_3") (pintype "bidirectional"))
      (node (ref "J203") (pin "2") (pinfunction "2_2") (pintype "bidirectional"))
    )
    (net (code "205") (name "Net-(J203-Pad3)") (class "Default")
      (node (ref "J203") (pin "3") (pinfunction "3_3") (pintype "bidirectional"))
      (node (ref "J204") (pin "2") (pinfunction "2_2") (pintype "bidirectional"))
    )
    (net (code "206") (name "Net-(J204-Pad3)") (class "Default")
      (node (ref "J204") (pin "3") (pinfunction "3_3") (pintype "bidirectional"))
      (node (ref "J205") (pin "2") (pinfunction "2_2") (pintype "bidirectional"))
    )
    (net (code "207") (name "Net-(J205-Pad3)") (class "Default")
      (node (ref "J205") (pin "3") (pinfunction "3_3") (pintype "bidirectional"))
      (node (ref "J206") (pin "2") (pinfunction "2_2") (pintype "bidirectional"))
    )
    (net (code "208") (name "Net-(J206-Pad3)") (class "Default")
      (node (ref "J206") (pin "3") (pinfunction "3_3") (pintype "bidirectional"))
      (node (ref "J207") (pin "2") (pinfunction "2_2") (pintype "bidirectional"))
    )
    (net (code "209") (name "Net-(J207-Pad3)") (class "Default")
      (node (ref "J207") (pin "3") (pinfunction "3_3") (pintype "bidirectional"))
      (node (ref "J208") (pin "2") (pinfunction "2_2") (pintype "bidirectional"))
    )
    (net (code "210") (name "Net-(J208-Pad3)") (class "Default")
      (node (ref "J208") (pin "3") (pinfunction "3_3") (pintype "bidirectional"))
      (node (ref "J209") (pin "2") (pinfunction "2_2") (pintype "bidirectional"))
    )
    (net (code "211") (name "Net-(J209-Pad3)") (class "Default")
      (node (ref "J209") (pin "3") (pinfunction "3_3") (pintype "bidirectional"))
      (node (ref "J210") (pin "2") (pinfunction "2_2") (pintype "bidirectional"))
    )
    (net (code "212") (name "Net-(J210-Pad3)") (class "Default")
      (node (ref "J210") (pin "3") (pinfunction "3_3") (pintype "bidirectional"))
      (node (ref "J211") (pin "2") (pinfunction "2_2") (pintype "bidirectional"))
    )
    (net (code "213") (name "Net-(J211-Pad3)") (class "Default")
      (node (ref "J211") (pin "3") (pinfunction "3_3") (pintype "bidirectional"))
      (node (ref "J212") (pin "2") (pinfunction "2_2") (pintype "bidirectional"))
    )
    (net (code "214") (name "Net-(J212-Pad3)") (class "Default")
      (node (ref "J212") (pin "3") (pinfunction "3_3") (pintype "bidirectional"))
      (node (ref "J213") (pin "2") (pinfunction "2_2") (pintype "bidirectional"))
    )
    (net (code "215") (name "Net-(J213-Pad3)") (class "Default")
      (node (ref "J213") (pin "3") (pinfunction "3_3") (pintype "bidirectional"))
      (node (ref "J214") (pin "2") (pinfunction "2_2") (pintype "bidirectional"))
    )
    (net (code "216") (name "Net-(J214-Pad3)") (class "Default")
      (node (ref "J214") (pin "3") (pinfunction "3_3") (pintype "bidirectional"))
      (node (ref "J215") (pin "2") (pinfunction "2_2") (pintype "bidirectional"))
    )
    (net (code "217") (name "Net-(J215-Pad3)") (class "Default")
      (node (ref "J215") (pin "3") (pinfunction "3_3") (pintype "bidirectional"))
      (node (ref "J216") (pin "2") (pinfunction "2_2") (pintype "bidirectional"))
    )
    (net (code "218") (name "Net-(J216-Pad3)") (class "Default")
      (node (ref "J216") (pin "3") (pinfunction "3_3") (pintype "bidirectional"))
      (node (ref "J217") (pin "2") (pinfunction "2_2") (pintype "bidirectional"))
    )
    (net (code "219") (name "Net-(J217-Pad3)") (class "Default")
      (node (ref "J217") (pin "3") (pinfunction "3_3") (pintype "bidirectional"))
      (node (ref "J218") (pin "2") (pinfunction "2_2") (pintype "bidirectional"))
    )
    (net (code "220") (name "Net-(J218-Pad3)") (class "Default")
      (node (ref "J218") (pin "3") (pinfunction "3_3") (pintype "bidirectional"))
      (node (ref "J219") (pin "2") (pinfunction "2_2") (pintype "bidirectional"))
    )
    (net (code "221") (name "Net-(J219-Pad3)") (class "Default")
      (node (ref "J219") (pin "3") (pinfunction "3_3") (pintype "bidirectional"))
      (node (ref "J220") (pin "2") (pinfunction "2_2") (pintype "bidirectional"))
    )
    (net (code "222") (name "Net-(J220-Pad3)") (class "Default")
      (node (ref "J220") (pin "3") (pinfunction "3_3") (pintype "bidirectional"))
      (node (ref "J221") (pin "2") (pinfunction "2_2") (pintype "bidirectional"))
    )
    (net (code "223") (name "Net-(J221-Pad3)") (class "Default")
      (node (ref "J221") (pin "3") (pinfunction "3_3") (pintype "bidirectional"))
      (node (ref "J222") (pin "2") (pinfunction "2_2") (pintype "bidirectional"))
    )
    (net (code "224") (name "Net-(J222-Pad3)") (class "Default")
      (node (ref "J222") (pin "3") (pinfunction "3_3") (pintype "bidirectional"))
      (node (ref "J223") (pin "2") (pinfunction "2_2") (pintype "bidirectional"))
    )
    (net (code "225") (name "Net-(J223-Pad3)") (class "Default")
      (node (ref "J223") (pin "3") (pinfunction "3_3") (pintype "bidirectional"))
      (node (ref "J224") (pin "2") (pinfunction "2_2") (pintype "bidirectional"))
    )
    (net (code "226") (name "Net-(J224-Pad3)") (class "Default")
      (node (ref "J224") (pin "3") (pinfunction "3_3") (pintype "bidirectional"))
      (node (ref "J225") (pin "2") (pinfunction "2_2") (pintype "bidirectional"))
    )
    (net (code "227") (name "Net-(J225-Pad3)") (class "Default")
      (node (ref "J225") (pin "3") (pinfunction "3_3") (pintype "bidirectional"))
      (node (ref "J226") (pin "2") (pinfunction "2_2") (pintype "bidirectional"))
    )
    (net (code "228") (name "Net-(J226-Pad3)") (class "Default")
      (node (ref "J226") (pin "3") (pinfunction "3_3") (pintype "bidirectional"))
      (node (ref "J227") (pin "2") (pinfunction "2_2") (pintype "bidirectional"))
    )
    (net (code "229") (name "Net-(J227-Pad3)") (class "Default")
      (node (ref "J227") (pin "3") (pinfunction "3_3") (pintype "bidirectional"))
      (node (ref "J228") (pin "2") (pinfunction "2_2") (pintype "bidirectional"))
    )
    (net (code "230") (name "Net-(J228-Pad3)") (class "Default")
      (node (ref "J228") (pin "3") (pinfunction "3_3") (pintype "bidirectional"))
      (node (ref "J229") (pin "2") (pinfunction "2_2") (pintype "bidirectional"))
    )
    (net (code "231") (name "Net-(J229-Pad3)") (class "Default")
      (node (ref "J229") (pin "3") (pinfunction "3_3") (pintype "bidirectional"))
      (node (ref "J230") (pin "2") (pinfunction "2_2") (pintype "bidirectional"))
    )
    (net (code "232") (name "Net-(J230-Pad3)") (class "Default")
      (node (ref "J230") (pin "3") (pinfunction "3_3") (pintype "bidirectional"))
      (node (ref "J231") (pin "2") (pinfunction "2_2") (pintype "bidirectional"))
    )
    (net (code "233") (name "Net-(J231-Pad3)") (class "Default")
      (node (ref "J231") (pin "3") (pinfunction "3_3") (pintype "bidirectional"))
      (node (ref "J232") (pin "2") (pinfunction "2_2") (pintype "bidirectional"))
    )
    (net (code "234") (name "Net-(J232-Pad3)") (class "Default")
      (node (ref "J232") (pin "3") (pinfunction "3_3") (pintype "bidirectional"))
      (node (ref "J233") (pin "2") (pinfunction "2_2") (pintype "bidirectional"))
    )
    (net (code "235") (name "Net-(J233-Pad3)") (class "Default")
      (node (ref "J233") (pin "3") (pinfunction "3_3") (pintype "bidirectional"))
      (node (ref "J234") (pin "2") (pinfunction "2_2") (pintype "bidirectional"))
    )
    (net (code "236") (name "Net-(J234-Pad3)") (class "Default")
      (node (ref "J234") (pin "3") (pinfunction "3_3") (pintype "bidirectional"))
      (node (ref "J235") (pin "2") (pinfunction "2_2") (pintype "bidirectional"))
    )
    (net (code "237") (name "Net-(J235-Pad3)") (class "Default")
      (node (ref "J235") (pin "3") (pinfunction "3_3") (pintype "bidirectional"))
      (node (ref "J236") (pin "2") (pinfunction "2_2") (pintype "bidirectional"))
    )
    (net (code "238") (name "Net-(J236-Pad3)") (class "Default")
      (node (ref "J236") (pin "3") (pinfunction "3_3") (pintype "bidirectional"))
      (node (ref "J237") (pin "2") (pinfunction "2_2") (pintype "bidirectional"))
    )
    (net (code "239") (name "Net-(J237-Pad3)") (class "Default")
      (node (ref "J237") (pin "3") (pinfunction "3_3") (pintype "bidirectional"))
      (node (ref "J238") (pin "2") (pinfunction "2_2") (pintype "bidirectional"))
    )
    (net (code "240") (name "Net-(J238-Pad3)") (class "Default")
      (node (ref "J238") (pin "3") (pinfunction "3_3") (pintype "bidirectional"))
      (node (ref "J239") (pin "2") (pinfunction "2_2") (pintype "bidirectional"))
    )
    (net (code "241") (name "Net-(J239-Pad3)") (class "Default")
      (node (ref "J239") (pin "3") (pinfunction "3_3") (pintype "bidirectional"))
      (node (ref "J240") (pin "2") (pinfunction "2_2") (pintype "bidirectional"))
    )
    (net (code "242") (name "Net-(J240-Pad3)") (class "Default")
      (node (ref "J240") (pin "3") (pinfunction "3_3") (pintype "bidirectional"))
      (node (ref "J241") (pin "2") (pinfunction "2_2") (pintype "bidirectional"))
    )
    (net (code "243") (name "Net-(J241-Pad3)") (class "Default")
      (node (ref "J241") (pin "3") (pinfunction "3_3") (pintype "bidirectional"))
      (node (ref "J242") (pin "2") (pinfunction "2_2") (pintype "bidirectional"))
    )
    (net (code "244") (name "Net-(J242-Pad3)") (class "Default")
      (node (ref "J242") (pin "3") (pinfunction "3_3") (pintype "bidirectional"))
      (node (ref "J243") (pin "2") (pinfunction "2_2") (pintype "bidirectional"))
    )
    (net (code "245") (name "Net-(J243-Pad3)") (class "Default")
      (node (ref "J243") (pin "3") (pinfunction "3_3") (pintype "bidirectional"))
      (node (ref "J244") (pin "2") (pinfunction "2_2") (pintype "bidirectional"))
    )
    (net (code "246") (name "Net-(J244-Pad3)") (class "Default")
      (node (ref "J244") (pin "3") (pinfunction "3_3") (pintype "bidirectional"))
      (node (ref "J245") (pin "2") (pinfunction "2_2") (pintype "bidirectional"))
    )
    (net (code "247") (name "Net-(J245-Pad3)") (class "Default")
      (node (ref "J245") (pin "3") (pinfunction "3_3") (pintype "bidirectional"))
      (node (ref "J246") (pin "2") (pinfunction "2_2") (pintype "bidirectional"))
    )
    (net (code "248") (name "Net-(J246-Pad3)") (class "Default")
      (node (ref "J246") (pin "3") (pinfunction "3_3") (pintype "bidirectional"))
      (node (ref "J247") (pin "2") (pinfunction "2_2") (pintype "bidirectional"))
    )
    (net (code "249") (name "Net-(J247-Pad3)") (class "Default")
      (node (ref "J247") (pin "3") (pinfunction "3_3") (pintype "bidirectional"))
      (node (ref "J248") (pin "2") (pinfunction "2_2") (pintype "bidirectional"))
    )
    (net (code "250") (name "Net-(J248-Pad3)") (class "Default")
      (node (ref "J248") (pin "3") (pinfunction "3_3") (pintype "bidirectional"))
      (node (ref "J249") (pin "2") (pinfunction "2_2") (pintype "bidirectional"))
    )
    (net (code "251") (name "Net-(J249-Pad3)") (class "Default")
      (node (ref "J249") (pin "3") (pinfunction "3_3") (pintype "bidirectional"))
      (node (ref "J250") (pin "2") (pinfunction "2_2") (pintype "bidirectional"))
    )
    (net (code "252") (name "Net-(J250-Pad3)") (class "Default")
      (node (ref "J250") (pin "3") (pinfunction "3_3") (pintype "bidirectional"))
      (node (ref "J251") (pin "2") (pinfunction "2_2") (pintype "bidirectional"))
    )
    (net (code "253") (name "Net-(J251-Pad3)") (class "Default")
      (node (ref "J251") (pin "3") (pinfunction "3_3") (pintype "bidirectional"))
      (node (ref "J252") (pin "2") (pinfunction "2_2") (pintype "bidirectional"))
    )
    (net (code "254") (name "Net-(J252-Pad3)") (class "Default")
      (node (ref "J252") (pin "3") (pinfunction "3_3") (pintype "bidirectional"))
      (node (ref "J253") (pin "2") (pinfunction "2_2") (pintype "bidirectional"))
    )
    (net (code "255") (name "Net-(J253-Pad3)") (class "Default")
      (node (ref "J253") (pin "3") (pinfunction "3_3") (pintype "bidirectional"))
      (node (ref "J254") (pin "2") (pinfunction "2_2") (pintype "bidirectional"))
    )
    (net (code "256") (name "Net-(J254-Pad3)") (class "Default")
      (node (ref "J254") (pin "3") (pinfunction "3_3") (pintype "bidirectional"))
      (node (ref "J255") (pin "2") (pinfunction "2_2") (pintype "bidirectional"))
    )
    (net (code "257") (name "Net-(J255-Pad3)") (class "Default")
      (node (ref "J255") (pin "3") (pinfunction "3_3") (pintype "bidirectional"))
      (node (ref "J256") (pin "2") (pinfunction "2_2") (pintype "bidirectional"))
    )
    (net (code "258") (name "V+") (class "Default")
      (node (ref "C1") (pin "+") (pinfunction "1_+") (pintype "bidirectional"))
      (node (ref "C2") (pin "+") (pinfunction "1_+") (pintype "bidirectional"))
      (node (ref "C3") (pin "+") (pinfunction "1_+") (pintype "bidirectional"))
      (node (ref "C4") (pin "+") (pinfunction "1_+") (pintype "bidirectional"))
      (node (ref "C5") (pin "2") (pinfunction "2_2") (pintype "bidirectional"))
      (node (ref "C6") (pin "2") (pinfunction "2_2") (pintype "bidirectional"))
      (node (ref "C7") (pin "2") (pinfunction "2_2") (pintype "bidirectional"))
      (node (ref "C8") (pin "2") (pinfunction "2_2") (pintype "bidirectional"))
      (node (ref "DC") (pin "+") (pinfunction "+_+") (pintype "bidirectional"))
      (node (ref "DC") (pin "P$19") (pinfunction "+_P$19") (pintype "bidirectional"))
      (node (ref "DC") (pin "P$20") (pinfunction "+_P$20") (pintype "bidirectional"))
      (node (ref "DC") (pin "P$21") (pinfunction "+_P$21") (pintype "bidirectional"))
      (node (ref "DC") (pin "P$22") (pinfunction "+_P$22") (pintype "bidirectional"))
      (node (ref "DC") (pin "P$23") (pinfunction "+_P$23") (pintype "bidirectional"))
      (node (ref "DC") (pin "P$24") (pinfunction "+_P$24") (pintype "bidirectional"))
      (node (ref "DC") (pin "P$25") (pinfunction "+_P$25") (pintype "bidirectional"))
      (node (ref "DC") (pin "P$26") (pinfunction "+_P$26") (pintype "bidirectional"))
      (node (ref "DC") (pin "P$27") (pinfunction "+_P$27") (pintype "bidirectional"))
      (node (ref "DC") (pin "P$28") (pinfunction "+_P$28") (pintype "bidirectional"))
      (node (ref "DC") (pin "P$29") (pinfunction "+_P$29") (pintype "bidirectional"))
      (node (ref "DC") (pin "P$30") (pinfunction "+_P$30") (pintype "bidirectional"))
      (node (ref "DC") (pin "P$31") (pinfunction "+_P$31") (pintype "bidirectional"))
      (node (ref "DC") (pin "P$32") (pinfunction "+_P$32") (pintype "bidirectional"))
      (node (ref "DC") (pin "P$33") (pinfunction "+_P$33") (pintype "bidirectional"))
      (node (ref "DC") (pin "P$34") (pinfunction "+_P$34") (pintype "bidirectional"))
      (node (ref "DC") (pin "P$35") (pinfunction "+_P$35") (pintype "bidirectional"))
      (node (ref "DC") (pin "P$36") (pinfunction "+_P$36") (pintype "bidirectional"))
      (node (ref "DC") (pin "P$37") (pinfunction "+_P$37") (pintype "bidirectional"))
      (node (ref "DC") (pin "P$38") (pinfunction "+_P$38") (pintype "bidirectional"))
      (node (ref "DC") (pin "P$39") (pinfunction "+_P$39") (pintype "bidirectional"))
      (node (ref "J1") (pin "1") (pinfunction "1_1") (pintype "bidirectional"))
      (node (ref "J10") (pin "1") (pinfunction "1_1") (pintype "bidirectional"))
      (node (ref "J100") (pin "1") (pinfunction "1_1") (pintype "bidirectional"))
      (node (ref "J101") (pin "1") (pinfunction "1_1") (pintype "bidirectional"))
      (node (ref "J102") (pin "1") (pinfunction "1_1") (pintype "bidirectional"))
      (node (ref "J103") (pin "1") (pinfunction "1_1") (pintype "bidirectional"))
      (node (ref "J104") (pin "1") (pinfunction "1_1") (pintype "bidirectional"))
      (node (ref "J105") (pin "1") (pinfunction "1_1") (pintype "bidirectional"))
      (node (ref "J106") (pin "1") (pinfunction "1_1") (pintype "bidirectional"))
      (node (ref "J107") (pin "1") (pinfunction "1_1") (pintype "bidirectional"))
      (node (ref "J108") (pin "1") (pinfunction "1_1") (pintype "bidirectional"))
      (node (ref "J109") (pin "1") (pinfunction "1_1") (pintype "bidirectional"))
      (node (ref "J11") (pin "1") (pinfunction "1_1") (pintype "bidirectional"))
      (node (ref "J110") (pin "1") (pinfunction "1_1") (pintype "bidirectional"))
      (node (ref "J111") (pin "1") (pinfunction "1_1") (pintype "bidirectional"))
      (node (ref "J112") (pin "1") (pinfunction "1_1") (pintype "bidirectional"))
      (node (ref "J113") (pin "1") (pinfunction "1_1") (pintype "bidirectional"))
      (node (ref "J114") (pin "1") (pinfunction "1_1") (pintype "bidirectional"))
      (node (ref "J115") (pin "1") (pinfunction "1_1") (pintype "bidirectional"))
      (node (ref "J116") (pin "1") (pinfunction "1_1") (pintype "bidirectional"))
      (node (ref "J117") (pin "1") (pinfunction "1_1") (pintype "bidirectional"))
      (node (ref "J118") (pin "1") (pinfunction "1_1") (pintype "bidirectional"))
      (node (ref "J119") (pin "1") (pinfunction "1_1") (pintype "bidirectional"))
      (node (ref "J12") (pin "1") (pinfunction "1_1") (pintype "bidirectional"))
      (node (ref "J120") (pin "1") (pinfunction "1_1") (pintype "bidirectional"))
      (node (ref "J121") (pin "1") (pinfunction "1_1") (pintype "bidirectional"))
      (node (ref "J122") (pin "1") (pinfunction "1_1") (pintype "bidirectional"))
      (node (ref "J123") (pin "1") (pinfunction "1_1") (pintype "bidirectional"))
      (node (ref "J124") (pin "1") (pinfunction "1_1") (pintype "bidirectional"))
      (node (ref "J125") (pin "1") (pinfunction "1_1") (pintype "bidirectional"))
      (node (ref "J126") (pin "1") (pinfunction "1_1") (pintype "bidirectional"))
      (node (ref "J127") (pin "1") (pinfunction "1_1") (pintype "bidirectional"))
      (node (ref "J128") (pin "1") (pinfunction "1_1") (pintype "bidirectional"))
      (node (ref "J129") (pin "1") (pinfunction "1_1") (pintype "bidirectional"))
      (node (ref "J13") (pin "1") (pinfunction "1_1") (pintype "bidirectional"))
      (node (ref "J130") (pin "1") (pinfunction "1_1") (pintype "bidirectional"))
      (node (ref "J131") (pin "1") (pinfunction "1_1") (pintype "bidirectional"))
      (node (ref "J132") (pin "1") (pinfunction "1_1") (pintype "bidirectional"))
      (node (ref "J133") (pin "1") (pinfunction "1_1") (pintype "bidirectional"))
      (node (ref "J134") (pin "1") (pinfunction "1_1") (pintype "bidirectional"))
      (node (ref "J135") (pin "1") (pinfunction "1_1") (pintype "bidirectional"))
      (node (ref "J136") (pin "1") (pinfunction "1_1") (pintype "bidirectional"))
      (node (ref "J137") (pin "1") (pinfunction "1_1") (pintype "bidirectional"))
      (node (ref "J138") (pin "1") (pinfunction "1_1") (pintype "bidirectional"))
      (node (ref "J139") (pin "1") (pinfunction "1_1") (pintype "bidirectional"))
      (node (ref "J14") (pin "1") (pinfunction "1_1") (pintype "bidirectional"))
      (node (ref "J140") (pin "1") (pinfunction "1_1") (pintype "bidirectional"))
      (node (ref "J141") (pin "1") (pinfunction "1_1") (pintype "bidirectional"))
      (node (ref "J142") (pin "1") (pinfunction "1_1") (pintype "bidirectional"))
      (node (ref "J143") (pin "1") (pinfunction "1_1") (pintype "bidirectional"))
      (node (ref "J144") (pin "1") (pinfunction "1_1") (pintype "bidirectional"))
      (node (ref "J145") (pin "1") (pinfunction "1_1") (pintype "bidirectional"))
      (node (ref "J146") (pin "1") (pinfunction "1_1") (pintype "bidirectional"))
      (node (ref "J147") (pin "1") (pinfunction "1_1") (pintype "bidirectional"))
      (node (ref "J148") (pin "1") (pinfunction "1_1") (pintype "bidirectional"))
      (node (ref "J149") (pin "1") (pinfunction "1_1") (pintype "bidirectional"))
      (node (ref "J15") (pin "1") (pinfunction "1_1") (pintype "bidirectional"))
      (node (ref "J150") (pin "1") (pinfunction "1_1") (pintype "bidirectional"))
      (node (ref "J151") (pin "1") (pinfunction "1_1") (pintype "bidirectional"))
      (node (ref "J152") (pin "1") (pinfunction "1_1") (pintype "bidirectional"))
      (node (ref "J153") (pin "1") (pinfunction "1_1") (pintype "bidirectional"))
      (node (ref "J154") (pin "1") (pinfunction "1_1") (pintype "bidirectional"))
      (node (ref "J155") (pin "1") (pinfunction "1_1") (pintype "bidirectional"))
      (node (ref "J156") (pin "1") (pinfunction "1_1") (pintype "bidirectional"))
      (node (ref "J157") (pin "1") (pinfunction "1_1") (pintype "bidirectional"))
      (node (ref "J158") (pin "1") (pinfunction "1_1") (pintype "bidirectional"))
      (node (ref "J159") (pin "1") (pinfunction "1_1") (pintype "bidirectional"))
      (node (ref "J16") (pin "1") (pinfunction "1_1") (pintype "bidirectional"))
      (node (ref "J160") (pin "1") (pinfunction "1_1") (pintype "bidirectional"))
      (node (ref "J161") (pin "1") (pinfunction "1_1") (pintype "bidirectional"))
      (node (ref "J162") (pin "1") (pinfunction "1_1") (pintype "bidirectional"))
      (node (ref "J163") (pin "1") (pinfunction "1_1") (pintype "bidirectional"))
      (node (ref "J164") (pin "1") (pinfunction "1_1") (pintype "bidirectional"))
      (node (ref "J165") (pin "1") (pinfunction "1_1") (pintype "bidirectional"))
      (node (ref "J166") (pin "1") (pinfunction "1_1") (pintype "bidirectional"))
      (node (ref "J167") (pin "1") (pinfunction "1_1") (pintype "bidirectional"))
      (node (ref "J168") (pin "1") (pinfunction "1_1") (pintype "bidirectional"))
      (node (ref "J169") (pin "1") (pinfunction "1_1") (pintype "bidirectional"))
      (node (ref "J17") (pin "1") (pinfunction "1_1") (pintype "bidirectional"))
      (node (ref "J170") (pin "1") (pinfunction "1_1") (pintype "bidirectional"))
      (node (ref "J171") (pin "1") (pinfunction "1_1") (pintype "bidirectional"))
      (node (ref "J172") (pin "1") (pinfunction "1_1") (pintype "bidirectional"))
      (node (ref "J173") (pin "1") (pinfunction "1_1") (pintype "bidirectional"))
      (node (ref "J174") (pin "1") (pinfunction "1_1") (pintype "bidirectional"))
      (node (ref "J175") (pin "1") (pinfunction "1_1") (pintype "bidirectional"))
      (node (ref "J176") (pin "1") (pinfunction "1_1") (pintype "bidirectional"))
      (node (ref "J177") (pin "1") (pinfunction "1_1") (pintype "bidirectional"))
      (node (ref "J178") (pin "1") (pinfunction "1_1") (pintype "bidirectional"))
      (node (ref "J179") (pin "1") (pinfunction "1_1") (pintype "bidirectional"))
      (node (ref "J18") (pin "1") (pinfunction "1_1") (pintype "bidirectional"))
      (node (ref "J180") (pin "1") (pinfunction "1_1") (pintype "bidirectional"))
      (node (ref "J181") (pin "1") (pinfunction "1_1") (pintype "bidirectional"))
      (node (ref "J182") (pin "1") (pinfunction "1_1") (pintype "bidirectional"))
      (node (ref "J183") (pin "1") (pinfunction "1_1") (pintype "bidirectional"))
      (node (ref "J184") (pin "1") (pinfunction "1_1") (pintype "bidirectional"))
      (node (ref "J185") (pin "1") (pinfunction "1_1") (pintype "bidirectional"))
      (node (ref "J186") (pin "1") (pinfunction "1_1") (pintype "bidirectional"))
      (node (ref "J187") (pin "1") (pinfunction "1_1") (pintype "bidirectional"))
      (node (ref "J188") (pin "1") (pinfunction "1_1") (pintype "bidirectional"))
      (node (ref "J189") (pin "1") (pinfunction "1_1") (pintype "bidirectional"))
      (node (ref "J19") (pin "1") (pinfunction "1_1") (pintype "bidirectional"))
      (node (ref "J190") (pin "1") (pinfunction "1_1") (pintype "bidirectional"))
      (node (ref "J191") (pin "1") (pinfunction "1_1") (pintype "bidirectional"))
      (node (ref "J192") (pin "1") (pinfunction "1_1") (pintype "bidirectional"))
      (node (ref "J193") (pin "1") (pinfunction "1_1") (pintype "bidirectional"))
      (node (ref "J194") (pin "1") (pinfunction "1_1") (pintype "bidirectional"))
      (node (ref "J195") (pin "1") (pinfunction "1_1") (pintype "bidirectional"))
      (node (ref "J196") (pin "1") (pinfunction "1_1") (pintype "bidirectional"))
      (node (ref "J197") (pin "1") (pinfunction "1_1") (pintype "bidirectional"))
      (node (ref "J198") (pin "1") (pinfunction "1_1") (pintype "bidirectional"))
      (node (ref "J199") (pin "1") (pinfunction "1_1") (pintype "bidirectional"))
      (node (ref "J2") (pin "1") (pinfunction "1_1") (pintype "bidirectional"))
      (node (ref "J20") (pin "1") (pinfunction "1_1") (pintype "bidirectional"))
      (node (ref "J200") (pin "1") (pinfunction "1_1") (pintype "bidirectional"))
      (node (ref "J201") (pin "1") (pinfunction "1_1") (pintype "bidirectional"))
      (node (ref "J202") (pin "1") (pinfunction "1_1") (pintype "bidirectional"))
      (node (ref "J203") (pin "1") (pinfunction "1_1") (pintype "bidirectional"))
      (node (ref "J204") (pin "1") (pinfunction "1_1") (pintype "bidirectional"))
      (node (ref "J205") (pin "1") (pinfunction "1_1") (pintype "bidirectional"))
      (node (ref "J206") (pin "1") (pinfunction "1_1") (pintype "bidirectional"))
      (node (ref "J207") (pin "1") (pinfunction "1_1") (pintype "bidirectional"))
      (node (ref "J208") (pin "1") (pinfunction "1_1") (pintype "bidirectional"))
      (node (ref "J209") (pin "1") (pinfunction "1_1") (pintype "bidirectional"))
      (node (ref "J21") (pin "1") (pinfunction "1_1") (pintype "bidirectional"))
      (node (ref "J210") (pin "1") (pinfunction "1_1") (pintype "bidirectional"))
      (node (ref "J211") (pin "1") (pinfunction "1_1") (pintype "bidirectional"))
      (node (ref "J212") (pin "1") (pinfunction "1_1") (pintype "bidirectional"))
      (node (ref "J213") (pin "1") (pinfunction "1_1") (pintype "bidirectional"))
      (node (ref "J214") (pin "1") (pinfunction "1_1") (pintype "bidirectional"))
      (node (ref "J215") (pin "1") (pinfunction "1_1") (pintype "bidirectional"))
      (node (ref "J216") (pin "1") (pinfunction "1_1") (pintype "bidirectional"))
      (node (ref "J217") (pin "1") (pinfunction "1_1") (pintype "bidirectional"))
      (node (ref "J218") (pin "1") (pinfunction "1_1") (pintype "bidirectional"))
      (node (ref "J219") (pin "1") (pinfunction "1_1") (pintype "bidirectional"))
      (node (ref "J22") (pin "1") (pinfunction "1_1") (pintype "bidirectional"))
      (node (ref "J220") (pin "1") (pinfunction "1_1") (pintype "bidirectional"))
      (node (ref "J221") (pin "1") (pinfunction "1_1") (pintype "bidirectional"))
      (node (ref "J222") (pin "1") (pinfunction "1_1") (pintype "bidirectional"))
      (node (ref "J223") (pin "1") (pinfunction "1_1") (pintype "bidirectional"))
      (node (ref "J224") (pin "1") (pinfunction "1_1") (pintype "bidirectional"))
      (node (ref "J225") (pin "1") (pinfunction "1_1") (pintype "bidirectional"))
      (node (ref "J226") (pin "1") (pinfunction "1_1") (pintype "bidirectional"))
      (node (ref "J227") (pin "1") (pinfunction "1_1") (pintype "bidirectional"))
      (node (ref "J228") (pin "1") (pinfunction "1_1") (pintype "bidirectional"))
      (node (ref "J229") (pin "1") (pinfunction "1_1") (pintype "bidirectional"))
      (node (ref "J23") (pin "1") (pinfunction "1_1") (pintype "bidirectional"))
      (node (ref "J230") (pin "1") (pinfunction "1_1") (pintype "bidirectional"))
      (node (ref "J231") (pin "1") (pinfunction "1_1") (pintype "bidirectional"))
      (node (ref "J232") (pin "1") (pinfunction "1_1") (pintype "bidirectional"))
      (node (ref "J233") (pin "1") (pinfunction "1_1") (pintype "bidirectional"))
      (node (ref "J234") (pin "1") (pinfunction "1_1") (pintype "bidirectional"))
      (node (ref "J235") (pin "1") (pinfunction "1_1") (pintype "bidirectional"))
      (node (ref "J236") (pin "1") (pinfunction "1_1") (pintype "bidirectional"))
      (node (ref "J237") (pin "1") (pinfunction "1_1") (pintype "bidirectional"))
      (node (ref "J238") (pin "1") (pinfunction "1_1") (pintype "bidirectional"))
      (node (ref "J239") (pin "1") (pinfunction "1_1") (pintype "bidirectional"))
      (node (ref "J24") (pin "1") (pinfunction "1_1") (pintype "bidirectional"))
      (node (ref "J240") (pin "1") (pinfunction "1_1") (pintype "bidirectional"))
      (node (ref "J241") (pin "1") (pinfunction "1_1") (pintype "bidirectional"))
      (node (ref "J242") (pin "1") (pinfunction "1_1") (pintype "bidirectional"))
      (node (ref "J243") (pin "1") (pinfunction "1_1") (pintype "bidirectional"))
      (node (ref "J244") (pin "1") (pinfunction "1_1") (pintype "bidirectional"))
      (node (ref "J245") (pin "1") (pinfunction "1_1") (pintype "bidirectional"))
      (node (ref "J246") (pin "1") (pinfunction "1_1") (pintype "bidirectional"))
      (node (ref "J247") (pin "1") (pinfunction "1_1") (pintype "bidirectional"))
      (node (ref "J248") (pin "1") (pinfunction "1_1") (pintype "bidirectional"))
      (node (ref "J249") (pin "1") (pinfunction "1_1") (pintype "bidirectional"))
      (node (ref "J25") (pin "1") (pinfunction "1_1") (pintype "bidirectional"))
      (node (ref "J250") (pin "1") (pinfunction "1_1") (pintype "bidirectional"))
      (node (ref "J251") (pin "1") (pinfunction "1_1") (pintype "bidirectional"))
      (node (ref "J252") (pin "1") (pinfunction "1_1") (pintype "bidirectional"))
      (node (ref "J253") (pin "1") (pinfunction "1_1") (pintype "bidirectional"))
      (node (ref "J254") (pin "1") (pinfunction "1_1") (pintype "bidirectional"))
      (node (ref "J255") (pin "1") (pinfunction "1_1") (pintype "bidirectional"))
      (node (ref "J256") (pin "1") (pinfunction "1_1") (pintype "bidirectional"))
      (node (ref "J26") (pin "1") (pinfunction "1_1") (pintype "bidirectional"))
      (node (ref "J27") (pin "1") (pinfunction "1_1") (pintype "bidirectional"))
      (node (ref "J28") (pin "1") (pinfunction "1_1") (pintype "bidirectional"))
      (node (ref "J29") (pin "1") (pinfunction "1_1") (pintype "bidirectional"))
      (node (ref "J3") (pin "1") (pinfunction "1_1") (pintype "bidirectional"))
      (node (ref "J30") (pin "1") (pinfunction "1_1") (pintype "bidirectional"))
      (node (ref "J31") (pin "1") (pinfunction "1_1") (pintype "bidirectional"))
      (node (ref "J32") (pin "1") (pinfunction "1_1") (pintype "bidirectional"))
      (node (ref "J33") (pin "1") (pinfunction "1_1") (pintype "bidirectional"))
      (node (ref "J34") (pin "1") (pinfunction "1_1") (pintype "bidirectional"))
      (node (ref "J35") (pin "1") (pinfunction "1_1") (pintype "bidirectional"))
      (node (ref "J36") (pin "1") (pinfunction "1_1") (pintype "bidirectional"))
      (node (ref "J37") (pin "1") (pinfunction "1_1") (pintype "bidirectional"))
      (node (ref "J38") (pin "1") (pinfunction "1_1") (pintype "bidirectional"))
      (node (ref "J39") (pin "1") (pinfunction "1_1") (pintype "bidirectional"))
      (node (ref "J4") (pin "1") (pinfunction "1_1") (pintype "bidirectional"))
      (node (ref "J40") (pin "1") (pinfunction "1_1") (pintype "bidirectional"))
      (node (ref "J41") (pin "1") (pinfunction "1_1") (pintype "bidirectional"))
      (node (ref "J42") (pin "1") (pinfunction "1_1") (pintype "bidirectional"))
      (node (ref "J43") (pin "1") (pinfunction "1_1") (pintype "bidirectional"))
      (node (ref "J44") (pin "1") (pinfunction "1_1") (pintype "bidirectional"))
      (node (ref "J45") (pin "1") (pinfunction "1_1") (pintype "bidirectional"))
      (node (ref "J46") (pin "1") (pinfunction "1_1") (pintype "bidirectional"))
      (node (ref "J47") (pin "1") (pinfunction "1_1") (pintype "bidirectional"))
      (node (ref "J48") (pin "1") (pinfunction "1_1") (pintype "bidirectional"))
      (node (ref "J49") (pin "1") (pinfunction "1_1") (pintype "bidirectional"))
      (node (ref "J5") (pin "1") (pinfunction "1_1") (pintype "bidirectional"))
      (node (ref "J50") (pin "1") (pinfunction "1_1") (pintype "bidirectional"))
      (node (ref "J51") (pin "1") (pinfunction "1_1") (pintype "bidirectional"))
      (node (ref "J52") (pin "1") (pinfunction "1_1") (pintype "bidirectional"))
      (node (ref "J53") (pin "1") (pinfunction "1_1") (pintype "bidirectional"))
      (node (ref "J54") (pin "1") (pinfunction "1_1") (pintype "bidirectional"))
      (node (ref "J55") (pin "1") (pinfunction "1_1") (pintype "bidirectional"))
      (node (ref "J56") (pin "1") (pinfunction "1_1") (pintype "bidirectional"))
      (node (ref "J57") (pin "1") (pinfunction "1_1") (pintype "bidirectional"))
      (node (ref "J58") (pin "1") (pinfunction "1_1") (pintype "bidirectional"))
      (node (ref "J59") (pin "1") (pinfunction "1_1") (pintype "bidirectional"))
      (node (ref "J6") (pin "1") (pinfunction "1_1") (pintype "bidirectional"))
      (node (ref "J60") (pin "1") (pinfunction "1_1") (pintype "bidirectional"))
      (node (ref "J61") (pin "1") (pinfunction "1_1") (pintype "bidirectional"))
      (node (ref "J62") (pin "1") (pinfunction "1_1") (pintype "bidirectional"))
      (node (ref "J63") (pin "1") (pinfunction "1_1") (pintype "bidirectional"))
      (node (ref "J64") (pin "1") (pinfunction "1_1") (pintype "bidirectional"))
      (node (ref "J65") (pin "1") (pinfunction "1_1") (pintype "bidirectional"))
      (node (ref "J66") (pin "1") (pinfunction "1_1") (pintype "bidirectional"))
      (node (ref "J67") (pin "1") (pinfunction "1_1") (pintype "bidirectional"))
      (node (ref "J68") (pin "1") (pinfunction "1_1") (pintype "bidirectional"))
      (node (ref "J69") (pin "1") (pinfunction "1_1") (pintype "bidirectional"))
      (node (ref "J7") (pin "1") (pinfunction "1_1") (pintype "bidirectional"))
      (node (ref "J70") (pin "1") (pinfunction "1_1") (pintype "bidirectional"))
      (node (ref "J71") (pin "1") (pinfunction "1_1") (pintype "bidirectional"))
      (node (ref "J72") (pin "1") (pinfunction "1_1") (pintype "bidirectional"))
      (node (ref "J73") (pin "1") (pinfunction "1_1") (pintype "bidirectional"))
      (node (ref "J74") (pin "1") (pinfunction "1_1") (pintype "bidirectional"))
      (node (ref "J75") (pin "1") (pinfunction "1_1") (pintype "bidirectional"))
      (node (ref "J76") (pin "1") (pinfunction "1_1") (pintype "bidirectional"))
      (node (ref "J77") (pin "1") (pinfunction "1_1") (pintype "bidirectional"))
      (node (ref "J78") (pin "1") (pinfunction "1_1") (pintype "bidirectional"))
      (node (ref "J79") (pin "1") (pinfunction "1_1") (pintype "bidirectional"))
      (node (ref "J8") (pin "1") (pinfunction "1_1") (pintype "bidirectional"))
      (node (ref "J80") (pin "1") (pinfunction "1_1") (pintype "bidirectional"))
      (node (ref "J81") (pin "1") (pinfunction "1_1") (pintype "bidirectional"))
      (node (ref "J82") (pin "1") (pinfunction "1_1") (pintype "bidirectional"))
      (node (ref "J83") (pin "1") (pinfunction "1_1") (pintype "bidirectional"))
      (node (ref "J84") (pin "1") (pinfunction "1_1") (pintype "bidirectional"))
      (node (ref "J85") (pin "1") (pinfunction "1_1") (pintype "bidirectional"))
      (node (ref "J86") (pin "1") (pinfunction "1_1") (pintype "bidirectional"))
      (node (ref "J87") (pin "1") (pinfunction "1_1") (pintype "bidirectional"))
      (node (ref "J88") (pin "1") (pinfunction "1_1") (pintype "bidirectional"))
      (node (ref "J89") (pin "1") (pinfunction "1_1") (pintype "bidirectional"))
      (node (ref "J9") (pin "1") (pinfunction "1_1") (pintype "bidirectional"))
      (node (ref "J90") (pin "1") (pinfunction "1_1") (pintype "bidirectional"))
      (node (ref "J91") (pin "1") (pinfunction "1_1") (pintype "bidirectional"))
      (node (ref "J92") (pin "1") (pinfunction "1_1") (pintype "bidirectional"))
      (node (ref "J93") (pin "1") (pinfunction "1_1") (pintype "bidirectional"))
      (node (ref "J94") (pin "1") (pinfunction "1_1") (pintype "bidirectional"))
      (node (ref "J95") (pin "1") (pinfunction "1_1") (pintype "bidirectional"))
      (node (ref "J96") (pin "1") (pinfunction "1_1") (pintype "bidirectional"))
      (node (ref "J97") (pin "1") (pinfunction "1_1") (pintype "bidirectional"))
      (node (ref "J98") (pin "1") (pinfunction "1_1") (pintype "bidirectional"))
      (node (ref "J99") (pin "1") (pinfunction "1_1") (pintype "bidirectional"))
    )
    (net (code "259") (name "unconnected-(J64-Pad3)") (class "Default")
      (node (ref "J64") (pin "3") (pinfunction "3_3") (pintype "bidirectional"))
    )
    (net (code "260") (name "unconnected-(J128-Pad3)") (class "Default")
      (node (ref "J128") (pin "3") (pinfunction "3_3") (pintype "bidirectional"))
    )
    (net (code "261") (name "unconnected-(J192-Pad3)") (class "Default")
      (node (ref "J192") (pin "3") (pinfunction "3_3") (pintype "bidirectional"))
    )
    (net (code "262") (name "unconnected-(J256-Pad3)") (class "Default")
      (node (ref "J256") (pin "3") (pinfunction "3_3") (pintype "bidirectional"))
    )
  )
)
